# BeagleBone_Black_Wireless.net
KiCad netlist of a schematic drawn in EAGLE
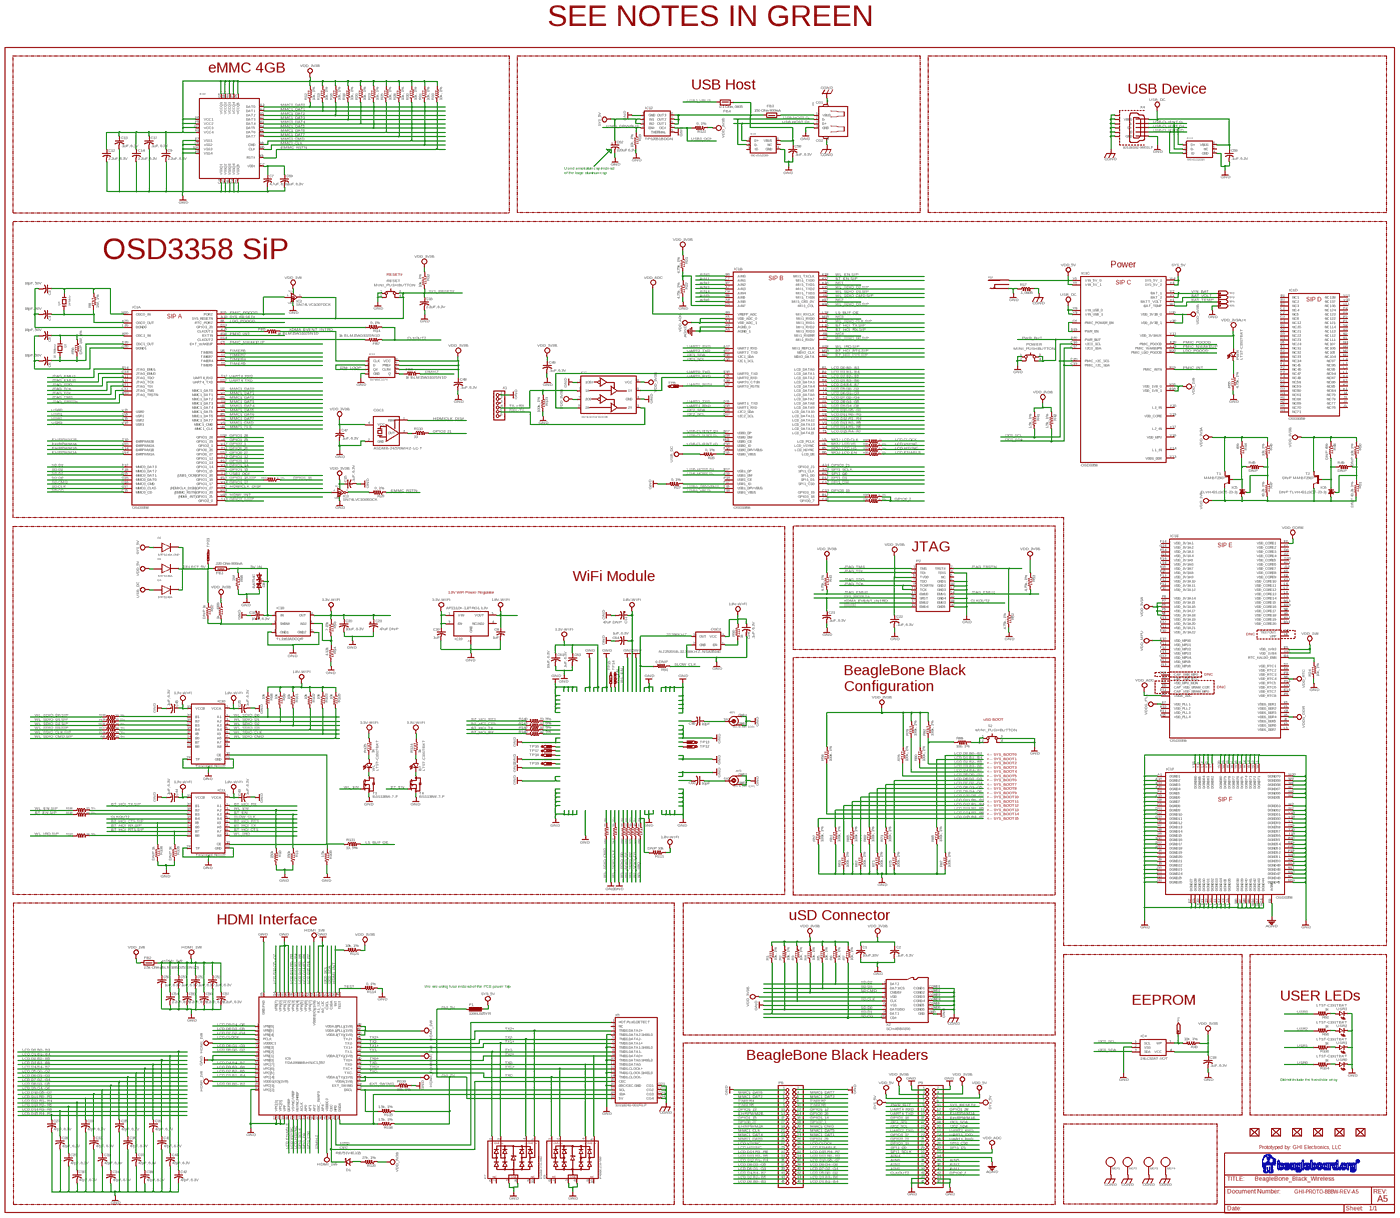
[diagram p0: schematic, sheet 1, overview]
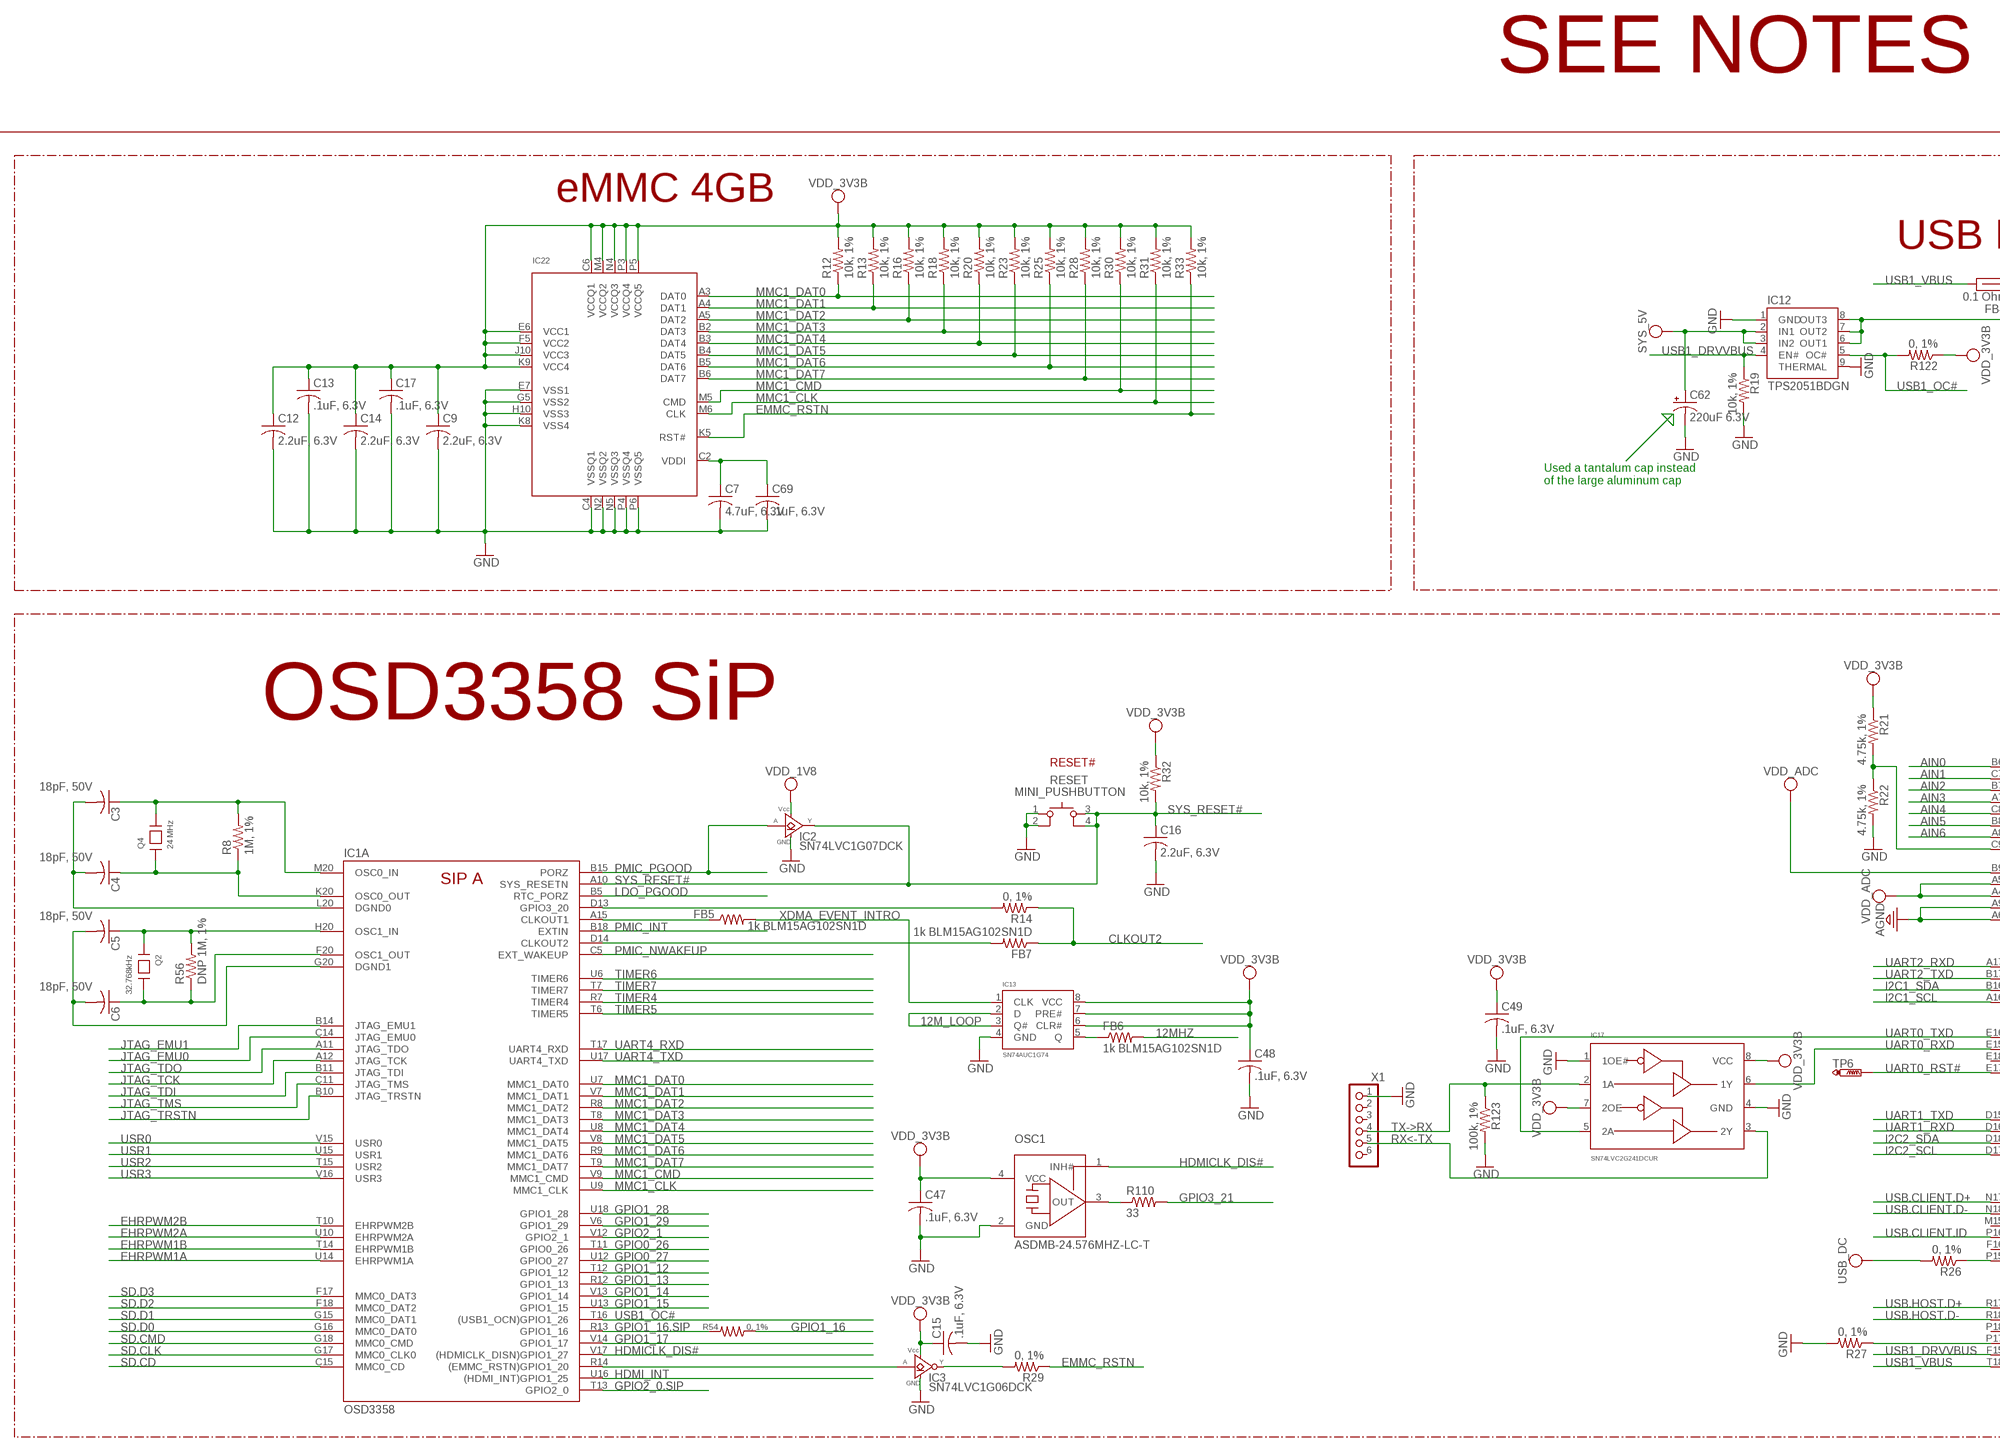
[diagram p1: schematic, sheet 1, part 1 of 4]
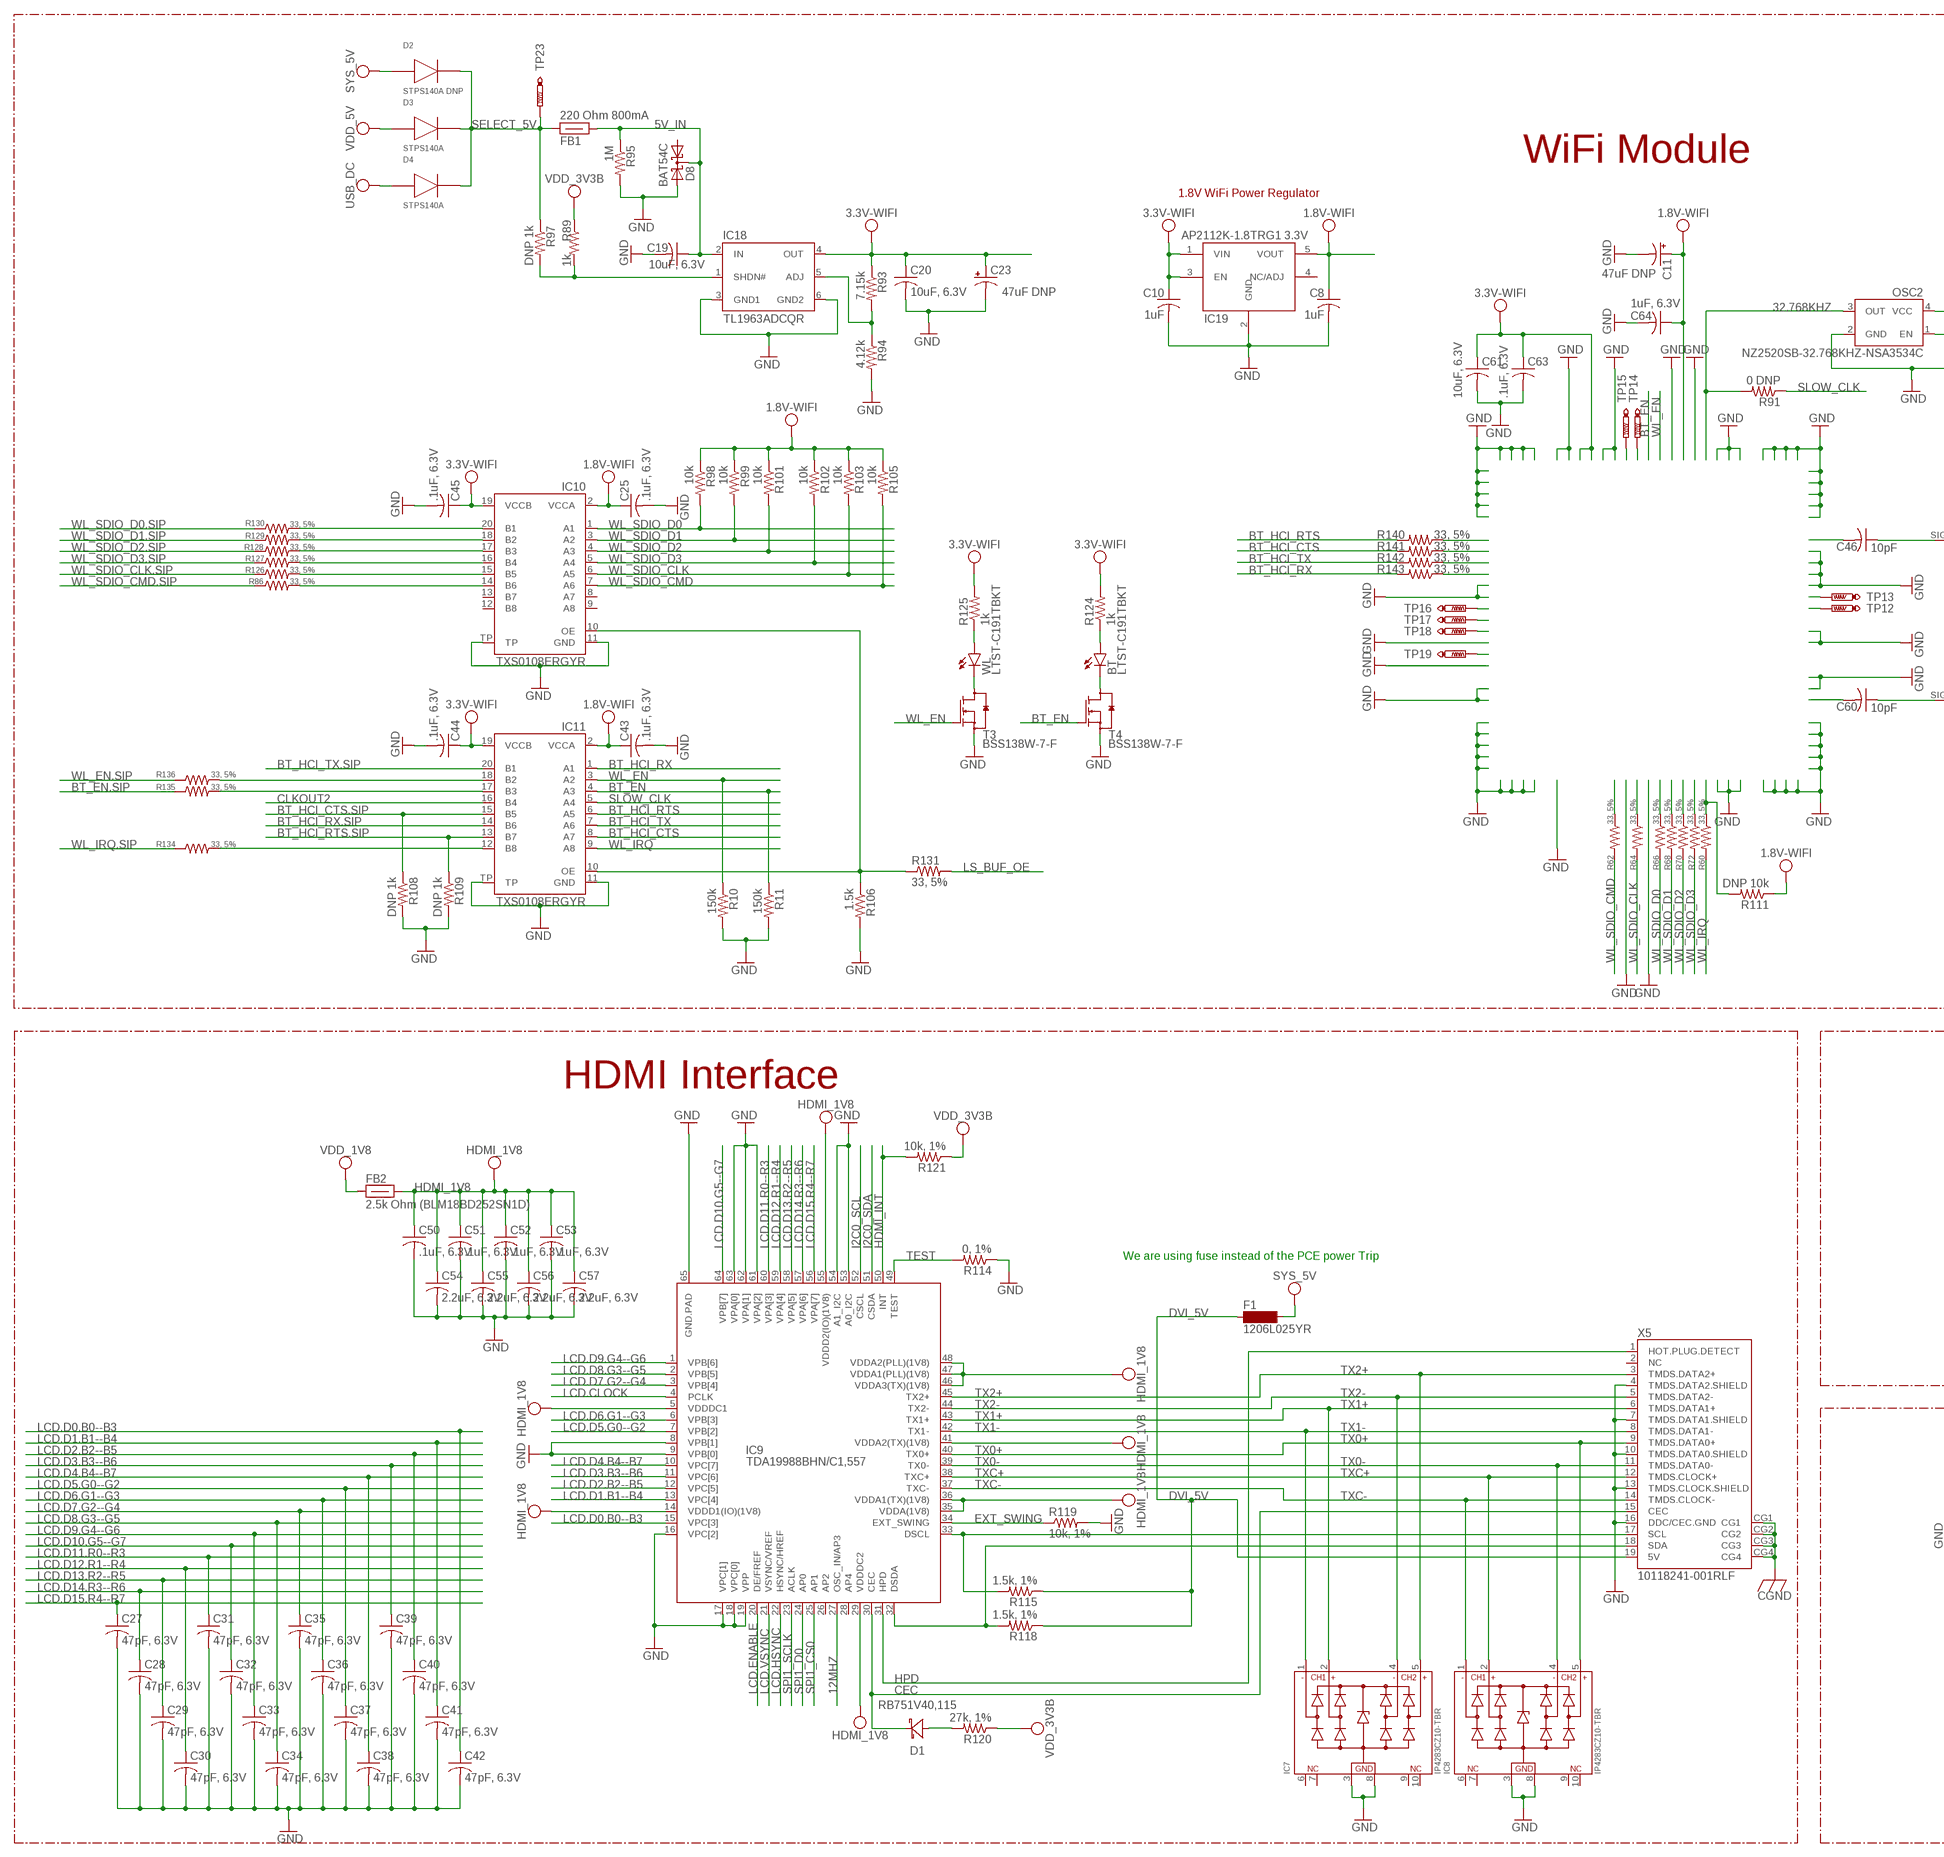
[diagram p2: schematic, sheet 1, part 2 of 4]
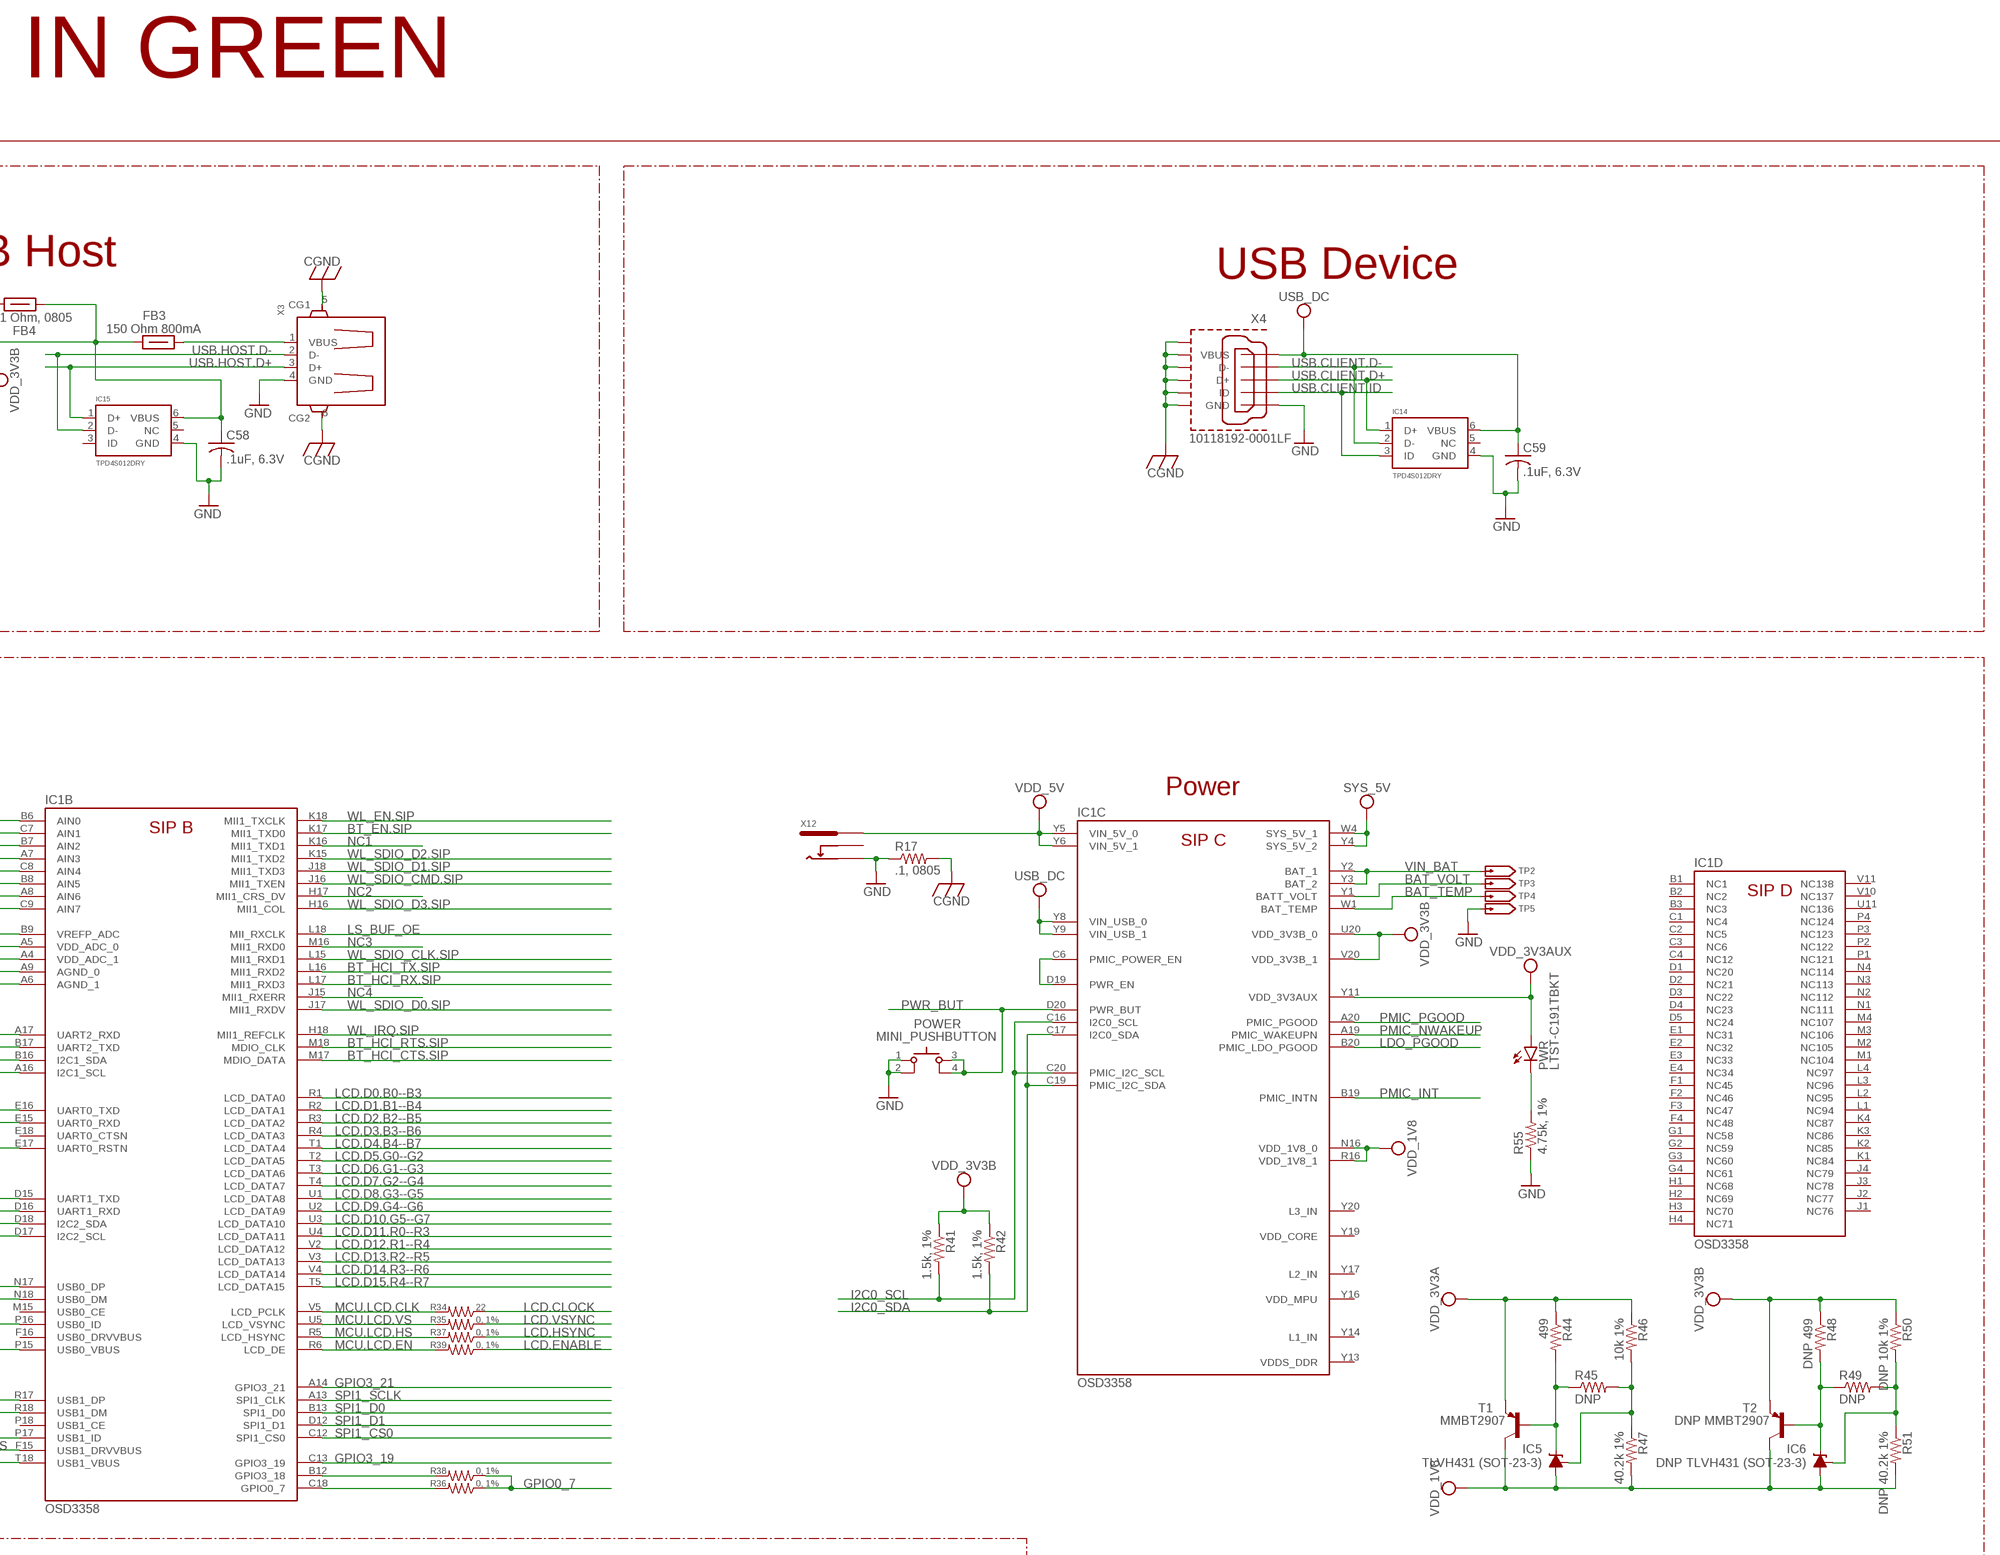
[diagram p3: schematic, sheet 1, part 3 of 4]
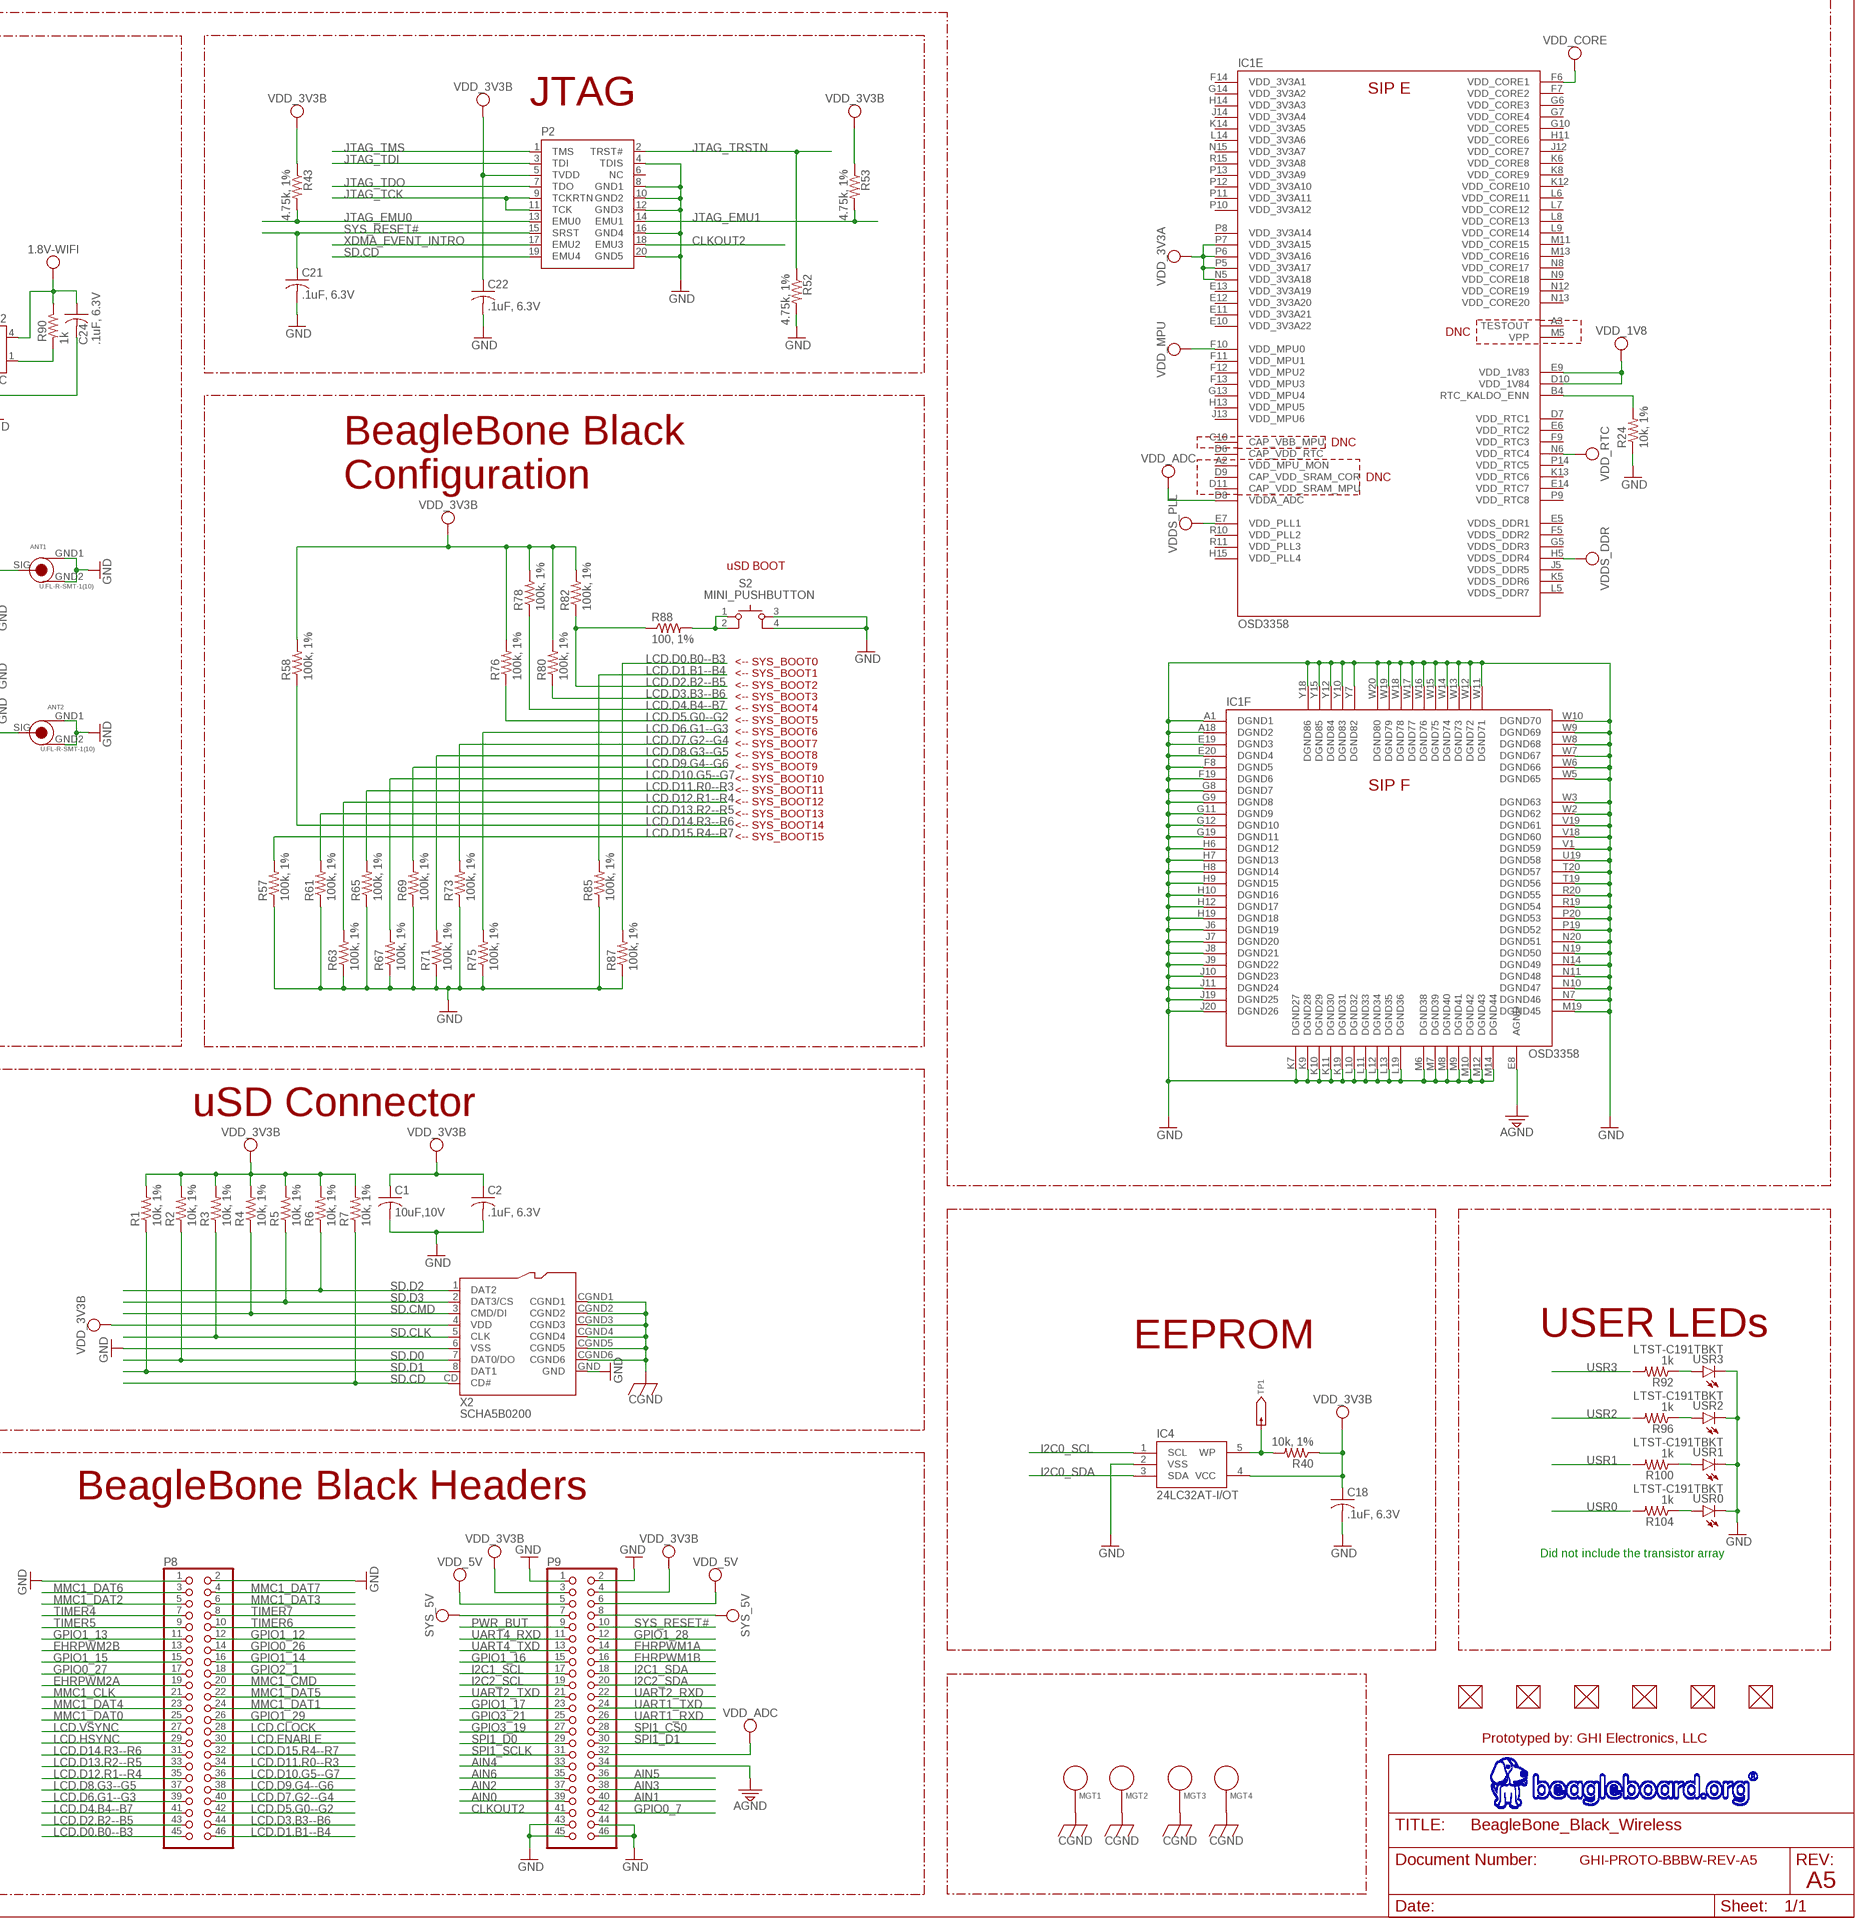
[diagram p4: schematic, sheet 1, part 4 of 4]

(export (version "E")
  (design (tool "Eeschema 10.0.6"))
  (components
    (comp (ref "ANT1")
      (value "U.FL-R-SMT-1(10)")
      (footprint "eagle-import:U.FL-R-SMT-1")
      (libsource (lib "eagle-import") (part "U.FL-R-SMT-1"))
    )
    (comp (ref "ANT2")
      (value "U.FL-R-SMT-1(10)")
      (footprint "eagle-import:U.FL-R-SMT-1")
      (libsource (lib "eagle-import") (part "U.FL-R-SMT-1"))
    )
    (comp (ref "BT")
      (value "LTST-C191TBKT")
      (footprint "eagle-import:0603-LED")
      (libsource (lib "eagle-import") (part "LED-(INCH)-0603"))
    )
    (comp (ref "C1")
      (value "10uF,10V")
      (footprint "eagle-import:C0603K")
      (libsource (lib "eagle-import") (part "C-USC0603K"))
    )
    (comp (ref "C2")
      (value ".1uF, 6.3V")
      (footprint "eagle-import:C0402K")
      (libsource (lib "eagle-import") (part "C-USC0402K"))
    )
    (comp (ref "C3")
      (value "18pF, 50V")
      (footprint "eagle-import:C0402K")
      (libsource (lib "eagle-import") (part "C-USC0402K"))
    )
    (comp (ref "C4")
      (value "18pF, 50V")
      (footprint "eagle-import:C0402K")
      (libsource (lib "eagle-import") (part "C-USC0402K"))
    )
    (comp (ref "C5")
      (value "18pF, 50V")
      (footprint "eagle-import:C0402K")
      (libsource (lib "eagle-import") (part "C-USC0402K"))
    )
    (comp (ref "C6")
      (value "18pF, 50V")
      (footprint "eagle-import:C0402K")
      (libsource (lib "eagle-import") (part "C-USC0402K"))
    )
    (comp (ref "C7")
      (value "4.7uF, 6.3V")
      (footprint "eagle-import:C0805K")
      (libsource (lib "eagle-import") (part "C-USC0805K"))
    )
    (comp (ref "C8")
      (value "1uF")
      (footprint "eagle-import:C0402K")
      (libsource (lib "eagle-import") (part "C-USC0402K"))
    )
    (comp (ref "C9")
      (value "2.2uF, 6.3V")
      (footprint "eagle-import:C0805K")
      (libsource (lib "eagle-import") (part "C-USC0805K"))
    )
    (comp (ref "C10")
      (value "1uF")
      (footprint "eagle-import:C0402K")
      (libsource (lib "eagle-import") (part "C-USC0402K"))
    )
    (comp (ref "C11")
      (value "47uF DNP")
      (footprint "eagle-import:CT3528")
      (libsource (lib "eagle-import") (part "CPOL-USCT3528"))
    )
    (comp (ref "C12")
      (value "2.2uF, 6.3V")
      (footprint "eagle-import:C0805K")
      (libsource (lib "eagle-import") (part "C-USC0805K"))
    )
    (comp (ref "C13")
      (value ".1uF, 6.3V")
      (footprint "eagle-import:C0402K")
      (libsource (lib "eagle-import") (part "C-USC0402K"))
    )
    (comp (ref "C14")
      (value "2.2uF, 6.3V")
      (footprint "eagle-import:C0805K")
      (libsource (lib "eagle-import") (part "C-USC0805K"))
    )
    (comp (ref "C15")
      (value ".1uF, 6.3V")
      (footprint "eagle-import:C0402K")
      (libsource (lib "eagle-import") (part "C-USC0402K"))
    )
    (comp (ref "C16")
      (value "2.2uF, 6.3V")
      (footprint "eagle-import:C0603K")
      (libsource (lib "eagle-import") (part "C-USC0603K"))
    )
    (comp (ref "C17")
      (value ".1uF, 6.3V")
      (footprint "eagle-import:C0402K")
      (libsource (lib "eagle-import") (part "C-USC0402K"))
    )
    (comp (ref "C18")
      (value ".1uF, 6.3V")
      (footprint "eagle-import:C0402K")
      (libsource (lib "eagle-import") (part "C-USC0402K"))
    )
    (comp (ref "C19")
      (value "10uF, 6.3V")
      (footprint "eagle-import:C0603K")
      (libsource (lib "eagle-import") (part "C-USC0603K"))
    )
    (comp (ref "C20")
      (value "10uF, 6.3V")
      (footprint "eagle-import:C0603K")
      (libsource (lib "eagle-import") (part "C-USC0603K"))
    )
    (comp (ref "C21")
      (value ".1uF, 6.3V")
      (footprint "eagle-import:C0402K")
      (libsource (lib "eagle-import") (part "C-USC0402K"))
    )
    (comp (ref "C22")
      (value ".1uF, 6.3V")
      (footprint "eagle-import:C0402K")
      (libsource (lib "eagle-import") (part "C-USC0402K"))
    )
    (comp (ref "C23")
      (value "47uF DNP")
      (footprint "eagle-import:CT3528")
      (libsource (lib "eagle-import") (part "CPOL-USCT3528"))
    )
    (comp (ref "C24")
      (value ".1uF, 6.3V")
      (footprint "eagle-import:C0402K")
      (libsource (lib "eagle-import") (part "C-USC0402K"))
    )
    (comp (ref "C25")
      (value ".1uF, 6.3V")
      (footprint "eagle-import:C0402K")
      (libsource (lib "eagle-import") (part "C-USC0402K"))
    )
    (comp (ref "C27")
      (value "47pF, 6.3V")
      (footprint "eagle-import:C0402K")
      (libsource (lib "eagle-import") (part "C-USC0402K"))
    )
    (comp (ref "C28")
      (value "47pF, 6.3V")
      (footprint "eagle-import:C0402K")
      (libsource (lib "eagle-import") (part "C-USC0402K"))
    )
    (comp (ref "C29")
      (value "47pF, 6.3V")
      (footprint "eagle-import:C0402K")
      (libsource (lib "eagle-import") (part "C-USC0402K"))
    )
    (comp (ref "C30")
      (value "47pF, 6.3V")
      (footprint "eagle-import:C0402K")
      (libsource (lib "eagle-import") (part "C-USC0402K"))
    )
    (comp (ref "C31")
      (value "47pF, 6.3V")
      (footprint "eagle-import:C0402K")
      (libsource (lib "eagle-import") (part "C-USC0402K"))
    )
    (comp (ref "C32")
      (value "47pF, 6.3V")
      (footprint "eagle-import:C0402K")
      (libsource (lib "eagle-import") (part "C-USC0402K"))
    )
    (comp (ref "C33")
      (value "47pF, 6.3V")
      (footprint "eagle-import:C0402K")
      (libsource (lib "eagle-import") (part "C-USC0402K"))
    )
    (comp (ref "C34")
      (value "47pF, 6.3V")
      (footprint "eagle-import:C0402K")
      (libsource (lib "eagle-import") (part "C-USC0402K"))
    )
    (comp (ref "C35")
      (value "47pF, 6.3V")
      (footprint "eagle-import:C0402K")
      (libsource (lib "eagle-import") (part "C-USC0402K"))
    )
    (comp (ref "C36")
      (value "47pF, 6.3V")
      (footprint "eagle-import:C0402K")
      (libsource (lib "eagle-import") (part "C-USC0402K"))
    )
    (comp (ref "C37")
      (value "47pF, 6.3V")
      (footprint "eagle-import:C0402K")
      (libsource (lib "eagle-import") (part "C-USC0402K"))
    )
    (comp (ref "C38")
      (value "47pF, 6.3V")
      (footprint "eagle-import:C0402K")
      (libsource (lib "eagle-import") (part "C-USC0402K"))
    )
    (comp (ref "C39")
      (value "47pF, 6.3V")
      (footprint "eagle-import:C0402K")
      (libsource (lib "eagle-import") (part "C-USC0402K"))
    )
    (comp (ref "C40")
      (value "47pF, 6.3V")
      (footprint "eagle-import:C0402K")
      (libsource (lib "eagle-import") (part "C-USC0402K"))
    )
    (comp (ref "C41")
      (value "47pF, 6.3V")
      (footprint "eagle-import:C0402K")
      (libsource (lib "eagle-import") (part "C-USC0402K"))
    )
    (comp (ref "C42")
      (value "47pF, 6.3V")
      (footprint "eagle-import:C0402K")
      (libsource (lib "eagle-import") (part "C-USC0402K"))
    )
    (comp (ref "C43")
      (value ".1uF, 6.3V")
      (footprint "eagle-import:C0402K")
      (libsource (lib "eagle-import") (part "C-USC0402K"))
    )
    (comp (ref "C44")
      (value ".1uF, 6.3V")
      (footprint "eagle-import:C0402K")
      (libsource (lib "eagle-import") (part "C-USC0402K"))
    )
    (comp (ref "C45")
      (value ".1uF, 6.3V")
      (footprint "eagle-import:C0402K")
      (libsource (lib "eagle-import") (part "C-USC0402K"))
    )
    (comp (ref "C46")
      (value "10pF")
      (footprint "eagle-import:C0402K")
      (libsource (lib "eagle-import") (part "C-USC0402K"))
    )
    (comp (ref "C47")
      (value ".1uF, 6.3V")
      (footprint "eagle-import:C0402K")
      (libsource (lib "eagle-import") (part "C-USC0402K"))
    )
    (comp (ref "C48")
      (value ".1uF, 6.3V")
      (footprint "eagle-import:C0402K")
      (libsource (lib "eagle-import") (part "C-USC0402K"))
    )
    (comp (ref "C49")
      (value ".1uF, 6.3V")
      (footprint "eagle-import:C0402K")
      (libsource (lib "eagle-import") (part "C-USC0402K"))
    )
    (comp (ref "C50")
      (value ".1uF, 6.3V")
      (footprint "eagle-import:C0402K")
      (libsource (lib "eagle-import") (part "C-USC0402K"))
    )
    (comp (ref "C51")
      (value ".1uF, 6.3V")
      (footprint "eagle-import:C0402K")
      (libsource (lib "eagle-import") (part "C-USC0402K"))
    )
    (comp (ref "C52")
      (value ".1uF, 6.3V")
      (footprint "eagle-import:C0402K")
      (libsource (lib "eagle-import") (part "C-USC0402K"))
    )
    (comp (ref "C53")
      (value ".1uF, 6.3V")
      (footprint "eagle-import:C0402K")
      (libsource (lib "eagle-import") (part "C-USC0402K"))
    )
    (comp (ref "C54")
      (value "2.2uF, 6.3V")
      (footprint "eagle-import:C0603K")
      (libsource (lib "eagle-import") (part "C-USC0603K"))
    )
    (comp (ref "C55")
      (value "2.2uF, 6.3V")
      (footprint "eagle-import:C0603K")
      (libsource (lib "eagle-import") (part "C-USC0603K"))
    )
    (comp (ref "C56")
      (value "2.2uF, 6.3V")
      (footprint "eagle-import:C0603K")
      (libsource (lib "eagle-import") (part "C-USC0603K"))
    )
    (comp (ref "C57")
      (value "2.2uF, 6.3V")
      (footprint "eagle-import:C0603K")
      (libsource (lib "eagle-import") (part "C-USC0603K"))
    )
    (comp (ref "C58")
      (value ".1uF, 6.3V")
      (footprint "eagle-import:C0402K")
      (libsource (lib "eagle-import") (part "C-USC0402K"))
    )
    (comp (ref "C59")
      (value ".1uF, 6.3V")
      (footprint "eagle-import:C0402K")
      (libsource (lib "eagle-import") (part "C-USC0402K"))
    )
    (comp (ref "C60")
      (value "10pF")
      (footprint "eagle-import:C0402K")
      (libsource (lib "eagle-import") (part "C-USC0402K"))
    )
    (comp (ref "C61")
      (value "10uF, 6.3V")
      (footprint "eagle-import:C0603K")
      (libsource (lib "eagle-import") (part "C-USC0603K"))
    )
    (comp (ref "C62")
      (value "220uF 6.3V")
      (footprint "eagle-import:D_7343-31W")
      (libsource (lib "eagle-import") (part "CPOL-USD/7343-31W"))
    )
    (comp (ref "C63")
      (value ".1uF, 6.3V")
      (footprint "eagle-import:C0402K")
      (libsource (lib "eagle-import") (part "C-USC0402K"))
    )
    (comp (ref "C64")
      (value "1uF, 6.3V")
      (footprint "eagle-import:C0402K")
      (libsource (lib "eagle-import") (part "C-USC0402K"))
    )
    (comp (ref "C69")
      (value ".1uF, 6.3V")
      (footprint "eagle-import:C0402K")
      (libsource (lib "eagle-import") (part "C-USC0402K"))
    )
    (comp (ref "D1")
      (value "RB751V40,115")
      (footprint "eagle-import:SOD323(NXP)REFLOW")
      (libsource (lib "eagle-import") (part "DIODE-SCHOTTKY-(NXP)-SOD323-(REFLOW)"))
    )
    (comp (ref "D2")
      (value "STPS140A DNP")
      (footprint "eagle-import:DIODE_SMA")
      (libsource (lib "eagle-import") (part "DIODE_SMA"))
    )
    (comp (ref "D3")
      (value "STPS140A")
      (footprint "eagle-import:DIODE_SMA")
      (libsource (lib "eagle-import") (part "DIODE_SMA"))
    )
    (comp (ref "D4")
      (value "STPS140A")
      (footprint "eagle-import:DIODE_SMA")
      (libsource (lib "eagle-import") (part "DIODE_SMA"))
    )
    (comp (ref "D8")
      (value "BAT54C")
      (footprint "eagle-import:SOT23")
      (libsource (lib "eagle-import") (part "BAT54C"))
    )
    (comp (ref "F1")
      (value "1206L025YR")
      (footprint "eagle-import:SM-1206")
      (libsource (lib "eagle-import") (part "SM-1206"))
    )
    (comp (ref "FB1")
      (value "220 Ohm 800mA")
      (footprint "eagle-import:0805-RESISTOR")
      (libsource (lib "eagle-import") (part "FB-(INCH)-0805"))
    )
    (comp (ref "FB2")
      (value "2.5k Ohm (BLM18BD252SN1D)")
      (footprint "eagle-import:0805-RESISTOR")
      (libsource (lib "eagle-import") (part "FB-(INCH)-0805"))
    )
    (comp (ref "FB3")
      (value "150 Ohm 800mA")
      (footprint "eagle-import:0805-RESISTOR")
      (libsource (lib "eagle-import") (part "FB-(INCH)-0805"))
    )
    (comp (ref "FB4")
      (value "0.1 Ohm, 0805")
      (footprint "eagle-import:0805-RESISTOR")
      (libsource (lib "eagle-import") (part "FB-(INCH)-0805"))
    )
    (comp (ref "FB5")
      (value "1k BLM15AG102SN1D")
      (footprint "eagle-import:R0402")
      (libsource (lib "eagle-import") (part "R-US_R0402"))
    )
    (comp (ref "FB6")
      (value "1k BLM15AG102SN1D")
      (footprint "eagle-import:R0402")
      (libsource (lib "eagle-import") (part "R-US_R0402"))
    )
    (comp (ref "FB7")
      (value "1k BLM15AG102SN1D")
      (footprint "eagle-import:R0402")
      (libsource (lib "eagle-import") (part "R-US_R0402"))
    )
    (comp (ref "FUD1")
      (value "FIDUCIAL")
      (footprint "eagle-import:FIDUCIAL_40MIL")
      (libsource (lib "eagle-import") (part "FIDUCIAL"))
    )
    (comp (ref "FUD2")
      (value "FIDUCIAL")
      (footprint "eagle-import:FIDUCIAL_40MIL")
      (libsource (lib "eagle-import") (part "FIDUCIAL"))
    )
    (comp (ref "FUD3")
      (value "FIDUCIAL")
      (footprint "eagle-import:FIDUCIAL_40MIL")
      (libsource (lib "eagle-import") (part "FIDUCIAL"))
    )
    (comp (ref "FUD4")
      (value "FIDUCIAL")
      (footprint "eagle-import:FIDUCIAL_40MIL")
      (libsource (lib "eagle-import") (part "FIDUCIAL"))
    )
    (comp (ref "FUD5")
      (value "FIDUCIAL")
      (footprint "eagle-import:FIDUCIAL_40MIL")
      (libsource (lib "eagle-import") (part "FIDUCIAL"))
    )
    (comp (ref "FUD6")
      (value "FIDUCIAL")
      (footprint "eagle-import:FIDUCIAL_40MIL")
      (libsource (lib "eagle-import") (part "FIDUCIAL"))
    )
    (comp (ref "IC1")
      (value "OSD3358")
      (footprint "eagle-import:OSD3358")
      (libsource (lib "eagle-import") (part "SIP1000"))
    )
    (comp (ref "IC2")
      (value "SN74LVC1G07DCK")
      (footprint "eagle-import:SC70(TI-DCK)")
      (libsource (lib "eagle-import") (part "SN74LVC1G07DCK"))
    )
    (comp (ref "IC3")
      (value "SN74LVC1G06DCK")
      (footprint "eagle-import:SC70(TI-DCK)")
      (libsource (lib "eagle-import") (part "SN74LVC1G06DCK"))
    )
    (comp (ref "IC4")
      (value "24LC32AT-I/OT")
      (footprint "eagle-import:SOT23-5(MICROCHIP)")
      (libsource (lib "eagle-import") (part "24LC32A{dblquote}"))
    )
    (comp (ref "IC5")
      (value "TLVH431 (SOT-23-3)")
      (footprint "eagle-import:DBZ_R-PDSO-G3")
      (fields (field (name "MF") "TEXAS INSTRUMENT CONNECTORS") (field (name "MPN") "LM4041DIDBZR"))
      (libsource (lib "eagle-import") (part "LM4041IDBZD"))
    )
    (comp (ref "IC6")
      (value "DNP TLVH431 (SOT-23-3)")
      (footprint "eagle-import:DBZ_R-PDSO-G3")
      (fields (field (name "MF") "TEXAS INSTRUMENT CONNECTORS") (field (name "MPN") "LM4041DIDBZR"))
      (libsource (lib "eagle-import") (part "LM4041IDBZD"))
    )
    (comp (ref "IC7")
      (value "IP4283CZ10-TBR")
      (footprint "eagle-import:SOT1176-1(NXP)")
      (libsource (lib "eagle-import") (part "IP4283CZ10IP4283CZ10-TBR"))
    )
    (comp (ref "IC8")
      (value "IP4283CZ10-TBR")
      (footprint "eagle-import:SOT1176-1(NXP)")
      (libsource (lib "eagle-import") (part "IP4283CZ10IP4283CZ10-TBR"))
    )
    (comp (ref "IC9")
      (value "TDA19988BHN/C1,557")
      (footprint "eagle-import:SOT804-4(NXP)")
      (libsource (lib "eagle-import") (part "TDA19988BHN/C1"))
    )
    (comp (ref "IC10")
      (value "TXS0108ERGYR")
      (footprint "eagle-import:R-PVQFN-N20(TI)")
      (libsource (lib "eagle-import") (part "TXS0108ERGYR"))
    )
    (comp (ref "IC11")
      (value "TXS0108ERGYR")
      (footprint "eagle-import:R-PVQFN-N20(TI)")
      (libsource (lib "eagle-import") (part "TXS0108ERGYR"))
    )
    (comp (ref "IC12")
      (value "TPS2051BDGN")
      (footprint "eagle-import:MSOP-POWER.PAD-8(TI)")
      (libsource (lib "eagle-import") (part "TPS2051B"))
    )
    (comp (ref "IC13")
      (value "SN74AUC1G74")
      (footprint "eagle-import:SM8-8(TI)")
      (libsource (lib "eagle-import") (part "SN74AUC1G74"))
    )
    (comp (ref "IC14")
      (value "TPD4S012DRY")
      (footprint "eagle-import:SON-6(TI)-DRY")
      (libsource (lib "eagle-import") (part "TPD4S012DRYR"))
    )
    (comp (ref "IC15")
      (value "TPD4S012DRY")
      (footprint "eagle-import:SON-6(TI)-DRY")
      (libsource (lib "eagle-import") (part "TPD4S012DRYR"))
    )
    (comp (ref "IC17")
      (value "SN74LVC2G241DCUR")
      (footprint "eagle-import:VSSOP8(TI)")
      (libsource (lib "eagle-import") (part "SN74LVC2G241DCUR"))
    )
    (comp (ref "IC18")
      (value "TL1963ADCQR")
      (footprint "eagle-import:SOT-223(DCQ_R-PDSO-G6_TI)")
      (libsource (lib "eagle-import") (part "TL1963A"))
    )
    (comp (ref "IC19")
      (value "AP2112K-1.8TRG1 3.3V")
      (footprint "eagle-import:SOT23-5")
      (libsource (lib "eagle-import") (part "5PIN_REG"))
    )
    (comp (ref "IC22")
      (value "EMMC04G-S100-B08U")
      (footprint "eagle-import:MICRON_EMMC_153")
      (libsource (lib "eagle-import") (part "EMMC04G-S100-B08U"))
    )
    (comp (ref "MGT1")
      (value "MOUNTING_HOLE")
      (footprint "eagle-import:MOUNTING_HOLE")
      (libsource (lib "eagle-import") (part "MOUNTING_HOLE"))
    )
    (comp (ref "MGT2")
      (value "MOUNTING_HOLE")
      (footprint "eagle-import:MOUNTING_HOLE")
      (libsource (lib "eagle-import") (part "MOUNTING_HOLE"))
    )
    (comp (ref "MGT3")
      (value "MOUNTING_HOLE")
      (footprint "eagle-import:MOUNTING_HOLE")
      (libsource (lib "eagle-import") (part "MOUNTING_HOLE"))
    )
    (comp (ref "MGT4")
      (value "MOUNTING_HOLE")
      (footprint "eagle-import:MOUNTING_HOLE")
      (libsource (lib "eagle-import") (part "MOUNTING_HOLE"))
    )
    (comp (ref "OSC1")
      (value "ASDMB-24.576MHZ-LC-T")
      (footprint "eagle-import:OSCILLATOR-2.5X2.0-BBB")
      (libsource (lib "eagle-import") (part "OSC-2.5X2.0"))
    )
    (comp (ref "OSC2")
      (value "NZ2520SB-32.768KHZ-NSA3534C")
      (footprint "eagle-import:NZ2520S")
      (libsource (lib "eagle-import") (part "OSCILLATOR"))
    )
    (comp (ref "P2")
      (value "JTAG")
      (footprint "eagle-import:JTAG")
      (libsource (lib "eagle-import") (part "JTAG"))
    )
    (comp (ref "P8")
      (value "HEADER-2X23-(INCH)-0.1-TH")
      (footprint "eagle-import:TH-2X23")
      (libsource (lib "eagle-import") (part "HEADER-2X23-(INCH)-0.1-TH"))
    )
    (comp (ref "P9")
      (value "HEADER-2X23-(INCH)-0.1-TH")
      (footprint "eagle-import:TH-2X23")
      (libsource (lib "eagle-import") (part "HEADER-2X23-(INCH)-0.1-TH"))
    )
    (comp (ref "POWER")
      (value "MINI_PUSHBUTTON")
      (footprint "eagle-import:MINI_PUSHBUTTON")
      (libsource (lib "eagle-import") (part "MINI_PUSHBUTTON"))
    )
    (comp (ref "PWR")
      (value "LTST-C191TBKT")
      (footprint "eagle-import:0603-LED")
      (libsource (lib "eagle-import") (part "LED-(INCH)-0603"))
    )
    (comp (ref "Q2")
      (value "32.768kHz")
      (footprint "eagle-import:CRYSTAL_3.2X1.5")
      (libsource (lib "eagle-import") (part "CRYSTAL_3.2X1.5"))
    )
    (comp (ref "Q4")
      (value "24 MHz")
      (footprint "eagle-import:CRYSTAL_5X3.2MM")
      (libsource (lib "eagle-import") (part "CRYSTAL_5X3.2MM"))
    )
    (comp (ref "R1")
      (value "10k, 1%")
      (footprint "eagle-import:R0402")
      (libsource (lib "eagle-import") (part "R-US_R0402"))
    )
    (comp (ref "R2")
      (value "10k, 1%")
      (footprint "eagle-import:R0402")
      (libsource (lib "eagle-import") (part "R-US_R0402"))
    )
    (comp (ref "R3")
      (value "10k, 1%")
      (footprint "eagle-import:R0402")
      (libsource (lib "eagle-import") (part "R-US_R0402"))
    )
    (comp (ref "R4")
      (value "10k, 1%")
      (footprint "eagle-import:R0402")
      (libsource (lib "eagle-import") (part "R-US_R0402"))
    )
    (comp (ref "R5")
      (value "10k, 1%")
      (footprint "eagle-import:R0402")
      (libsource (lib "eagle-import") (part "R-US_R0402"))
    )
    (comp (ref "R6")
      (value "10k, 1%")
      (footprint "eagle-import:R0402")
      (libsource (lib "eagle-import") (part "R-US_R0402"))
    )
    (comp (ref "R7")
      (value "10k, 1%")
      (footprint "eagle-import:R0402")
      (libsource (lib "eagle-import") (part "R-US_R0402"))
    )
    (comp (ref "R8")
      (value "1M, 1%")
      (footprint "eagle-import:R0402")
      (libsource (lib "eagle-import") (part "R-US_R0402"))
    )
    (comp (ref "R10")
      (value "150k")
      (footprint "eagle-import:R0402")
      (libsource (lib "eagle-import") (part "R-US_R0402"))
    )
    (comp (ref "R11")
      (value "150k")
      (footprint "eagle-import:R0402")
      (libsource (lib "eagle-import") (part "R-US_R0402"))
    )
    (comp (ref "R12")
      (value "10k, 1%")
      (footprint "eagle-import:R0402")
      (libsource (lib "eagle-import") (part "R-US_R0402"))
    )
    (comp (ref "R13")
      (value "10k, 1%")
      (footprint "eagle-import:R0402")
      (libsource (lib "eagle-import") (part "R-US_R0402"))
    )
    (comp (ref "R14")
      (value "0, 1%")
      (footprint "eagle-import:R0402")
      (libsource (lib "eagle-import") (part "R-US_R0402"))
    )
    (comp (ref "R16")
      (value "10k, 1%")
      (footprint "eagle-import:R0402")
      (libsource (lib "eagle-import") (part "R-US_R0402"))
    )
    (comp (ref "R17")
      (value ".1, 0805")
      (footprint "eagle-import:R0805")
      (libsource (lib "eagle-import") (part "R-US_R0805"))
    )
    (comp (ref "R18")
      (value "10k, 1%")
      (footprint "eagle-import:R0402")
      (libsource (lib "eagle-import") (part "R-US_R0402"))
    )
    (comp (ref "R19")
      (value "10k, 1%")
      (footprint "eagle-import:R0402")
      (libsource (lib "eagle-import") (part "R-US_R0402"))
    )
    (comp (ref "R20")
      (value "10k, 1%")
      (footprint "eagle-import:R0402")
      (libsource (lib "eagle-import") (part "R-US_R0402"))
    )
    (comp (ref "R21")
      (value "4.75k, 1%")
      (footprint "eagle-import:R0402")
      (libsource (lib "eagle-import") (part "R-US_R0402"))
    )
    (comp (ref "R22")
      (value "4.75k, 1%")
      (footprint "eagle-import:R0402")
      (libsource (lib "eagle-import") (part "R-US_R0402"))
    )
    (comp (ref "R23")
      (value "10k, 1%")
      (footprint "eagle-import:R0402")
      (libsource (lib "eagle-import") (part "R-US_R0402"))
    )
    (comp (ref "R24")
      (value "10k, 1%")
      (footprint "eagle-import:R0402")
      (libsource (lib "eagle-import") (part "R-US_R0402"))
    )
    (comp (ref "R25")
      (value "10k, 1%")
      (footprint "eagle-import:R0402")
      (libsource (lib "eagle-import") (part "R-US_R0402"))
    )
    (comp (ref "R26")
      (value "0, 1%")
      (footprint "eagle-import:R0402")
      (libsource (lib "eagle-import") (part "R-US_R0402"))
    )
    (comp (ref "R27")
      (value "0, 1%")
      (footprint "eagle-import:R0402")
      (libsource (lib "eagle-import") (part "R-US_R0402"))
    )
    (comp (ref "R28")
      (value "10k, 1%")
      (footprint "eagle-import:R0402")
      (libsource (lib "eagle-import") (part "R-US_R0402"))
    )
    (comp (ref "R29")
      (value "0, 1%")
      (footprint "eagle-import:R0402")
      (libsource (lib "eagle-import") (part "R-US_R0402"))
    )
    (comp (ref "R30")
      (value "10k, 1%")
      (footprint "eagle-import:R0402")
      (libsource (lib "eagle-import") (part "R-US_R0402"))
    )
    (comp (ref "R31")
      (value "10k, 1%")
      (footprint "eagle-import:R0402")
      (libsource (lib "eagle-import") (part "R-US_R0402"))
    )
    (comp (ref "R32")
      (value "10k, 1%")
      (footprint "eagle-import:R0402")
      (libsource (lib "eagle-import") (part "R-US_R0402"))
    )
    (comp (ref "R33")
      (value "10k, 1%")
      (footprint "eagle-import:R0402")
      (libsource (lib "eagle-import") (part "R-US_R0402"))
    )
    (comp (ref "R34")
      (value "22")
      (footprint "eagle-import:R0402")
      (libsource (lib "eagle-import") (part "R-US_R0402"))
    )
    (comp (ref "R35")
      (value "0, 1%")
      (footprint "eagle-import:R0402")
      (libsource (lib "eagle-import") (part "R-US_R0402"))
    )
    (comp (ref "R36")
      (value "0, 1%")
      (footprint "eagle-import:R0402")
      (libsource (lib "eagle-import") (part "R-US_R0402"))
    )
    (comp (ref "R37")
      (value "0, 1%")
      (footprint "eagle-import:R0402")
      (libsource (lib "eagle-import") (part "R-US_R0402"))
    )
    (comp (ref "R38")
      (value "0, 1%")
      (footprint "eagle-import:R0402")
      (libsource (lib "eagle-import") (part "R-US_R0402"))
    )
    (comp (ref "R39")
      (value "0, 1%")
      (footprint "eagle-import:R0402")
      (libsource (lib "eagle-import") (part "R-US_R0402"))
    )
    (comp (ref "R40")
      (value "10k, 1%")
      (footprint "eagle-import:R0402")
      (libsource (lib "eagle-import") (part "R-US_R0402"))
    )
    (comp (ref "R41")
      (value "1.5k, 1%")
      (footprint "eagle-import:R0402")
      (libsource (lib "eagle-import") (part "R-US_R0402"))
    )
    (comp (ref "R42")
      (value "1.5k, 1%")
      (footprint "eagle-import:R0402")
      (libsource (lib "eagle-import") (part "R-US_R0402"))
    )
    (comp (ref "R43")
      (value "4.75k, 1%")
      (footprint "eagle-import:R0402")
      (libsource (lib "eagle-import") (part "R-US_R0402"))
    )
    (comp (ref "R44")
      (value "499")
      (footprint "eagle-import:R0402")
      (libsource (lib "eagle-import") (part "R-US_R0402"))
    )
    (comp (ref "R45")
      (value "DNP")
      (footprint "eagle-import:R0402")
      (libsource (lib "eagle-import") (part "R-US_R0402"))
    )
    (comp (ref "R46")
      (value "10k 1%")
      (footprint "eagle-import:R0402")
      (libsource (lib "eagle-import") (part "R-US_R0402"))
    )
    (comp (ref "R47")
      (value "40.2k 1%")
      (footprint "eagle-import:R0402")
      (libsource (lib "eagle-import") (part "R-US_R0402"))
    )
    (comp (ref "R48")
      (value "DNP 499")
      (footprint "eagle-import:R0402")
      (libsource (lib "eagle-import") (part "R-US_R0402"))
    )
    (comp (ref "R49")
      (value "DNP")
      (footprint "eagle-import:R0402")
      (libsource (lib "eagle-import") (part "R-US_R0402"))
    )
    (comp (ref "R50")
      (value "DNP 10k 1%")
      (footprint "eagle-import:R0402")
      (libsource (lib "eagle-import") (part "R-US_R0402"))
    )
    (comp (ref "R51")
      (value "DNP 40.2k 1%")
      (footprint "eagle-import:R0402")
      (libsource (lib "eagle-import") (part "R-US_R0402"))
    )
    (comp (ref "R52")
      (value "4.75k, 1%")
      (footprint "eagle-import:R0402")
      (libsource (lib "eagle-import") (part "R-US_R0402"))
    )
    (comp (ref "R53")
      (value "4.75k, 1%")
      (footprint "eagle-import:R0402")
      (libsource (lib "eagle-import") (part "R-US_R0402"))
    )
    (comp (ref "R54")
      (value "0, 1%")
      (footprint "eagle-import:R0402")
      (libsource (lib "eagle-import") (part "R-US_R0402"))
    )
    (comp (ref "R55")
      (value "4.75k, 1%")
      (footprint "eagle-import:R0402")
      (libsource (lib "eagle-import") (part "R-US_R0402"))
    )
    (comp (ref "R56")
      (value "DNP 1M, 1%")
      (footprint "eagle-import:R0402")
      (libsource (lib "eagle-import") (part "R-US_R0402"))
    )
    (comp (ref "R57")
      (value "100k, 1%")
      (footprint "eagle-import:R0402")
      (libsource (lib "eagle-import") (part "R-US_R0402"))
    )
    (comp (ref "R58")
      (value "100k, 1%")
      (footprint "eagle-import:R0402")
      (libsource (lib "eagle-import") (part "R-US_R0402"))
    )
    (comp (ref "R60")
      (value "33, 5%")
      (footprint "eagle-import:R0402")
      (libsource (lib "eagle-import") (part "R-US_R0402"))
    )
    (comp (ref "R61")
      (value "100k, 1%")
      (footprint "eagle-import:R0402")
      (libsource (lib "eagle-import") (part "R-US_R0402"))
    )
    (comp (ref "R62")
      (value "33, 5%")
      (footprint "eagle-import:R0402")
      (libsource (lib "eagle-import") (part "R-US_R0402"))
    )
    (comp (ref "R63")
      (value "100k, 1%")
      (footprint "eagle-import:R0402")
      (libsource (lib "eagle-import") (part "R-US_R0402"))
    )
    (comp (ref "R64")
      (value "33, 5%")
      (footprint "eagle-import:R0402")
      (libsource (lib "eagle-import") (part "R-US_R0402"))
    )
    (comp (ref "R65")
      (value "100k, 1%")
      (footprint "eagle-import:R0402")
      (libsource (lib "eagle-import") (part "R-US_R0402"))
    )
    (comp (ref "R66")
      (value "33, 5%")
      (footprint "eagle-import:R0402")
      (libsource (lib "eagle-import") (part "R-US_R0402"))
    )
    (comp (ref "R67")
      (value "100k, 1%")
      (footprint "eagle-import:R0402")
      (libsource (lib "eagle-import") (part "R-US_R0402"))
    )
    (comp (ref "R68")
      (value "33, 5%")
      (footprint "eagle-import:R0402")
      (libsource (lib "eagle-import") (part "R-US_R0402"))
    )
    (comp (ref "R69")
      (value "100k, 1%")
      (footprint "eagle-import:R0402")
      (libsource (lib "eagle-import") (part "R-US_R0402"))
    )
    (comp (ref "R70")
      (value "33, 5%")
      (footprint "eagle-import:R0402")
      (libsource (lib "eagle-import") (part "R-US_R0402"))
    )
    (comp (ref "R71")
      (value "100k, 1%")
      (footprint "eagle-import:R0402")
      (libsource (lib "eagle-import") (part "R-US_R0402"))
    )
    (comp (ref "R72")
      (value "33, 5%")
      (footprint "eagle-import:R0402")
      (libsource (lib "eagle-import") (part "R-US_R0402"))
    )
    (comp (ref "R73")
      (value "100k, 1%")
      (footprint "eagle-import:R0402")
      (libsource (lib "eagle-import") (part "R-US_R0402"))
    )
    (comp (ref "R75")
      (value "100k, 1%")
      (footprint "eagle-import:R0402")
      (libsource (lib "eagle-import") (part "R-US_R0402"))
    )
    (comp (ref "R76")
      (value "100k, 1%")
      (footprint "eagle-import:R0402")
      (libsource (lib "eagle-import") (part "R-US_R0402"))
    )
    (comp (ref "R78")
      (value "100k, 1%")
      (footprint "eagle-import:R0402")
      (libsource (lib "eagle-import") (part "R-US_R0402"))
    )
    (comp (ref "R80")
      (value "100k, 1%")
      (footprint "eagle-import:R0402")
      (libsource (lib "eagle-import") (part "R-US_R0402"))
    )
    (comp (ref "R82")
      (value "100k, 1%")
      (footprint "eagle-import:R0402")
      (libsource (lib "eagle-import") (part "R-US_R0402"))
    )
    (comp (ref "R85")
      (value "100k, 1%")
      (footprint "eagle-import:R0402")
      (libsource (lib "eagle-import") (part "R-US_R0402"))
    )
    (comp (ref "R86")
      (value "33, 5%")
      (footprint "eagle-import:R0603")
      (libsource (lib "eagle-import") (part "R-US_R0603"))
    )
    (comp (ref "R87")
      (value "100k, 1%")
      (footprint "eagle-import:R0402")
      (libsource (lib "eagle-import") (part "R-US_R0402"))
    )
    (comp (ref "R88")
      (value "100, 1%")
      (footprint "eagle-import:R0402")
      (libsource (lib "eagle-import") (part "R-US_R0402"))
    )
    (comp (ref "R89")
      (value "1k")
      (footprint "eagle-import:R0402")
      (libsource (lib "eagle-import") (part "R-US_R0402"))
    )
    (comp (ref "R90")
      (value "1k")
      (footprint "eagle-import:R0402")
      (libsource (lib "eagle-import") (part "R-US_R0402"))
    )
    (comp (ref "R91")
      (value "0 DNP")
      (footprint "eagle-import:R0402")
      (libsource (lib "eagle-import") (part "R-US_R0402"))
    )
    (comp (ref "R92")
      (value "1k")
      (footprint "eagle-import:R0402")
      (libsource (lib "eagle-import") (part "R-US_R0402"))
    )
    (comp (ref "R93")
      (value "7.15k")
      (footprint "eagle-import:R0402")
      (libsource (lib "eagle-import") (part "R-US_R0402"))
    )
    (comp (ref "R94")
      (value "4.12k")
      (footprint "eagle-import:R0402")
      (libsource (lib "eagle-import") (part "R-US_R0402"))
    )
    (comp (ref "R95")
      (value "1M")
      (footprint "eagle-import:R0402")
      (libsource (lib "eagle-import") (part "R-US_R0402"))
    )
    (comp (ref "R96")
      (value "1k")
      (footprint "eagle-import:R0402")
      (libsource (lib "eagle-import") (part "R-US_R0402"))
    )
    (comp (ref "R97")
      (value "DNP 1k")
      (footprint "eagle-import:R0402")
      (libsource (lib "eagle-import") (part "R-US_R0402"))
    )
    (comp (ref "R98")
      (value "10k")
      (footprint "eagle-import:R0402")
      (libsource (lib "eagle-import") (part "R-US_R0402"))
    )
    (comp (ref "R99")
      (value "10k")
      (footprint "eagle-import:R0402")
      (libsource (lib "eagle-import") (part "R-US_R0402"))
    )
    (comp (ref "R100")
      (value "1k")
      (footprint "eagle-import:R0402")
      (libsource (lib "eagle-import") (part "R-US_R0402"))
    )
    (comp (ref "R101")
      (value "10k")
      (footprint "eagle-import:R0402")
      (libsource (lib "eagle-import") (part "R-US_R0402"))
    )
    (comp (ref "R102")
      (value "10k")
      (footprint "eagle-import:R0402")
      (libsource (lib "eagle-import") (part "R-US_R0402"))
    )
    (comp (ref "R103")
      (value "10k")
      (footprint "eagle-import:R0402")
      (libsource (lib "eagle-import") (part "R-US_R0402"))
    )
    (comp (ref "R104")
      (value "1k")
      (footprint "eagle-import:R0402")
      (libsource (lib "eagle-import") (part "R-US_R0402"))
    )
    (comp (ref "R105")
      (value "10k")
      (footprint "eagle-import:R0402")
      (libsource (lib "eagle-import") (part "R-US_R0402"))
    )
    (comp (ref "R106")
      (value "1.5k")
      (footprint "eagle-import:R0402")
      (libsource (lib "eagle-import") (part "R-US_R0402"))
    )
    (comp (ref "R108")
      (value "DNP 1k")
      (footprint "eagle-import:R0402")
      (libsource (lib "eagle-import") (part "R-US_R0402"))
    )
    (comp (ref "R109")
      (value "DNP 1k")
      (footprint "eagle-import:R0402")
      (libsource (lib "eagle-import") (part "R-US_R0402"))
    )
    (comp (ref "R110")
      (value "33")
      (footprint "eagle-import:R0402")
      (libsource (lib "eagle-import") (part "R-US_R0402"))
    )
    (comp (ref "R111")
      (value "DNP 10k")
      (footprint "eagle-import:R0402")
      (libsource (lib "eagle-import") (part "R-US_R0402"))
    )
    (comp (ref "R114")
      (value "0, 1%")
      (footprint "eagle-import:R0402")
      (libsource (lib "eagle-import") (part "R-US_R0402"))
    )
    (comp (ref "R115")
      (value "1.5k, 1%")
      (footprint "eagle-import:R0402")
      (libsource (lib "eagle-import") (part "R-US_R0402"))
    )
    (comp (ref "R118")
      (value "1.5k, 1%")
      (footprint "eagle-import:R0402")
      (libsource (lib "eagle-import") (part "R-US_R0402"))
    )
    (comp (ref "R119")
      (value "10k, 1%")
      (footprint "eagle-import:R0402")
      (libsource (lib "eagle-import") (part "R-US_R0402"))
    )
    (comp (ref "R120")
      (value "27k, 1%")
      (footprint "eagle-import:R0402")
      (libsource (lib "eagle-import") (part "R-US_R0402"))
    )
    (comp (ref "R121")
      (value "10k, 1%")
      (footprint "eagle-import:R0402")
      (libsource (lib "eagle-import") (part "R-US_R0402"))
    )
    (comp (ref "R122")
      (value "0, 1%")
      (footprint "eagle-import:R0402")
      (libsource (lib "eagle-import") (part "R-US_R0402"))
    )
    (comp (ref "R123")
      (value "100k, 1%")
      (footprint "eagle-import:R0402")
      (libsource (lib "eagle-import") (part "R-US_R0402"))
    )
    (comp (ref "R124")
      (value "1k")
      (footprint "eagle-import:R0402")
      (libsource (lib "eagle-import") (part "R-US_R0402"))
    )
    (comp (ref "R125")
      (value "1k")
      (footprint "eagle-import:R0402")
      (libsource (lib "eagle-import") (part "R-US_R0402"))
    )
    (comp (ref "R126")
      (value "33, 5%")
      (footprint "eagle-import:R0603")
      (libsource (lib "eagle-import") (part "R-US_R0603"))
    )
    (comp (ref "R127")
      (value "33, 5%")
      (footprint "eagle-import:R0603")
      (libsource (lib "eagle-import") (part "R-US_R0603"))
    )
    (comp (ref "R128")
      (value "33, 5%")
      (footprint "eagle-import:R0603")
      (libsource (lib "eagle-import") (part "R-US_R0603"))
    )
    (comp (ref "R129")
      (value "33, 5%")
      (footprint "eagle-import:R0603")
      (libsource (lib "eagle-import") (part "R-US_R0603"))
    )
    (comp (ref "R130")
      (value "33, 5%")
      (footprint "eagle-import:R0603")
      (libsource (lib "eagle-import") (part "R-US_R0603"))
    )
    (comp (ref "R131")
      (value "33, 5%")
      (footprint "eagle-import:R0603")
      (libsource (lib "eagle-import") (part "R-US_R0603"))
    )
    (comp (ref "R134")
      (value "33, 5%")
      (footprint "eagle-import:R0603")
      (libsource (lib "eagle-import") (part "R-US_R0603"))
    )
    (comp (ref "R135")
      (value "33, 5%")
      (footprint "eagle-import:R0603")
      (libsource (lib "eagle-import") (part "R-US_R0603"))
    )
    (comp (ref "R136")
      (value "33, 5%")
      (footprint "eagle-import:R0603")
      (libsource (lib "eagle-import") (part "R-US_R0603"))
    )
    (comp (ref "R140")
      (value "33, 5%")
      (footprint "eagle-import:R0402")
      (libsource (lib "eagle-import") (part "R-US_R0402"))
    )
    (comp (ref "R141")
      (value "33, 5%")
      (footprint "eagle-import:R0402")
      (libsource (lib "eagle-import") (part "R-US_R0402"))
    )
    (comp (ref "R142")
      (value "33, 5%")
      (footprint "eagle-import:R0402")
      (libsource (lib "eagle-import") (part "R-US_R0402"))
    )
    (comp (ref "R143")
      (value "33, 5%")
      (footprint "eagle-import:R0402")
      (libsource (lib "eagle-import") (part "R-US_R0402"))
    )
    (comp (ref "RESET")
      (value "MINI_PUSHBUTTON")
      (footprint "eagle-import:MINI_PUSHBUTTON")
      (libsource (lib "eagle-import") (part "MINI_PUSHBUTTON"))
    )
    (comp (ref "S2")
      (value "MINI_PUSHBUTTON")
      (footprint "eagle-import:MINI_PUSHBUTTON")
      (libsource (lib "eagle-import") (part "MINI_PUSHBUTTON"))
    )
    (comp (ref "T1")
      (value "MMBT2907")
      (footprint "eagle-import:SOT23-BEC")
      (libsource (lib "eagle-import") (part "MMBT2907SMDALT1"))
    )
    (comp (ref "T2")
      (value "DNP MMBT2907")
      (footprint "eagle-import:SOT23-BEC")
      (libsource (lib "eagle-import") (part "MMBT2907SMDALT1"))
    )
    (comp (ref "T3")
      (value "BSS138W-7-F")
      (footprint "eagle-import:SOT-323(DIODES)")
      (libsource (lib "eagle-import") (part "BSS138W-7-F"))
    )
    (comp (ref "T4")
      (value "BSS138W-7-F")
      (footprint "eagle-import:SOT-323(DIODES)")
      (libsource (lib "eagle-import") (part "BSS138W-7-F"))
    )
    (comp (ref "TP1")
      (value "TESTPAD/W_HOLE_1X1")
      (footprint "eagle-import:TESTPAD_W_HOLE_1X1")
      (libsource (lib "eagle-import") (part "TESTPAD/W_HOLE_1X1"))
    )
    (comp (ref "TP2")
      (value "TESTPAD/W_HOLE_1X1")
      (footprint "eagle-import:TESTPAD_W_HOLE_1X1")
      (libsource (lib "eagle-import") (part "TESTPAD/W_HOLE_1X1"))
    )
    (comp (ref "TP3")
      (value "TESTPAD/W_HOLE_1X1")
      (footprint "eagle-import:TESTPAD_W_HOLE_1X1")
      (libsource (lib "eagle-import") (part "TESTPAD/W_HOLE_1X1"))
    )
    (comp (ref "TP4")
      (value "TESTPAD/W_HOLE_1X1")
      (footprint "eagle-import:TESTPAD_W_HOLE_1X1")
      (libsource (lib "eagle-import") (part "TESTPAD/W_HOLE_1X1"))
    )
    (comp (ref "TP5")
      (value "TESTPAD/W_HOLE_1X1")
      (footprint "eagle-import:TESTPAD_W_HOLE_1X1")
      (libsource (lib "eagle-import") (part "TESTPAD/W_HOLE_1X1"))
    )
    (comp (ref "TP6")
      (value "PTR1B1,27")
      (footprint "eagle-import:B1,27")
      (libsource (lib "eagle-import") (part "PTR1B1,27"))
    )
    (comp (ref "TP12")
      (value "PTR1B1,27")
      (footprint "eagle-import:B1,27")
      (libsource (lib "eagle-import") (part "PTR1B1,27"))
    )
    (comp (ref "TP13")
      (value "PTR1B1,27")
      (footprint "eagle-import:B1,27")
      (libsource (lib "eagle-import") (part "PTR1B1,27"))
    )
    (comp (ref "TP14")
      (value "PTR1B1,27")
      (footprint "eagle-import:B1,27")
      (libsource (lib "eagle-import") (part "PTR1B1,27"))
    )
    (comp (ref "TP15")
      (value "PTR1B1,27")
      (footprint "eagle-import:B1,27")
      (libsource (lib "eagle-import") (part "PTR1B1,27"))
    )
    (comp (ref "TP16")
      (value "PTR1B1,27")
      (footprint "eagle-import:B1,27")
      (libsource (lib "eagle-import") (part "PTR1B1,27"))
    )
    (comp (ref "TP17")
      (value "PTR1B1,27")
      (footprint "eagle-import:B1,27")
      (libsource (lib "eagle-import") (part "PTR1B1,27"))
    )
    (comp (ref "TP18")
      (value "PTR1B1,27")
      (footprint "eagle-import:B1,27")
      (libsource (lib "eagle-import") (part "PTR1B1,27"))
    )
    (comp (ref "TP19")
      (value "PTR1B1,27")
      (footprint "eagle-import:B1,27")
      (libsource (lib "eagle-import") (part "PTR1B1,27"))
    )
    (comp (ref "TP23")
      (value "PTR1B1,27")
      (footprint "eagle-import:B1,27")
      (libsource (lib "eagle-import") (part "PTR1B1,27"))
    )
    (comp (ref "USR0")
      (value "LTST-C191TBKT")
      (footprint "eagle-import:0603-LED")
      (libsource (lib "eagle-import") (part "LED-(INCH)-0603"))
    )
    (comp (ref "USR1")
      (value "LTST-C191TBKT")
      (footprint "eagle-import:0603-LED")
      (libsource (lib "eagle-import") (part "LED-(INCH)-0603"))
    )
    (comp (ref "USR2")
      (value "LTST-C191TBKT")
      (footprint "eagle-import:0603-LED")
      (libsource (lib "eagle-import") (part "LED-(INCH)-0603"))
    )
    (comp (ref "USR3")
      (value "LTST-C191TBKT")
      (footprint "eagle-import:0603-LED")
      (libsource (lib "eagle-import") (part "LED-(INCH)-0603"))
    )
    (comp (ref "WL")
      (value "LTST-C191TBKT")
      (footprint "eagle-import:0603-LED")
      (libsource (lib "eagle-import") (part "LED-(INCH)-0603"))
    )
    (comp (ref "X1")
      (value "1X6-(INCH)-0.1-TH")
      (footprint "eagle-import:TH-1X6")
      (libsource (lib "eagle-import") (part "1X6-(INCH)-0.1-TH"))
    )
    (comp (ref "X2")
      (value "SCHA5B0200")
      (footprint "eagle-import:SCHA5B0200")
      (libsource (lib "eagle-import") (part "SCHA5B0200(ALPS_USD)"))
    )
    (comp (ref "X3")
      (value "USB_HOST_W/CHASSIS_GND")
      (footprint "eagle-import:USB_HOST_HORIZONTAL_W_CHASSIS_GND")
      (libsource (lib "eagle-import") (part "USB_HOST_W/CHASSIS_GND"))
    )
    (comp (ref "X4")
      (value "10118192-0001LF")
      (footprint "eagle-import:10118192-0001LF(MICRO-USB-B-AMPHENOL-FCI)")
      (libsource (lib "eagle-import") (part "10118192-0001LF"))
    )
    (comp (ref "X5")
      (value "10118241-001RLF")
      (footprint "eagle-import:HDMI-TYPE-D-10118241")
      (libsource (lib "eagle-import") (part "HDMI-TYPE-D-10118241"))
    )
    (comp (ref "X12")
      (value "PJ-102B_POWER_CON")
      (footprint "eagle-import:PJ-102B_POWER_CON")
      (libsource (lib "eagle-import") (part "PJ-102B_POWER_CON"))
    )
  )
  (nets
    (net (code "1") (name "/5V_IN") (class "Default")
      (node (ref "C19") (pin "1") (pinfunction "1_1") (pintype "passive"))
      (node (ref "D8") (pin "3") (pinfunction "CC_3") (pintype "passive"))
      (node (ref "FB1") (pin "2") (pinfunction "P$2_2") (pintype "bidirectional"))
      (node (ref "IC18") (pin "2") (pinfunction "IN_2") (pintype "bidirectional"))
      (node (ref "R95") (pin "1") (pinfunction "1_1") (pintype "passive"))
    )
    (net (code "2") (name "/12MHZ") (class "Default")
      (node (ref "FB6") (pin "2") (pinfunction "2_2") (pintype "passive"))
      (node (ref "IC9") (pin "27") (pinfunction "OSC_IN/AP3_27") (pintype "bidirectional"))
    )
    (net (code "3") (name "/12M_LOOP") (class "Default")
      (node (ref "IC13") (pin "2") (pinfunction "D_2") (pintype "bidirectional"))
      (node (ref "IC13") (pin "3") (pinfunction "Q#_3") (pintype "bidirectional"))
    )
    (net (code "4") (name "/32.768KHZ") (class "Default")
      (node (ref "OSC2") (pin "3") (pinfunction "OUT_3") (pintype "bidirectional"))
      (node (ref "R91") (pin "2") (pinfunction "2_2") (pintype "passive"))
    )
    (net (code "5") (name "/AIN0") (class "Default")
      (node (ref "IC1") (pin "B6") (pinfunction "AIN0_B6") (pintype "bidirectional"))
      (node (ref "P9") (pin "39") (pinfunction "39_39") (pintype "passive"))
    )
    (net (code "6") (name "/AIN1") (class "Default")
      (node (ref "IC1") (pin "C7") (pinfunction "AIN1_C7") (pintype "bidirectional"))
      (node (ref "P9") (pin "40") (pinfunction "40_40") (pintype "passive"))
    )
    (net (code "7") (name "/AIN2") (class "Default")
      (node (ref "IC1") (pin "B7") (pinfunction "AIN2_B7") (pintype "bidirectional"))
      (node (ref "P9") (pin "37") (pinfunction "37_37") (pintype "passive"))
    )
    (net (code "8") (name "/AIN3") (class "Default")
      (node (ref "IC1") (pin "A7") (pinfunction "AIN3_A7") (pintype "bidirectional"))
      (node (ref "P9") (pin "38") (pinfunction "38_38") (pintype "passive"))
    )
    (net (code "9") (name "/AIN4") (class "Default")
      (node (ref "IC1") (pin "C8") (pinfunction "AIN4_C8") (pintype "bidirectional"))
      (node (ref "P9") (pin "33") (pinfunction "33_33") (pintype "passive"))
    )
    (net (code "10") (name "/AIN5") (class "Default")
      (node (ref "IC1") (pin "B8") (pinfunction "AIN5_B8") (pintype "bidirectional"))
      (node (ref "P9") (pin "36") (pinfunction "36_36") (pintype "passive"))
    )
    (net (code "11") (name "/AIN6") (class "Default")
      (node (ref "IC1") (pin "A8") (pinfunction "AIN6_A8") (pintype "bidirectional"))
      (node (ref "P9") (pin "35") (pinfunction "35_35") (pintype "passive"))
    )
    (net (code "12") (name "/BAT_TEMP") (class "Default")
      (node (ref "IC1") (pin "W1") (pinfunction "BAT_TEMP_W1") (pintype "bidirectional"))
      (node (ref "TP4") (pin "P$1") (pinfunction "TP_P$1") (pintype "bidirectional"))
    )
    (net (code "13") (name "/BAT_VOLT") (class "Default")
      (node (ref "IC1") (pin "Y1") (pinfunction "BATT_VOLT_Y1") (pintype "bidirectional"))
      (node (ref "TP3") (pin "P$1") (pinfunction "TP_P$1") (pintype "bidirectional"))
    )
    (net (code "14") (name "/BT_EN") (class "Default")
      (node (ref "IC11") (pin "4") (pinfunction "A3_4") (pintype "bidirectional"))
      (node (ref "R11") (pin "1") (pinfunction "1_1") (pintype "passive"))
      (node (ref "T4") (pin "G") (pinfunction "G_G") (pintype "bidirectional"))
    )
    (net (code "15") (name "/BT_EN.SIP") (class "Default")
      (node (ref "IC1") (pin "K17") (pinfunction "MII1_TXD0_K17") (pintype "bidirectional"))
      (node (ref "R135") (pin "1") (pinfunction "1_1") (pintype "passive"))
    )
    (net (code "16") (name "/BT_HCI_CTS") (class "Default")
      (node (ref "IC11") (pin "8") (pinfunction "A7_8") (pintype "bidirectional"))
      (node (ref "R141") (pin "2") (pinfunction "2_2") (pintype "passive"))
    )
    (net (code "17") (name "/BT_HCI_CTS.SIP") (class "Default")
      (node (ref "IC1") (pin "M17") (pinfunction "MDIO_DATA_M17") (pintype "bidirectional"))
      (node (ref "IC11") (pin "15") (pinfunction "B5_15") (pintype "bidirectional"))
      (node (ref "R108") (pin "1") (pinfunction "1_1") (pintype "passive"))
    )
    (net (code "18") (name "/BT_HCI_RTS") (class "Default")
      (node (ref "IC11") (pin "6") (pinfunction "A5_6") (pintype "bidirectional"))
      (node (ref "R140") (pin "2") (pinfunction "2_2") (pintype "passive"))
    )
    (net (code "19") (name "/BT_HCI_RTS.SIP") (class "Default")
      (node (ref "IC1") (pin "M18") (pinfunction "MDIO_CLK_M18") (pintype "bidirectional"))
      (node (ref "IC11") (pin "13") (pinfunction "B7_13") (pintype "bidirectional"))
      (node (ref "R109") (pin "1") (pinfunction "1_1") (pintype "passive"))
    )
    (net (code "20") (name "/BT_HCI_RX") (class "Default")
      (node (ref "IC11") (pin "1") (pinfunction "A1_1") (pintype "bidirectional"))
      (node (ref "R143") (pin "2") (pinfunction "2_2") (pintype "passive"))
    )
    (net (code "21") (name "/BT_HCI_RX.SIP") (class "Default")
      (node (ref "IC1") (pin "L17") (pinfunction "MII1_RXD3_L17") (pintype "bidirectional"))
      (node (ref "IC11") (pin "14") (pinfunction "B6_14") (pintype "bidirectional"))
    )
    (net (code "22") (name "/BT_HCI_TX") (class "Default")
      (node (ref "IC11") (pin "7") (pinfunction "A6_7") (pintype "bidirectional"))
      (node (ref "R142") (pin "2") (pinfunction "2_2") (pintype "passive"))
    )
    (net (code "23") (name "/BT_HCI_TX.SIP") (class "Default")
      (node (ref "IC1") (pin "L16") (pinfunction "MII1_RXD2_L16") (pintype "bidirectional"))
      (node (ref "IC11") (pin "20") (pinfunction "B1_20") (pintype "bidirectional"))
    )
    (net (code "24") (name "/CEC") (class "Default")
      (node (ref "D1") (pin "C") (pinfunction "CATHODE_C") (pintype "bidirectional"))
      (node (ref "IC9") (pin "30") (pinfunction "CEC_30") (pintype "bidirectional"))
      (node (ref "X5") (pin "15") (pinfunction "CEC_15") (pintype "bidirectional"))
    )
    (net (code "25") (name "/CLKOUT2") (class "Default")
      (node (ref "FB7") (pin "1") (pinfunction "1_1") (pintype "passive"))
      (node (ref "IC11") (pin "16") (pinfunction "B4_16") (pintype "bidirectional"))
      (node (ref "P2") (pin "18") (pinfunction "EMU3_18") (pintype "bidirectional"))
      (node (ref "P9") (pin "41") (pinfunction "41_41") (pintype "passive"))
      (node (ref "R14") (pin "1") (pinfunction "1_1") (pintype "passive"))
    )
    (net (code "26") (name "/DVI_5V") (class "Default")
      (node (ref "F1") (pin "1") (pinfunction "1_1") (pintype "passive"))
      (node (ref "R115") (pin "1") (pinfunction "1_1") (pintype "passive"))
      (node (ref "R118") (pin "1") (pinfunction "1_1") (pintype "passive"))
      (node (ref "X5") (pin "19") (pinfunction "5V_19") (pintype "bidirectional"))
    )
    (net (code "27") (name "/EHRPWM1A") (class "Default")
      (node (ref "IC1") (pin "U14") (pinfunction "EHRPWM1A_U14") (pintype "bidirectional"))
      (node (ref "P9") (pin "14") (pinfunction "14_14") (pintype "passive"))
    )
    (net (code "28") (name "/EHRPWM1B") (class "Default")
      (node (ref "IC1") (pin "T14") (pinfunction "EHRPWM1B_T14") (pintype "bidirectional"))
      (node (ref "P9") (pin "16") (pinfunction "16_16") (pintype "passive"))
    )
    (net (code "29") (name "/EHRPWM2A") (class "Default")
      (node (ref "IC1") (pin "U10") (pinfunction "EHRPWM2A_U10") (pintype "bidirectional"))
      (node (ref "P8") (pin "19") (pinfunction "19_19") (pintype "passive"))
    )
    (net (code "30") (name "/EHRPWM2B") (class "Default")
      (node (ref "IC1") (pin "T10") (pinfunction "EHRPWM2B_T10") (pintype "bidirectional"))
      (node (ref "P8") (pin "13") (pinfunction "13_13") (pintype "passive"))
    )
    (net (code "31") (name "/EMMC_RSTN") (class "Default")
      (node (ref "IC22") (pin "K5") (pinfunction "RST#_K5") (pintype "bidirectional"))
      (node (ref "R29") (pin "1") (pinfunction "1_1") (pintype "passive"))
      (node (ref "R33") (pin "1") (pinfunction "1_1") (pintype "passive"))
    )
    (net (code "32") (name "/EXT_SWING") (class "Default")
      (node (ref "IC9") (pin "34") (pinfunction "EXT_SWING_34") (pintype "bidirectional"))
      (node (ref "R119") (pin "1") (pinfunction "1_1") (pintype "passive"))
    )
    (net (code "33") (name "/GPIO0_7") (class "Default")
      (node (ref "P9") (pin "42") (pinfunction "42_42") (pintype "passive"))
      (node (ref "R36") (pin "1") (pinfunction "1_1") (pintype "passive"))
      (node (ref "R38") (pin "1") (pinfunction "1_1") (pintype "passive"))
    )
    (net (code "34") (name "/GPIO0_26") (class "Default")
      (node (ref "IC1") (pin "T11") (pinfunction "GPIO0_26_T11") (pintype "bidirectional"))
      (node (ref "P8") (pin "14") (pinfunction "14_14") (pintype "passive"))
    )
    (net (code "35") (name "/GPIO0_27") (class "Default")
      (node (ref "IC1") (pin "U12") (pinfunction "GPIO0_27_U12") (pintype "bidirectional"))
      (node (ref "P8") (pin "17") (pinfunction "17_17") (pintype "passive"))
    )
    (net (code "36") (name "/GPIO1_12") (class "Default")
      (node (ref "IC1") (pin "T12") (pinfunction "GPIO1_12_T12") (pintype "bidirectional"))
      (node (ref "P8") (pin "12") (pinfunction "12_12") (pintype "passive"))
    )
    (net (code "37") (name "/GPIO1_13") (class "Default")
      (node (ref "IC1") (pin "R12") (pinfunction "GPIO1_13_R12") (pintype "bidirectional"))
      (node (ref "P8") (pin "11") (pinfunction "11_11") (pintype "passive"))
    )
    (net (code "38") (name "/GPIO1_14") (class "Default")
      (node (ref "IC1") (pin "V13") (pinfunction "GPIO1_14_V13") (pintype "bidirectional"))
      (node (ref "P8") (pin "16") (pinfunction "16_16") (pintype "passive"))
    )
    (net (code "39") (name "/GPIO1_15") (class "Default")
      (node (ref "IC1") (pin "U13") (pinfunction "GPIO1_15_U13") (pintype "bidirectional"))
      (node (ref "P8") (pin "15") (pinfunction "15_15") (pintype "passive"))
    )
    (net (code "40") (name "/GPIO1_16") (class "Default")
      (node (ref "P9") (pin "15") (pinfunction "15_15") (pintype "passive"))
      (node (ref "R54") (pin "1") (pinfunction "1_1") (pintype "passive"))
    )
    (net (code "41") (name "/GPIO1_16.SIP") (class "Default")
      (node (ref "IC1") (pin "R13") (pinfunction "GPIO1_16_R13") (pintype "bidirectional"))
      (node (ref "R54") (pin "2") (pinfunction "2_2") (pintype "passive"))
    )
    (net (code "42") (name "/GPIO1_17") (class "Default")
      (node (ref "IC1") (pin "V14") (pinfunction "GPIO1_17_V14") (pintype "bidirectional"))
      (node (ref "P9") (pin "23") (pinfunction "23_23") (pintype "passive"))
    )
    (net (code "43") (name "/GPIO1_28") (class "Default")
      (node (ref "IC1") (pin "U18") (pinfunction "GPIO1_28_U18") (pintype "bidirectional"))
      (node (ref "P9") (pin "12") (pinfunction "12_12") (pintype "passive"))
    )
    (net (code "44") (name "/GPIO1_29") (class "Default")
      (node (ref "IC1") (pin "V6") (pinfunction "GPIO1_29_V6") (pintype "bidirectional"))
      (node (ref "P8") (pin "26") (pinfunction "26_26") (pintype "passive"))
    )
    (net (code "45") (name "/GPIO2_0.SIP") (class "Default")
      (node (ref "IC1") (pin "T13") (pinfunction "GPIO2_0_T13") (pintype "bidirectional"))
    )
    (net (code "46") (name "/GPIO2_1") (class "Default")
      (node (ref "IC1") (pin "V12") (pinfunction "GPIO2_1_V12") (pintype "bidirectional"))
      (node (ref "P8") (pin "18") (pinfunction "18_18") (pintype "passive"))
    )
    (net (code "47") (name "/GPIO3_19") (class "Default")
      (node (ref "IC1") (pin "C13") (pinfunction "GPIO3_19_C13") (pintype "bidirectional"))
      (node (ref "P9") (pin "27") (pinfunction "27_27") (pintype "passive"))
    )
    (net (code "48") (name "/GPIO3_21") (class "Default")
      (node (ref "IC1") (pin "A14") (pinfunction "GPIO3_21_A14") (pintype "bidirectional"))
      (node (ref "P9") (pin "25") (pinfunction "25_25") (pintype "passive"))
      (node (ref "R110") (pin "2") (pinfunction "2_2") (pintype "passive"))
    )
    (net (code "49") (name "/HDMICLK_DIS#") (class "Default")
      (node (ref "IC1") (pin "V17") (pinfunction "(HDMICLK_DISN)GPIO1_27_V17") (pintype "bidirectional"))
      (node (ref "OSC1") (pin "1") (pinfunction "INH#_1") (pintype "bidirectional"))
    )
    (net (code "50") (name "/HDMI_INT") (class "Default")
      (node (ref "IC1") (pin "U16") (pinfunction "(HDMI_INT)GPIO1_25_U16") (pintype "bidirectional"))
      (node (ref "IC9") (pin "50") (pinfunction "INT_50") (pintype "bidirectional"))
      (node (ref "R121") (pin "2") (pinfunction "2_2") (pintype "passive"))
    )
    (net (code "51") (name "/HPD") (class "Default")
      (node (ref "IC9") (pin "31") (pinfunction "HPD_31") (pintype "bidirectional"))
      (node (ref "X5") (pin "1") (pinfunction "HOT.PLUG.DETECT_1") (pintype "bidirectional"))
    )
    (net (code "52") (name "/I2C0_SCL") (class "Default")
      (node (ref "IC1") (pin "C16") (pinfunction "I2C0_SCL_C16") (pintype "bidirectional"))
      (node (ref "IC1") (pin "C20") (pinfunction "PMIC_I2C_SCL_C20") (pintype "bidirectional"))
      (node (ref "IC4") (pin "1") (pinfunction "SCL_1") (pintype "bidirectional"))
      (node (ref "IC9") (pin "52") (pinfunction "CSCL_52") (pintype "bidirectional"))
      (node (ref "R41") (pin "2") (pinfunction "2_2") (pintype "passive"))
    )
    (net (code "53") (name "/I2C0_SDA") (class "Default")
      (node (ref "IC1") (pin "C17") (pinfunction "I2C0_SDA_C17") (pintype "bidirectional"))
      (node (ref "IC1") (pin "C19") (pinfunction "PMIC_I2C_SDA_C19") (pintype "bidirectional"))
      (node (ref "IC4") (pin "3") (pinfunction "SDA_3") (pintype "bidirectional"))
      (node (ref "IC9") (pin "51") (pinfunction "CSDA_51") (pintype "bidirectional"))
      (node (ref "R42") (pin "2") (pinfunction "2_2") (pintype "passive"))
    )
    (net (code "54") (name "/I2C1_SCL") (class "Default")
      (node (ref "IC1") (pin "A16") (pinfunction "I2C1_SCL_A16") (pintype "bidirectional"))
      (node (ref "P9") (pin "17") (pinfunction "17_17") (pintype "passive"))
    )
    (net (code "55") (name "/I2C1_SDA") (class "Default")
      (node (ref "IC1") (pin "B16") (pinfunction "I2C1_SDA_B16") (pintype "bidirectional"))
      (node (ref "P9") (pin "18") (pinfunction "18_18") (pintype "passive"))
    )
    (net (code "56") (name "/I2C2_SCL") (class "Default")
      (node (ref "IC1") (pin "D17") (pinfunction "I2C2_SCL_D17") (pintype "bidirectional"))
      (node (ref "P9") (pin "19") (pinfunction "19_19") (pintype "passive"))
    )
    (net (code "57") (name "/I2C2_SDA") (class "Default")
      (node (ref "IC1") (pin "D18") (pinfunction "I2C2_SDA_D18") (pintype "bidirectional"))
      (node (ref "P9") (pin "20") (pinfunction "20_20") (pintype "passive"))
    )
    (net (code "58") (name "/JTAG_EMU0") (class "Default")
      (node (ref "IC1") (pin "C14") (pinfunction "JTAG_EMU0_C14") (pintype "bidirectional"))
      (node (ref "P2") (pin "13") (pinfunction "EMU0_13") (pintype "bidirectional"))
      (node (ref "R43") (pin "2") (pinfunction "2_2") (pintype "passive"))
    )
    (net (code "59") (name "/JTAG_EMU1") (class "Default")
      (node (ref "IC1") (pin "B14") (pinfunction "JTAG_EMU1_B14") (pintype "bidirectional"))
      (node (ref "P2") (pin "14") (pinfunction "EMU1_14") (pintype "bidirectional"))
      (node (ref "R53") (pin "2") (pinfunction "2_2") (pintype "passive"))
    )
    (net (code "60") (name "/JTAG_TCK") (class "Default")
      (node (ref "IC1") (pin "A12") (pinfunction "JTAG_TCK_A12") (pintype "bidirectional"))
      (node (ref "P2") (pin "11") (pinfunction "TCK_11") (pintype "bidirectional"))
      (node (ref "P2") (pin "9") (pinfunction "TCKRTN_9") (pintype "bidirectional"))
    )
    (net (code "61") (name "/JTAG_TDI") (class "Default")
      (node (ref "IC1") (pin "B11") (pinfunction "JTAG_TDI_B11") (pintype "bidirectional"))
      (node (ref "P2") (pin "3") (pinfunction "TDI_3") (pintype "bidirectional"))
    )
    (net (code "62") (name "/JTAG_TDO") (class "Default")
      (node (ref "IC1") (pin "A11") (pinfunction "JTAG_TDO_A11") (pintype "bidirectional"))
      (node (ref "P2") (pin "7") (pinfunction "TDO_7") (pintype "bidirectional"))
    )
    (net (code "63") (name "/JTAG_TMS") (class "Default")
      (node (ref "IC1") (pin "C11") (pinfunction "JTAG_TMS_C11") (pintype "bidirectional"))
      (node (ref "P2") (pin "1") (pinfunction "TMS_1") (pintype "bidirectional"))
    )
    (net (code "64") (name "/JTAG_TRSTN") (class "Default")
      (node (ref "IC1") (pin "B10") (pinfunction "JTAG_TRSTN_B10") (pintype "bidirectional"))
      (node (ref "P2") (pin "2") (pinfunction "TRST#_2") (pintype "bidirectional"))
      (node (ref "R52") (pin "1") (pinfunction "1_1") (pintype "passive"))
    )
    (net (code "65") (name "/LCD.CLOCK") (class "Default")
      (node (ref "IC9") (pin "4") (pinfunction "PCLK_4") (pintype "bidirectional"))
      (node (ref "P8") (pin "28") (pinfunction "28_28") (pintype "passive"))
      (node (ref "R34") (pin "1") (pinfunction "1_1") (pintype "passive"))
    )
    (net (code "66") (name "/LCD.D0.B0--B3") (class "Default")
      (node (ref "C42") (pin "1") (pinfunction "1_1") (pintype "passive"))
      (node (ref "IC1") (pin "R1") (pinfunction "LCD_DATA0_R1") (pintype "bidirectional"))
      (node (ref "IC9") (pin "15") (pinfunction "VPC[3]_15") (pintype "bidirectional"))
      (node (ref "P8") (pin "45") (pinfunction "45_45") (pintype "passive"))
      (node (ref "R87") (pin "2") (pinfunction "2_2") (pintype "passive"))
    )
    (net (code "67") (name "/LCD.D1.B1--B4") (class "Default")
      (node (ref "C41") (pin "1") (pinfunction "1_1") (pintype "passive"))
      (node (ref "IC1") (pin "R2") (pinfunction "LCD_DATA1_R2") (pintype "bidirectional"))
      (node (ref "IC9") (pin "13") (pinfunction "VPC[4]_13") (pintype "bidirectional"))
      (node (ref "P8") (pin "46") (pinfunction "46_46") (pintype "passive"))
      (node (ref "R85") (pin "2") (pinfunction "2_2") (pintype "passive"))
    )
    (net (code "68") (name "/LCD.D2.B2--B5") (class "Default")
      (node (ref "C40") (pin "1") (pinfunction "1_1") (pintype "passive"))
      (node (ref "IC1") (pin "R3") (pinfunction "LCD_DATA2_R3") (pintype "bidirectional"))
      (node (ref "IC9") (pin "12") (pinfunction "VPC[5]_12") (pintype "bidirectional"))
      (node (ref "P8") (pin "43") (pinfunction "43_43") (pintype "passive"))
      (node (ref "R82") (pin "1") (pinfunction "1_1") (pintype "passive"))
      (node (ref "R88") (pin "1") (pinfunction "1_1") (pintype "passive"))
    )
    (net (code "69") (name "/LCD.D3.B3--B6") (class "Default")
      (node (ref "C39") (pin "1") (pinfunction "1_1") (pintype "passive"))
      (node (ref "IC1") (pin "R4") (pinfunction "LCD_DATA3_R4") (pintype "bidirectional"))
      (node (ref "IC9") (pin "11") (pinfunction "VPC[6]_11") (pintype "bidirectional"))
      (node (ref "P8") (pin "44") (pinfunction "44_44") (pintype "passive"))
      (node (ref "R80") (pin "1") (pinfunction "1_1") (pintype "passive"))
    )
    (net (code "70") (name "/LCD.D4.B4--B7") (class "Default")
      (node (ref "C38") (pin "1") (pinfunction "1_1") (pintype "passive"))
      (node (ref "IC1") (pin "T1") (pinfunction "LCD_DATA4_T1") (pintype "bidirectional"))
      (node (ref "IC9") (pin "10") (pinfunction "VPC[7]_10") (pintype "bidirectional"))
      (node (ref "P8") (pin "41") (pinfunction "41_41") (pintype "passive"))
      (node (ref "R78") (pin "1") (pinfunction "1_1") (pintype "passive"))
    )
    (net (code "71") (name "/LCD.D5.G0--G2") (class "Default")
      (node (ref "C37") (pin "1") (pinfunction "1_1") (pintype "passive"))
      (node (ref "IC1") (pin "T2") (pinfunction "LCD_DATA5_T2") (pintype "bidirectional"))
      (node (ref "IC9") (pin "7") (pinfunction "VPB[2]_7") (pintype "bidirectional"))
      (node (ref "P8") (pin "42") (pinfunction "42_42") (pintype "passive"))
      (node (ref "R76") (pin "1") (pinfunction "1_1") (pintype "passive"))
    )
    (net (code "72") (name "/LCD.D6.G1--G3") (class "Default")
      (node (ref "C36") (pin "1") (pinfunction "1_1") (pintype "passive"))
      (node (ref "IC1") (pin "T3") (pinfunction "LCD_DATA6_T3") (pintype "bidirectional"))
      (node (ref "IC9") (pin "6") (pinfunction "VPB[3]_6") (pintype "bidirectional"))
      (node (ref "P8") (pin "39") (pinfunction "39_39") (pintype "passive"))
      (node (ref "R75") (pin "2") (pinfunction "2_2") (pintype "passive"))
    )
    (net (code "73") (name "/LCD.D7.G2--G4") (class "Default")
      (node (ref "C35") (pin "1") (pinfunction "1_1") (pintype "passive"))
      (node (ref "IC1") (pin "T4") (pinfunction "LCD_DATA7_T4") (pintype "bidirectional"))
      (node (ref "IC9") (pin "3") (pinfunction "VPB[4]_3") (pintype "bidirectional"))
      (node (ref "P8") (pin "40") (pinfunction "40_40") (pintype "passive"))
      (node (ref "R73") (pin "2") (pinfunction "2_2") (pintype "passive"))
    )
    (net (code "74") (name "/LCD.D8.G3--G5") (class "Default")
      (node (ref "C34") (pin "1") (pinfunction "1_1") (pintype "passive"))
      (node (ref "IC1") (pin "U1") (pinfunction "LCD_DATA8_U1") (pintype "bidirectional"))
      (node (ref "IC9") (pin "2") (pinfunction "VPB[5]_2") (pintype "bidirectional"))
      (node (ref "P8") (pin "37") (pinfunction "37_37") (pintype "passive"))
      (node (ref "R71") (pin "2") (pinfunction "2_2") (pintype "passive"))
    )
    (net (code "75") (name "/LCD.D9.G4--G6") (class "Default")
      (node (ref "C33") (pin "1") (pinfunction "1_1") (pintype "passive"))
      (node (ref "IC1") (pin "U2") (pinfunction "LCD_DATA9_U2") (pintype "bidirectional"))
      (node (ref "IC9") (pin "1") (pinfunction "VPB[6]_1") (pintype "bidirectional"))
      (node (ref "P8") (pin "38") (pinfunction "38_38") (pintype "passive"))
      (node (ref "R69") (pin "2") (pinfunction "2_2") (pintype "passive"))
    )
    (net (code "76") (name "/LCD.D10.G5--G7") (class "Default")
      (node (ref "C32") (pin "1") (pinfunction "1_1") (pintype "passive"))
      (node (ref "IC1") (pin "U3") (pinfunction "LCD_DATA10_U3") (pintype "bidirectional"))
      (node (ref "IC9") (pin "64") (pinfunction "VPB[7]_64") (pintype "bidirectional"))
      (node (ref "P8") (pin "36") (pinfunction "36_36") (pintype "passive"))
      (node (ref "R67") (pin "2") (pinfunction "2_2") (pintype "passive"))
    )
    (net (code "77") (name "/LCD.D11.R0--R3") (class "Default")
      (node (ref "C31") (pin "1") (pinfunction "1_1") (pintype "passive"))
      (node (ref "IC1") (pin "U4") (pinfunction "LCD_DATA11_U4") (pintype "bidirectional"))
      (node (ref "IC9") (pin "60") (pinfunction "VPA[3]_60") (pintype "bidirectional"))
      (node (ref "P8") (pin "34") (pinfunction "34_34") (pintype "passive"))
      (node (ref "R65") (pin "2") (pinfunction "2_2") (pintype "passive"))
    )
    (net (code "78") (name "/LCD.D12.R1--R4") (class "Default")
      (node (ref "C30") (pin "1") (pinfunction "1_1") (pintype "passive"))
      (node (ref "IC1") (pin "V2") (pinfunction "LCD_DATA12_V2") (pintype "bidirectional"))
      (node (ref "IC9") (pin "59") (pinfunction "VPA[4]_59") (pintype "bidirectional"))
      (node (ref "P8") (pin "35") (pinfunction "35_35") (pintype "passive"))
      (node (ref "R63") (pin "2") (pinfunction "2_2") (pintype "passive"))
    )
    (net (code "79") (name "/LCD.D13.R2--R5") (class "Default")
      (node (ref "C29") (pin "1") (pinfunction "1_1") (pintype "passive"))
      (node (ref "IC1") (pin "V3") (pinfunction "LCD_DATA13_V3") (pintype "bidirectional"))
      (node (ref "IC9") (pin "58") (pinfunction "VPA[5]_58") (pintype "bidirectional"))
      (node (ref "P8") (pin "33") (pinfunction "33_33") (pintype "passive"))
      (node (ref "R61") (pin "2") (pinfunction "2_2") (pintype "passive"))
    )
    (net (code "80") (name "/LCD.D14.R3--R6") (class "Default")
      (node (ref "C28") (pin "1") (pinfunction "1_1") (pintype "passive"))
      (node (ref "IC1") (pin "V4") (pinfunction "LCD_DATA14_V4") (pintype "bidirectional"))
      (node (ref "IC9") (pin "57") (pinfunction "VPA[6]_57") (pintype "bidirectional"))
      (node (ref "P8") (pin "31") (pinfunction "31_31") (pintype "passive"))
      (node (ref "R58") (pin "1") (pinfunction "1_1") (pintype "passive"))
    )
    (net (code "81") (name "/LCD.D15.R4--R7") (class "Default")
      (node (ref "C27") (pin "1") (pinfunction "1_1") (pintype "passive"))
      (node (ref "IC1") (pin "T5") (pinfunction "LCD_DATA15_T5") (pintype "bidirectional"))
      (node (ref "IC9") (pin "56") (pinfunction "VPA[7]_56") (pintype "bidirectional"))
      (node (ref "P8") (pin "32") (pinfunction "32_32") (pintype "passive"))
      (node (ref "R57") (pin "2") (pinfunction "2_2") (pintype "passive"))
    )
    (net (code "82") (name "/LCD.ENABLE") (class "Default")
      (node (ref "IC9") (pin "20") (pinfunction "DE/FREF_20") (pintype "bidirectional"))
      (node (ref "P8") (pin "30") (pinfunction "30_30") (pintype "passive"))
      (node (ref "R39") (pin "1") (pinfunction "1_1") (pintype "passive"))
    )
    (net (code "83") (name "/LCD.HSYNC") (class "Default")
      (node (ref "IC9") (pin "22") (pinfunction "HSYNC/HREF_22") (pintype "bidirectional"))
      (node (ref "P8") (pin "29") (pinfunction "29_29") (pintype "passive"))
      (node (ref "R37") (pin "1") (pinfunction "1_1") (pintype "passive"))
    )
    (net (code "84") (name "/LCD.VSYNC") (class "Default")
      (node (ref "IC9") (pin "21") (pinfunction "VSYNC/VREF_21") (pintype "bidirectional"))
      (node (ref "P8") (pin "27") (pinfunction "27_27") (pintype "passive"))
      (node (ref "R35") (pin "1") (pinfunction "1_1") (pintype "passive"))
    )
    (net (code "85") (name "/LDO_PGOOD") (class "Default")
      (node (ref "IC1") (pin "B20") (pinfunction "PMIC_LDO_PGOOD_B20") (pintype "bidirectional"))
      (node (ref "IC1") (pin "B5") (pinfunction "RTC_PORZ_B5") (pintype "bidirectional"))
    )
    (net (code "86") (name "/LS_BUF_OE") (class "Default")
      (node (ref "IC1") (pin "L18") (pinfunction "MII_RXCLK_L18") (pintype "bidirectional"))
      (node (ref "R131") (pin "2") (pinfunction "2_2") (pintype "passive"))
    )
    (net (code "87") (name "/MCU.LCD.CLK") (class "Default")
      (node (ref "IC1") (pin "V5") (pinfunction "LCD_PCLK_V5") (pintype "bidirectional"))
      (node (ref "R34") (pin "2") (pinfunction "2_2") (pintype "passive"))
    )
    (net (code "88") (name "/MCU.LCD.EN") (class "Default")
      (node (ref "IC1") (pin "R6") (pinfunction "LCD_DE_R6") (pintype "bidirectional"))
      (node (ref "R39") (pin "2") (pinfunction "2_2") (pintype "passive"))
    )
    (net (code "89") (name "/MCU.LCD.HS") (class "Default")
      (node (ref "IC1") (pin "R5") (pinfunction "LCD_HSYNC_R5") (pintype "bidirectional"))
      (node (ref "R37") (pin "2") (pinfunction "2_2") (pintype "passive"))
    )
    (net (code "90") (name "/MCU.LCD.VS") (class "Default")
      (node (ref "IC1") (pin "U5") (pinfunction "LCD_VSYNC_U5") (pintype "bidirectional"))
      (node (ref "R35") (pin "2") (pinfunction "2_2") (pintype "passive"))
    )
    (net (code "91") (name "/MMC1_CLK") (class "Default")
      (node (ref "IC1") (pin "U9") (pinfunction "MMC1_CLK_U9") (pintype "bidirectional"))
      (node (ref "IC22") (pin "M6") (pinfunction "CLK_M6") (pintype "bidirectional"))
      (node (ref "P8") (pin "21") (pinfunction "21_21") (pintype "passive"))
      (node (ref "R31") (pin "1") (pinfunction "1_1") (pintype "passive"))
    )
    (net (code "92") (name "/MMC1_CMD") (class "Default")
      (node (ref "IC1") (pin "V9") (pinfunction "MMC1_CMD_V9") (pintype "bidirectional"))
      (node (ref "IC22") (pin "M5") (pinfunction "CMD_M5") (pintype "bidirectional"))
      (node (ref "P8") (pin "20") (pinfunction "20_20") (pintype "passive"))
      (node (ref "R30") (pin "1") (pinfunction "1_1") (pintype "passive"))
    )
    (net (code "93") (name "/MMC1_DAT0") (class "Default")
      (node (ref "IC1") (pin "U7") (pinfunction "MMC1_DAT0_U7") (pintype "bidirectional"))
      (node (ref "IC22") (pin "A3") (pinfunction "DAT0_A3") (pintype "bidirectional"))
      (node (ref "P8") (pin "25") (pinfunction "25_25") (pintype "passive"))
      (node (ref "R12") (pin "1") (pinfunction "1_1") (pintype "passive"))
    )
    (net (code "94") (name "/MMC1_DAT1") (class "Default")
      (node (ref "IC1") (pin "V7") (pinfunction "MMC1_DAT1_V7") (pintype "bidirectional"))
      (node (ref "IC22") (pin "A4") (pinfunction "DAT1_A4") (pintype "bidirectional"))
      (node (ref "P8") (pin "24") (pinfunction "24_24") (pintype "passive"))
      (node (ref "R13") (pin "1") (pinfunction "1_1") (pintype "passive"))
    )
    (net (code "95") (name "/MMC1_DAT2") (class "Default")
      (node (ref "IC1") (pin "R8") (pinfunction "MMC1_DAT2_R8") (pintype "bidirectional"))
      (node (ref "IC22") (pin "A5") (pinfunction "DAT2_A5") (pintype "bidirectional"))
      (node (ref "P8") (pin "5") (pinfunction "5_5") (pintype "passive"))
      (node (ref "R16") (pin "1") (pinfunction "1_1") (pintype "passive"))
    )
    (net (code "96") (name "/MMC1_DAT3") (class "Default")
      (node (ref "IC1") (pin "T8") (pinfunction "MMC1_DAT3_T8") (pintype "bidirectional"))
      (node (ref "IC22") (pin "B2") (pinfunction "DAT3_B2") (pintype "bidirectional"))
      (node (ref "P8") (pin "6") (pinfunction "6_6") (pintype "passive"))
      (node (ref "R18") (pin "1") (pinfunction "1_1") (pintype "passive"))
    )
    (net (code "97") (name "/MMC1_DAT4") (class "Default")
      (node (ref "IC1") (pin "U8") (pinfunction "MMC1_DAT4_U8") (pintype "bidirectional"))
      (node (ref "IC22") (pin "B3") (pinfunction "DAT4_B3") (pintype "bidirectional"))
      (node (ref "P8") (pin "23") (pinfunction "23_23") (pintype "passive"))
      (node (ref "R20") (pin "1") (pinfunction "1_1") (pintype "passive"))
    )
    (net (code "98") (name "/MMC1_DAT5") (class "Default")
      (node (ref "IC1") (pin "V8") (pinfunction "MMC1_DAT5_V8") (pintype "bidirectional"))
      (node (ref "IC22") (pin "B4") (pinfunction "DAT5_B4") (pintype "bidirectional"))
      (node (ref "P8") (pin "22") (pinfunction "22_22") (pintype "passive"))
      (node (ref "R23") (pin "1") (pinfunction "1_1") (pintype "passive"))
    )
    (net (code "99") (name "/MMC1_DAT6") (class "Default")
      (node (ref "IC1") (pin "R9") (pinfunction "MMC1_DAT6_R9") (pintype "bidirectional"))
      (node (ref "IC22") (pin "B5") (pinfunction "DAT6_B5") (pintype "bidirectional"))
      (node (ref "P8") (pin "3") (pinfunction "3_3") (pintype "passive"))
      (node (ref "R25") (pin "1") (pinfunction "1_1") (pintype "passive"))
    )
    (net (code "100") (name "/MMC1_DAT7") (class "Default")
      (node (ref "IC1") (pin "T9") (pinfunction "MMC1_DAT7_T9") (pintype "bidirectional"))
      (node (ref "IC22") (pin "B6") (pinfunction "DAT7_B6") (pintype "bidirectional"))
      (node (ref "P8") (pin "4") (pinfunction "4_4") (pintype "passive"))
      (node (ref "R28") (pin "1") (pinfunction "1_1") (pintype "passive"))
    )
    (net (code "101") (name "/NC1") (class "Default")
      (node (ref "IC1") (pin "K16") (pinfunction "MII1_TXD1_K16") (pintype "bidirectional"))
    )
    (net (code "102") (name "/NC2") (class "Default")
      (node (ref "IC1") (pin "H17") (pinfunction "MII1_CRS_DV_H17") (pintype "bidirectional"))
    )
    (net (code "103") (name "/NC3") (class "Default")
      (node (ref "IC1") (pin "M16") (pinfunction "MII1_RXD0_M16") (pintype "bidirectional"))
    )
    (net (code "104") (name "/NC4") (class "Default")
      (node (ref "IC1") (pin "J15") (pinfunction "MII1_RXERR_J15") (pintype "bidirectional"))
    )
    (net (code "105") (name "/PMIC_INT") (class "Default")
      (node (ref "IC1") (pin "B18") (pinfunction "EXTIN_B18") (pintype "bidirectional"))
      (node (ref "IC1") (pin "B19") (pinfunction "PMIC_INTN_B19") (pintype "bidirectional"))
    )
    (net (code "106") (name "/PMIC_NWAKEUP") (class "Default")
      (node (ref "IC1") (pin "A19") (pinfunction "PMIC_WAKEUPN_A19") (pintype "bidirectional"))
      (node (ref "IC1") (pin "C5") (pinfunction "EXT_WAKEUP_C5") (pintype "bidirectional"))
    )
    (net (code "107") (name "/PMIC_PGOOD") (class "Default")
      (node (ref "IC1") (pin "A20") (pinfunction "PMIC_PGOOD_A20") (pintype "bidirectional"))
      (node (ref "IC1") (pin "B15") (pinfunction "PORZ_B15") (pintype "bidirectional"))
      (node (ref "IC2") (pin "2") (pinfunction "A_2") (pintype "bidirectional"))
    )
    (net (code "108") (name "/PWR_BUT") (class "Default")
      (node (ref "IC1") (pin "D20") (pinfunction "PWR_BUT_D20") (pintype "bidirectional"))
      (node (ref "P9") (pin "9") (pinfunction "9_9") (pintype "passive"))
      (node (ref "POWER") (pin "3") (pinfunction "3_3") (pintype "bidirectional"))
      (node (ref "POWER") (pin "4") (pinfunction "4_4") (pintype "bidirectional"))
    )
    (net (code "109") (name "/RX<-TX") (class "Default")
      (node (ref "IC17") (pin "3") (pinfunction "2Y_3") (pintype "bidirectional"))
      (node (ref "X1") (pin "5") (pinfunction "5_5") (pintype "passive"))
    )
    (net (code "110") (name "/SD.CD") (class "Default")
      (node (ref "IC1") (pin "C15") (pinfunction "MMC0_CD_C15") (pintype "bidirectional"))
      (node (ref "P2") (pin "19") (pinfunction "EMU4_19") (pintype "bidirectional"))
      (node (ref "R7") (pin "1") (pinfunction "1_1") (pintype "passive"))
      (node (ref "X2") (pin "CD") (pinfunction "CD#_CD") (pintype "bidirectional"))
    )
    (net (code "111") (name "/SD.CLK") (class "Default")
      (node (ref "IC1") (pin "G17") (pinfunction "MMC0_CLK0_G17") (pintype "bidirectional"))
      (node (ref "R3") (pin "1") (pinfunction "1_1") (pintype "passive"))
      (node (ref "X2") (pin "5") (pinfunction "CLK_5") (pintype "bidirectional"))
    )
    (net (code "112") (name "/SD.CMD") (class "Default")
      (node (ref "IC1") (pin "G18") (pinfunction "MMC0_CMD_G18") (pintype "bidirectional"))
      (node (ref "R4") (pin "1") (pinfunction "1_1") (pintype "passive"))
      (node (ref "X2") (pin "3") (pinfunction "CMD/DI_3") (pintype "bidirectional"))
    )
    (net (code "113") (name "/SD.D0") (class "Default")
      (node (ref "IC1") (pin "G16") (pinfunction "MMC0_DAT0_G16") (pintype "bidirectional"))
      (node (ref "R2") (pin "1") (pinfunction "1_1") (pintype "passive"))
      (node (ref "X2") (pin "7") (pinfunction "DAT0/DO_7") (pintype "bidirectional"))
    )
    (net (code "114") (name "/SD.D1") (class "Default")
      (node (ref "IC1") (pin "G15") (pinfunction "MMC0_DAT1_G15") (pintype "bidirectional"))
      (node (ref "R1") (pin "1") (pinfunction "1_1") (pintype "passive"))
      (node (ref "X2") (pin "8") (pinfunction "DAT1_8") (pintype "bidirectional"))
    )
    (net (code "115") (name "/SD.D2") (class "Default")
      (node (ref "IC1") (pin "F18") (pinfunction "MMC0_DAT2_F18") (pintype "bidirectional"))
      (node (ref "R6") (pin "1") (pinfunction "1_1") (pintype "passive"))
      (node (ref "X2") (pin "1") (pinfunction "DAT2_1") (pintype "bidirectional"))
    )
    (net (code "116") (name "/SD.D3") (class "Default")
      (node (ref "IC1") (pin "F17") (pinfunction "MMC0_DAT3_F17") (pintype "bidirectional"))
      (node (ref "R5") (pin "1") (pinfunction "1_1") (pintype "passive"))
      (node (ref "X2") (pin "2") (pinfunction "DAT3/CS_2") (pintype "bidirectional"))
    )
    (net (code "117") (name "/SELECT_5V") (class "Default")
      (node (ref "D2") (pin "K") (pinfunction "K_K") (pintype "bidirectional"))
      (node (ref "D3") (pin "K") (pinfunction "K_K") (pintype "bidirectional"))
      (node (ref "D4") (pin "K") (pinfunction "K_K") (pintype "bidirectional"))
      (node (ref "FB1") (pin "1") (pinfunction "P$1_1") (pintype "bidirectional"))
      (node (ref "R97") (pin "1") (pinfunction "1_1") (pintype "passive"))
      (node (ref "TP23") (pin "TP") (pinfunction "TP_TP") (pintype "input"))
    )
    (net (code "118") (name "/SLOW_CLK") (class "Default")
      (node (ref "IC11") (pin "5") (pinfunction "A4_5") (pintype "bidirectional"))
      (node (ref "R91") (pin "1") (pinfunction "1_1") (pintype "passive"))
    )
    (net (code "119") (name "/SPI1_CS0") (class "Default")
      (node (ref "IC1") (pin "C12") (pinfunction "SPI1_CS0_C12") (pintype "bidirectional"))
      (node (ref "IC9") (pin "25") (pinfunction "AP1_25") (pintype "bidirectional"))
      (node (ref "P9") (pin "28") (pinfunction "28_28") (pintype "passive"))
    )
    (net (code "120") (name "/SPI1_D0") (class "Default")
      (node (ref "IC1") (pin "B13") (pinfunction "SPI1_D0_B13") (pintype "bidirectional"))
      (node (ref "IC9") (pin "24") (pinfunction "AP0_24") (pintype "bidirectional"))
      (node (ref "P9") (pin "29") (pinfunction "29_29") (pintype "passive"))
    )
    (net (code "121") (name "/SPI1_D1") (class "Default")
      (node (ref "IC1") (pin "D12") (pinfunction "SPI1_D1_D12") (pintype "bidirectional"))
      (node (ref "P9") (pin "30") (pinfunction "30_30") (pintype "passive"))
    )
    (net (code "122") (name "/SPI1_SCLK") (class "Default")
      (node (ref "IC1") (pin "A13") (pinfunction "SPI1_CLK_A13") (pintype "bidirectional"))
      (node (ref "IC9") (pin "23") (pinfunction "ACLK_23") (pintype "bidirectional"))
      (node (ref "P9") (pin "31") (pinfunction "31_31") (pintype "passive"))
    )
    (net (code "123") (name "/SYS_RESET#") (class "Default")
      (node (ref "C16") (pin "1") (pinfunction "1_1") (pintype "passive"))
      (node (ref "C21") (pin "1") (pinfunction "1_1") (pintype "passive"))
      (node (ref "IC1") (pin "A10") (pinfunction "SYS_RESETN_A10") (pintype "bidirectional"))
      (node (ref "IC2") (pin "4") (pinfunction "Y_4") (pintype "bidirectional"))
      (node (ref "P2") (pin "15") (pinfunction "SRST_15") (pintype "bidirectional"))
      (node (ref "P9") (pin "10") (pinfunction "10_10") (pintype "passive"))
      (node (ref "R32") (pin "2") (pinfunction "2_2") (pintype "passive"))
      (node (ref "RESET") (pin "3") (pinfunction "3_3") (pintype "bidirectional"))
      (node (ref "RESET") (pin "4") (pinfunction "4_4") (pintype "bidirectional"))
    )
    (net (code "124") (name "/TEST") (class "Default")
      (node (ref "IC9") (pin "49") (pinfunction "TEST_49") (pintype "bidirectional"))
      (node (ref "R114") (pin "2") (pinfunction "2_2") (pintype "passive"))
    )
    (net (code "125") (name "/TIMER4") (class "Default")
      (node (ref "IC1") (pin "R7") (pinfunction "TIMER4_R7") (pintype "bidirectional"))
      (node (ref "P8") (pin "7") (pinfunction "7_7") (pintype "passive"))
    )
    (net (code "126") (name "/TIMER5") (class "Default")
      (node (ref "IC1") (pin "T6") (pinfunction "TIMER5_T6") (pintype "bidirectional"))
      (node (ref "P8") (pin "9") (pinfunction "9_9") (pintype "passive"))
    )
    (net (code "127") (name "/TIMER6") (class "Default")
      (node (ref "IC1") (pin "U6") (pinfunction "TIMER6_U6") (pintype "bidirectional"))
      (node (ref "P8") (pin "10") (pinfunction "10_10") (pintype "passive"))
    )
    (net (code "128") (name "/TIMER7") (class "Default")
      (node (ref "IC1") (pin "T7") (pinfunction "TIMER7_T7") (pintype "bidirectional"))
      (node (ref "P8") (pin "8") (pinfunction "8_8") (pintype "passive"))
    )
    (net (code "129") (name "/TX->RX") (class "Default")
      (node (ref "IC17") (pin "2") (pinfunction "1A_2") (pintype "bidirectional"))
      (node (ref "R123") (pin "1") (pinfunction "1_1") (pintype "passive"))
      (node (ref "X1") (pin "4") (pinfunction "4_4") (pintype "passive"))
    )
    (net (code "130") (name "/TX0+") (class "Default")
      (node (ref "IC8") (pin "5") (pinfunction "TMDS.CH2+_5") (pintype "bidirectional"))
      (node (ref "IC9") (pin "40") (pinfunction "TX0+_40") (pintype "bidirectional"))
      (node (ref "X5") (pin "9") (pinfunction "TMDS.DATA0+_9") (pintype "bidirectional"))
    )
    (net (code "131") (name "/TX0-") (class "Default")
      (node (ref "IC8") (pin "4") (pinfunction "TMDS.CH2-_4") (pintype "bidirectional"))
      (node (ref "IC9") (pin "39") (pinfunction "TX0-_39") (pintype "bidirectional"))
      (node (ref "X5") (pin "11") (pinfunction "TMDS.DATA0-_11") (pintype "bidirectional"))
    )
    (net (code "132") (name "/TX1+") (class "Default")
      (node (ref "IC7") (pin "2") (pinfunction "TMDS.CH1+_2") (pintype "bidirectional"))
      (node (ref "IC9") (pin "43") (pinfunction "TX1+_43") (pintype "bidirectional"))
      (node (ref "X5") (pin "6") (pinfunction "TMDS.DATA1+_6") (pintype "bidirectional"))
    )
    (net (code "133") (name "/TX1-") (class "Default")
      (node (ref "IC7") (pin "1") (pinfunction "TMDS.CH1-_1") (pintype "bidirectional"))
      (node (ref "IC9") (pin "42") (pinfunction "TX1-_42") (pintype "bidirectional"))
      (node (ref "X5") (pin "8") (pinfunction "TMDS.DATA1-_8") (pintype "bidirectional"))
    )
    (net (code "134") (name "/TX2+") (class "Default")
      (node (ref "IC7") (pin "5") (pinfunction "TMDS.CH2+_5") (pintype "bidirectional"))
      (node (ref "IC9") (pin "45") (pinfunction "TX2+_45") (pintype "bidirectional"))
      (node (ref "X5") (pin "3") (pinfunction "TMDS.DATA2+_3") (pintype "bidirectional"))
    )
    (net (code "135") (name "/TX2-") (class "Default")
      (node (ref "IC7") (pin "4") (pinfunction "TMDS.CH2-_4") (pintype "bidirectional"))
      (node (ref "IC9") (pin "44") (pinfunction "TX2-_44") (pintype "bidirectional"))
      (node (ref "X5") (pin "5") (pinfunction "TMDS.DATA2-_5") (pintype "bidirectional"))
    )
    (net (code "136") (name "/TXC+") (class "Default")
      (node (ref "IC8") (pin "2") (pinfunction "TMDS.CH1+_2") (pintype "bidirectional"))
      (node (ref "IC9") (pin "38") (pinfunction "TXC+_38") (pintype "bidirectional"))
      (node (ref "X5") (pin "12") (pinfunction "TMDS.CLOCK+_12") (pintype "bidirectional"))
    )
    (net (code "137") (name "/TXC-") (class "Default")
      (node (ref "IC8") (pin "1") (pinfunction "TMDS.CH1-_1") (pintype "bidirectional"))
      (node (ref "IC9") (pin "37") (pinfunction "TXC-_37") (pintype "bidirectional"))
      (node (ref "X5") (pin "14") (pinfunction "TMDS.CLOCK-_14") (pintype "bidirectional"))
    )
    (net (code "138") (name "/UART0_RST#") (class "Default")
      (node (ref "IC1") (pin "E17") (pinfunction "UART0_RSTN_E17") (pintype "bidirectional"))
      (node (ref "TP6") (pin "TP") (pinfunction "TP_TP") (pintype "input"))
    )
    (net (code "139") (name "/UART0_RXD") (class "Default")
      (node (ref "IC1") (pin "E15") (pinfunction "UART0_RXD_E15") (pintype "bidirectional"))
      (node (ref "IC17") (pin "6") (pinfunction "1Y_6") (pintype "bidirectional"))
    )
    (net (code "140") (name "/UART0_TXD") (class "Default")
      (node (ref "IC1") (pin "E16") (pinfunction "UART0_TXD_E16") (pintype "bidirectional"))
      (node (ref "IC17") (pin "5") (pinfunction "2A_5") (pintype "bidirectional"))
    )
    (net (code "141") (name "/UART1_RXD") (class "Default")
      (node (ref "IC1") (pin "D16") (pinfunction "UART1_RXD_D16") (pintype "bidirectional"))
      (node (ref "P9") (pin "26") (pinfunction "26_26") (pintype "passive"))
    )
    (net (code "142") (name "/UART1_TXD") (class "Default")
      (node (ref "IC1") (pin "D15") (pinfunction "UART1_TXD_D15") (pintype "bidirectional"))
      (node (ref "P9") (pin "24") (pinfunction "24_24") (pintype "passive"))
    )
    (net (code "143") (name "/UART2_RXD") (class "Default")
      (node (ref "IC1") (pin "A17") (pinfunction "UART2_RXD_A17") (pintype "bidirectional"))
      (node (ref "P9") (pin "22") (pinfunction "22_22") (pintype "passive"))
    )
    (net (code "144") (name "/UART2_TXD") (class "Default")
      (node (ref "IC1") (pin "B17") (pinfunction "UART2_TXD_B17") (pintype "bidirectional"))
      (node (ref "P9") (pin "21") (pinfunction "21_21") (pintype "passive"))
    )
    (net (code "145") (name "/UART4_RXD") (class "Default")
      (node (ref "IC1") (pin "T17") (pinfunction "UART4_RXD_T17") (pintype "bidirectional"))
      (node (ref "P9") (pin "11") (pinfunction "11_11") (pintype "passive"))
    )
    (net (code "146") (name "/UART4_TXD") (class "Default")
      (node (ref "IC1") (pin "U17") (pinfunction "UART4_TXD_U17") (pintype "bidirectional"))
      (node (ref "P9") (pin "13") (pinfunction "13_13") (pintype "passive"))
    )
    (net (code "147") (name "/USB.CLIENT.D+") (class "Default")
      (node (ref "IC1") (pin "N17") (pinfunction "USB0_DP_N17") (pintype "bidirectional"))
      (node (ref "IC14") (pin "1") (pinfunction "D+_1") (pintype "bidirectional"))
      (node (ref "X4") (pin "D+") (pinfunction "D+_D+") (pintype "input"))
    )
    (net (code "148") (name "/USB.CLIENT.D-") (class "Default")
      (node (ref "IC1") (pin "N18") (pinfunction "USB0_DM_N18") (pintype "bidirectional"))
      (node (ref "IC14") (pin "2") (pinfunction "D-_2") (pintype "bidirectional"))
      (node (ref "X4") (pin "D-") (pinfunction "D-_D-") (pintype "input"))
    )
    (net (code "149") (name "/USB.CLIENT.ID") (class "Default")
      (node (ref "IC1") (pin "P16") (pinfunction "USB0_ID_P16") (pintype "bidirectional"))
      (node (ref "IC14") (pin "3") (pinfunction "ID_3") (pintype "bidirectional"))
      (node (ref "X4") (pin "ID") (pinfunction "ID_ID") (pintype "input"))
    )
    (net (code "150") (name "/USB.HOST.D+") (class "Default")
      (node (ref "IC1") (pin "R17") (pinfunction "USB1_DP_R17") (pintype "bidirectional"))
      (node (ref "IC15") (pin "1") (pinfunction "D+_1") (pintype "bidirectional"))
      (node (ref "X3") (pin "3") (pinfunction "D+_3") (pintype "bidirectional"))
    )
    (net (code "151") (name "/USB.HOST.D-") (class "Default")
      (node (ref "IC1") (pin "R18") (pinfunction "USB1_DM_R18") (pintype "bidirectional"))
      (node (ref "IC15") (pin "2") (pinfunction "D-_2") (pintype "bidirectional"))
      (node (ref "X3") (pin "2") (pinfunction "D-_2") (pintype "bidirectional"))
    )
    (net (code "152") (name "/USB1_DRVVBUS") (class "Default")
      (node (ref "IC1") (pin "F15") (pinfunction "USB1_DRVVBUS_F15") (pintype "bidirectional"))
      (node (ref "IC12") (pin "4") (pinfunction "EN#_4") (pintype "bidirectional"))
      (node (ref "R19") (pin "1") (pinfunction "1_1") (pintype "passive"))
    )
    (net (code "153") (name "/USB1_OC#") (class "Default")
      (node (ref "IC1") (pin "T16") (pinfunction "(USB1_OCN)GPIO1_26_T16") (pintype "bidirectional"))
      (node (ref "IC12") (pin "5") (pinfunction "OC#_5") (pintype "bidirectional"))
      (node (ref "R122") (pin "2") (pinfunction "2_2") (pintype "passive"))
    )
    (net (code "154") (name "/USB1_VBUS") (class "Default")
      (node (ref "FB4") (pin "2") (pinfunction "P$2_2") (pintype "bidirectional"))
      (node (ref "IC1") (pin "T18") (pinfunction "USB1_VBUS_T18") (pintype "bidirectional"))
    )
    (net (code "155") (name "/USR0") (class "Default")
      (node (ref "IC1") (pin "V15") (pinfunction "USR0_V15") (pintype "bidirectional"))
      (node (ref "R104") (pin "2") (pinfunction "2_2") (pintype "passive"))
    )
    (net (code "156") (name "/USR1") (class "Default")
      (node (ref "IC1") (pin "U15") (pinfunction "USR1_U15") (pintype "bidirectional"))
      (node (ref "R100") (pin "2") (pinfunction "2_2") (pintype "passive"))
    )
    (net (code "157") (name "/USR2") (class "Default")
      (node (ref "IC1") (pin "T15") (pinfunction "USR2_T15") (pintype "bidirectional"))
      (node (ref "R96") (pin "2") (pinfunction "2_2") (pintype "passive"))
    )
    (net (code "158") (name "/USR3") (class "Default")
      (node (ref "IC1") (pin "V16") (pinfunction "USR3_V16") (pintype "bidirectional"))
      (node (ref "R92") (pin "2") (pinfunction "2_2") (pintype "passive"))
    )
    (net (code "159") (name "/VIN_BAT") (class "Default")
      (node (ref "IC1") (pin "Y2") (pinfunction "BAT_1_Y2") (pintype "bidirectional"))
      (node (ref "IC1") (pin "Y3") (pinfunction "BAT_2_Y3") (pintype "bidirectional"))
      (node (ref "TP2") (pin "P$1") (pinfunction "TP_P$1") (pintype "bidirectional"))
    )
    (net (code "160") (name "/WL_EN") (class "Default")
      (node (ref "IC11") (pin "3") (pinfunction "A2_3") (pintype "bidirectional"))
      (node (ref "R10") (pin "1") (pinfunction "1_1") (pintype "passive"))
      (node (ref "T3") (pin "G") (pinfunction "G_G") (pintype "bidirectional"))
    )
    (net (code "161") (name "/WL_EN.SIP") (class "Default")
      (node (ref "IC1") (pin "K18") (pinfunction "MII1_TXCLK_K18") (pintype "bidirectional"))
      (node (ref "R136") (pin "1") (pinfunction "1_1") (pintype "passive"))
    )
    (net (code "162") (name "/WL_IRQ") (class "Default")
      (node (ref "IC11") (pin "9") (pinfunction "A8_9") (pintype "bidirectional"))
      (node (ref "R60") (pin "2") (pinfunction "2_2") (pintype "passive"))
    )
    (net (code "163") (name "/WL_IRQ.SIP") (class "Default")
      (node (ref "IC1") (pin "H18") (pinfunction "MII1_REFCLK_H18") (pintype "bidirectional"))
      (node (ref "R134") (pin "1") (pinfunction "1_1") (pintype "passive"))
    )
    (net (code "164") (name "/WL_SDIO_CLK") (class "Default")
      (node (ref "IC10") (pin "6") (pinfunction "A5_6") (pintype "bidirectional"))
      (node (ref "R103") (pin "2") (pinfunction "2_2") (pintype "passive"))
      (node (ref "R64") (pin "2") (pinfunction "2_2") (pintype "passive"))
    )
    (net (code "165") (name "/WL_SDIO_CLK.SIP") (class "Default")
      (node (ref "IC1") (pin "L15") (pinfunction "MII1_RXD1_L15") (pintype "bidirectional"))
      (node (ref "R126") (pin "1") (pinfunction "1_1") (pintype "passive"))
    )
    (net (code "166") (name "/WL_SDIO_CMD") (class "Default")
      (node (ref "IC10") (pin "7") (pinfunction "A6_7") (pintype "bidirectional"))
      (node (ref "R105") (pin "2") (pinfunction "2_2") (pintype "passive"))
      (node (ref "R62") (pin "2") (pinfunction "2_2") (pintype "passive"))
    )
    (net (code "167") (name "/WL_SDIO_CMD.SIP") (class "Default")
      (node (ref "IC1") (pin "J16") (pinfunction "MII1_TXEN_J16") (pintype "bidirectional"))
      (node (ref "R86") (pin "1") (pinfunction "1_1") (pintype "passive"))
    )
    (net (code "168") (name "/WL_SDIO_D0") (class "Default")
      (node (ref "IC10") (pin "1") (pinfunction "A1_1") (pintype "bidirectional"))
      (node (ref "R66") (pin "2") (pinfunction "2_2") (pintype "passive"))
      (node (ref "R98") (pin "2") (pinfunction "2_2") (pintype "passive"))
    )
    (net (code "169") (name "/WL_SDIO_D0.SIP") (class "Default")
      (node (ref "IC1") (pin "J17") (pinfunction "MII1_RXDV_J17") (pintype "bidirectional"))
      (node (ref "R130") (pin "1") (pinfunction "1_1") (pintype "passive"))
    )
    (net (code "170") (name "/WL_SDIO_D1") (class "Default")
      (node (ref "IC10") (pin "3") (pinfunction "A2_3") (pintype "bidirectional"))
      (node (ref "R68") (pin "2") (pinfunction "2_2") (pintype "passive"))
      (node (ref "R99") (pin "2") (pinfunction "2_2") (pintype "passive"))
    )
    (net (code "171") (name "/WL_SDIO_D1.SIP") (class "Default")
      (node (ref "IC1") (pin "J18") (pinfunction "MII1_TXD3_J18") (pintype "bidirectional"))
      (node (ref "R129") (pin "1") (pinfunction "1_1") (pintype "passive"))
    )
    (net (code "172") (name "/WL_SDIO_D2") (class "Default")
      (node (ref "IC10") (pin "4") (pinfunction "A3_4") (pintype "bidirectional"))
      (node (ref "R101") (pin "2") (pinfunction "2_2") (pintype "passive"))
      (node (ref "R70") (pin "2") (pinfunction "2_2") (pintype "passive"))
    )
    (net (code "173") (name "/WL_SDIO_D2.SIP") (class "Default")
      (node (ref "IC1") (pin "K15") (pinfunction "MII1_TXD2_K15") (pintype "bidirectional"))
      (node (ref "R128") (pin "1") (pinfunction "1_1") (pintype "passive"))
    )
    (net (code "174") (name "/WL_SDIO_D3") (class "Default")
      (node (ref "IC10") (pin "5") (pinfunction "A4_5") (pintype "bidirectional"))
      (node (ref "R102") (pin "2") (pinfunction "2_2") (pintype "passive"))
      (node (ref "R72") (pin "2") (pinfunction "2_2") (pintype "passive"))
    )
    (net (code "175") (name "/WL_SDIO_D3.SIP") (class "Default")
      (node (ref "IC1") (pin "H16") (pinfunction "MII1_COL_H16") (pintype "bidirectional"))
      (node (ref "R127") (pin "1") (pinfunction "1_1") (pintype "passive"))
    )
    (net (code "176") (name "/XDMA_EVENT_INTRO") (class "Default")
      (node (ref "FB5") (pin "2") (pinfunction "2_2") (pintype "passive"))
      (node (ref "IC13") (pin "1") (pinfunction "CLK_1") (pintype "bidirectional"))
      (node (ref "P2") (pin "17") (pinfunction "EMU2_17") (pintype "bidirectional"))
    )
    (net (code "177") (name "1.8V-WIFI") (class "Default")
      (node (ref "C11") (pin "+") (pinfunction "+_+") (pintype "passive"))
      (node (ref "C24") (pin "1") (pinfunction "1_1") (pintype "passive"))
      (node (ref "C25") (pin "1") (pinfunction "1_1") (pintype "passive"))
      (node (ref "C43") (pin "1") (pinfunction "1_1") (pintype "passive"))
      (node (ref "C64") (pin "1") (pinfunction "1_1") (pintype "passive"))
      (node (ref "C8") (pin "1") (pinfunction "1_1") (pintype "passive"))
      (node (ref "IC10") (pin "2") (pinfunction "VCCA_2") (pintype "bidirectional"))
      (node (ref "IC11") (pin "2") (pinfunction "VCCA_2") (pintype "bidirectional"))
      (node (ref "IC19") (pin "5") (pinfunction "VOUT_5") (pintype "bidirectional"))
      (node (ref "OSC2") (pin "4") (pinfunction "VCC_4") (pintype "bidirectional"))
      (node (ref "R101") (pin "1") (pinfunction "1_1") (pintype "passive"))
      (node (ref "R102") (pin "1") (pinfunction "1_1") (pintype "passive"))
      (node (ref "R103") (pin "1") (pinfunction "1_1") (pintype "passive"))
      (node (ref "R105") (pin "1") (pinfunction "1_1") (pintype "passive"))
      (node (ref "R111") (pin "1") (pinfunction "1_1") (pintype "passive"))
      (node (ref "R90") (pin "1") (pinfunction "1_1") (pintype "passive"))
      (node (ref "R98") (pin "1") (pinfunction "1_1") (pintype "passive"))
      (node (ref "R99") (pin "1") (pinfunction "1_1") (pintype "passive"))
    )
    (net (code "178") (name "3.3V-WIFI") (class "Default")
      (node (ref "C10") (pin "1") (pinfunction "1_1") (pintype "passive"))
      (node (ref "C20") (pin "1") (pinfunction "1_1") (pintype "passive"))
      (node (ref "C23") (pin "+") (pinfunction "+_+") (pintype "passive"))
      (node (ref "C44") (pin "1") (pinfunction "1_1") (pintype "passive"))
      (node (ref "C45") (pin "1") (pinfunction "1_1") (pintype "passive"))
      (node (ref "C61") (pin "1") (pinfunction "1_1") (pintype "passive"))
      (node (ref "C63") (pin "1") (pinfunction "1_1") (pintype "passive"))
      (node (ref "IC10") (pin "19") (pinfunction "VCCB_19") (pintype "bidirectional"))
      (node (ref "IC11") (pin "19") (pinfunction "VCCB_19") (pintype "bidirectional"))
      (node (ref "IC18") (pin "4") (pinfunction "OUT_4") (pintype "bidirectional"))
      (node (ref "IC19") (pin "1") (pinfunction "VIN_1") (pintype "bidirectional"))
      (node (ref "IC19") (pin "3") (pinfunction "EN_3") (pintype "bidirectional"))
      (node (ref "R124") (pin "2") (pinfunction "2_2") (pintype "passive"))
      (node (ref "R125") (pin "2") (pinfunction "2_2") (pintype "passive"))
      (node (ref "R93") (pin "1") (pinfunction "1_1") (pintype "passive"))
    )
    (net (code "179") (name "AGND") (class "Default")
      (node (ref "IC1") (pin "A6") (pinfunction "AGND_1_A6") (pintype "bidirectional"))
      (node (ref "IC1") (pin "A9") (pinfunction "AGND_0_A9") (pintype "bidirectional"))
      (node (ref "IC1") (pin "E8") (pinfunction "AGND_E8") (pintype "bidirectional"))
      (node (ref "P9") (pin "34") (pinfunction "34_34") (pintype "passive"))
    )
    (net (code "180") (name "CGND") (class "Default")
      (node (ref "MGT1") (pin "P$1") (pinfunction "P$1_P$1") (pintype "bidirectional"))
      (node (ref "MGT2") (pin "P$1") (pinfunction "P$1_P$1") (pintype "bidirectional"))
      (node (ref "MGT3") (pin "P$1") (pinfunction "P$1_P$1") (pintype "bidirectional"))
      (node (ref "MGT4") (pin "P$1") (pinfunction "P$1_P$1") (pintype "bidirectional"))
      (node (ref "R17") (pin "2") (pinfunction "2_2") (pintype "passive"))
      (node (ref "X2") (pin "CGND1") (pinfunction "CGND1_CGND1") (pintype "bidirectional"))
      (node (ref "X2") (pin "CGND2") (pinfunction "CGND2_CGND2") (pintype "bidirectional"))
      (node (ref "X2") (pin "CGND3") (pinfunction "CGND3_CGND3") (pintype "bidirectional"))
      (node (ref "X2") (pin "CGND4") (pinfunction "CGND4_CGND4") (pintype "bidirectional"))
      (node (ref "X2") (pin "CGND5") (pinfunction "CGND5_CGND5") (pintype "bidirectional"))
      (node (ref "X2") (pin "CGND6") (pinfunction "CGND6_CGND6") (pintype "bidirectional"))
      (node (ref "X3") (pin "5") (pinfunction "CG1_5") (pintype "bidirectional"))
      (node (ref "X3") (pin "6") (pinfunction "CG2_6") (pintype "bidirectional"))
      (node (ref "X4") (pin "CGND1") (pinfunction "SGND1_CGND1") (pintype "bidirectional"))
      (node (ref "X4") (pin "CGND2") (pinfunction "SGND2_CGND2") (pintype "bidirectional"))
      (node (ref "X4") (pin "CGND3") (pinfunction "SGND3_CGND3") (pintype "bidirectional"))
      (node (ref "X4") (pin "CGND4") (pinfunction "SGND4_CGND4") (pintype "bidirectional"))
      (node (ref "X4") (pin "CGND5") (pinfunction "SGND5_CGND5") (pintype "bidirectional"))
      (node (ref "X4") (pin "CGND6") (pinfunction "SGND6_CGND6") (pintype "bidirectional"))
      (node (ref "X5") (pin "CG1") (pinfunction "CG1_CG1") (pintype "bidirectional"))
      (node (ref "X5") (pin "CG2") (pinfunction "CG2_CG2") (pintype "bidirectional"))
      (node (ref "X5") (pin "CG3") (pinfunction "CG3_CG3") (pintype "bidirectional"))
      (node (ref "X5") (pin "CG4") (pinfunction "CG4_CG4") (pintype "bidirectional"))
    )
    (net (code "181") (name "GND") (class "Default")
      (node (ref "ANT1") (pin "GND1") (pinfunction "GND1_GND1") (pintype "bidirectional"))
      (node (ref "ANT1") (pin "GND2") (pinfunction "GND2_GND2") (pintype "bidirectional"))
      (node (ref "ANT2") (pin "GND1") (pinfunction "GND1_GND1") (pintype "bidirectional"))
      (node (ref "ANT2") (pin "GND2") (pinfunction "GND2_GND2") (pintype "bidirectional"))
      (node (ref "C1") (pin "2") (pinfunction "2_2") (pintype "passive"))
      (node (ref "C10") (pin "2") (pinfunction "2_2") (pintype "passive"))
      (node (ref "C11") (pin "-") (pinfunction "-_-") (pintype "passive"))
      (node (ref "C12") (pin "2") (pinfunction "2_2") (pintype "passive"))
      (node (ref "C13") (pin "2") (pinfunction "2_2") (pintype "passive"))
      (node (ref "C14") (pin "2") (pinfunction "2_2") (pintype "passive"))
      (node (ref "C15") (pin "2") (pinfunction "2_2") (pintype "passive"))
      (node (ref "C16") (pin "2") (pinfunction "2_2") (pintype "passive"))
      (node (ref "C17") (pin "2") (pinfunction "2_2") (pintype "passive"))
      (node (ref "C18") (pin "2") (pinfunction "2_2") (pintype "passive"))
      (node (ref "C19") (pin "2") (pinfunction "2_2") (pintype "passive"))
      (node (ref "C2") (pin "2") (pinfunction "2_2") (pintype "passive"))
      (node (ref "C20") (pin "2") (pinfunction "2_2") (pintype "passive"))
      (node (ref "C21") (pin "2") (pinfunction "2_2") (pintype "passive"))
      (node (ref "C22") (pin "2") (pinfunction "2_2") (pintype "passive"))
      (node (ref "C23") (pin "-") (pinfunction "-_-") (pintype "passive"))
      (node (ref "C24") (pin "2") (pinfunction "2_2") (pintype "passive"))
      (node (ref "C25") (pin "2") (pinfunction "2_2") (pintype "passive"))
      (node (ref "C27") (pin "2") (pinfunction "2_2") (pintype "passive"))
      (node (ref "C28") (pin "2") (pinfunction "2_2") (pintype "passive"))
      (node (ref "C29") (pin "2") (pinfunction "2_2") (pintype "passive"))
      (node (ref "C30") (pin "2") (pinfunction "2_2") (pintype "passive"))
      (node (ref "C31") (pin "2") (pinfunction "2_2") (pintype "passive"))
      (node (ref "C32") (pin "2") (pinfunction "2_2") (pintype "passive"))
      (node (ref "C33") (pin "2") (pinfunction "2_2") (pintype "passive"))
      (node (ref "C34") (pin "2") (pinfunction "2_2") (pintype "passive"))
      (node (ref "C35") (pin "2") (pinfunction "2_2") (pintype "passive"))
      (node (ref "C36") (pin "2") (pinfunction "2_2") (pintype "passive"))
      (node (ref "C37") (pin "2") (pinfunction "2_2") (pintype "passive"))
      (node (ref "C38") (pin "2") (pinfunction "2_2") (pintype "passive"))
      (node (ref "C39") (pin "2") (pinfunction "2_2") (pintype "passive"))
      (node (ref "C40") (pin "2") (pinfunction "2_2") (pintype "passive"))
      (node (ref "C41") (pin "2") (pinfunction "2_2") (pintype "passive"))
      (node (ref "C42") (pin "2") (pinfunction "2_2") (pintype "passive"))
      (node (ref "C43") (pin "2") (pinfunction "2_2") (pintype "passive"))
      (node (ref "C44") (pin "2") (pinfunction "2_2") (pintype "passive"))
      (node (ref "C45") (pin "2") (pinfunction "2_2") (pintype "passive"))
      (node (ref "C47") (pin "2") (pinfunction "2_2") (pintype "passive"))
      (node (ref "C48") (pin "2") (pinfunction "2_2") (pintype "passive"))
      (node (ref "C49") (pin "2") (pinfunction "2_2") (pintype "passive"))
      (node (ref "C50") (pin "2") (pinfunction "2_2") (pintype "passive"))
      (node (ref "C51") (pin "2") (pinfunction "2_2") (pintype "passive"))
      (node (ref "C52") (pin "2") (pinfunction "2_2") (pintype "passive"))
      (node (ref "C53") (pin "2") (pinfunction "2_2") (pintype "passive"))
      (node (ref "C54") (pin "2") (pinfunction "2_2") (pintype "passive"))
      (node (ref "C55") (pin "2") (pinfunction "2_2") (pintype "passive"))
      (node (ref "C56") (pin "2") (pinfunction "2_2") (pintype "passive"))
      (node (ref "C57") (pin "2") (pinfunction "2_2") (pintype "passive"))
      (node (ref "C58") (pin "2") (pinfunction "2_2") (pintype "passive"))
      (node (ref "C59") (pin "2") (pinfunction "2_2") (pintype "passive"))
      (node (ref "C61") (pin "2") (pinfunction "2_2") (pintype "passive"))
      (node (ref "C62") (pin "-") (pinfunction "-_-") (pintype "passive"))
      (node (ref "C63") (pin "2") (pinfunction "2_2") (pintype "passive"))
      (node (ref "C64") (pin "2") (pinfunction "2_2") (pintype "passive"))
      (node (ref "C69") (pin "2") (pinfunction "2_2") (pintype "passive"))
      (node (ref "C7") (pin "2") (pinfunction "2_2") (pintype "passive"))
      (node (ref "C8") (pin "2") (pinfunction "2_2") (pintype "passive"))
      (node (ref "C9") (pin "2") (pinfunction "2_2") (pintype "passive"))
      (node (ref "D8") (pin "2") (pinfunction "A2_2") (pintype "passive"))
      (node (ref "IC1") (pin "A1") (pinfunction "DGND1_A1") (pintype "bidirectional"))
      (node (ref "IC1") (pin "A18") (pinfunction "DGND2_A18") (pintype "bidirectional"))
      (node (ref "IC1") (pin "E19") (pinfunction "DGND3_E19") (pintype "bidirectional"))
      (node (ref "IC1") (pin "E20") (pinfunction "DGND4_E20") (pintype "bidirectional"))
      (node (ref "IC1") (pin "F19") (pinfunction "DGND6_F19") (pintype "bidirectional"))
      (node (ref "IC1") (pin "F8") (pinfunction "DGND5_F8") (pintype "bidirectional"))
      (node (ref "IC1") (pin "G11") (pinfunction "DGND9_G11") (pintype "bidirectional"))
      (node (ref "IC1") (pin "G12") (pinfunction "DGND10_G12") (pintype "bidirectional"))
      (node (ref "IC1") (pin "G19") (pinfunction "DGND11_G19") (pintype "bidirectional"))
      (node (ref "IC1") (pin "G8") (pinfunction "DGND7_G8") (pintype "bidirectional"))
      (node (ref "IC1") (pin "G9") (pinfunction "DGND8_G9") (pintype "bidirectional"))
      (node (ref "IC1") (pin "H10") (pinfunction "DGND16_H10") (pintype "bidirectional"))
      (node (ref "IC1") (pin "H12") (pinfunction "DGND17_H12") (pintype "bidirectional"))
      (node (ref "IC1") (pin "H19") (pinfunction "DGND18_H19") (pintype "bidirectional"))
      (node (ref "IC1") (pin "H6") (pinfunction "DGND12_H6") (pintype "bidirectional"))
      (node (ref "IC1") (pin "H7") (pinfunction "DGND13_H7") (pintype "bidirectional"))
      (node (ref "IC1") (pin "H8") (pinfunction "DGND14_H8") (pintype "bidirectional"))
      (node (ref "IC1") (pin "H9") (pinfunction "DGND15_H9") (pintype "bidirectional"))
      (node (ref "IC1") (pin "J10") (pinfunction "DGND23_J10") (pintype "bidirectional"))
      (node (ref "IC1") (pin "J11") (pinfunction "DGND24_J11") (pintype "bidirectional"))
      (node (ref "IC1") (pin "J19") (pinfunction "DGND25_J19") (pintype "bidirectional"))
      (node (ref "IC1") (pin "J20") (pinfunction "DGND26_J20") (pintype "bidirectional"))
      (node (ref "IC1") (pin "J6") (pinfunction "DGND19_J6") (pintype "bidirectional"))
      (node (ref "IC1") (pin "J7") (pinfunction "DGND20_J7") (pintype "bidirectional"))
      (node (ref "IC1") (pin "J8") (pinfunction "DGND21_J8") (pintype "bidirectional"))
      (node (ref "IC1") (pin "J9") (pinfunction "DGND22_J9") (pintype "bidirectional"))
      (node (ref "IC1") (pin "K10") (pinfunction "DGND29_K10") (pintype "bidirectional"))
      (node (ref "IC1") (pin "K11") (pinfunction "DGND30_K11") (pintype "bidirectional"))
      (node (ref "IC1") (pin "K19") (pinfunction "DGND31_K19") (pintype "bidirectional"))
      (node (ref "IC1") (pin "K7") (pinfunction "DGND27_K7") (pintype "bidirectional"))
      (node (ref "IC1") (pin "K9") (pinfunction "DGND28_K9") (pintype "bidirectional"))
      (node (ref "IC1") (pin "L10") (pinfunction "DGND32_L10") (pintype "bidirectional"))
      (node (ref "IC1") (pin "L11") (pinfunction "DGND33_L11") (pintype "bidirectional"))
      (node (ref "IC1") (pin "L12") (pinfunction "DGND34_L12") (pintype "bidirectional"))
      (node (ref "IC1") (pin "L13") (pinfunction "DGND35_L13") (pintype "bidirectional"))
      (node (ref "IC1") (pin "L19") (pinfunction "DGND36_L19") (pintype "bidirectional"))
      (node (ref "IC1") (pin "M10") (pinfunction "DGND42_M10") (pintype "bidirectional"))
      (node (ref "IC1") (pin "M12") (pinfunction "DGND43_M12") (pintype "bidirectional"))
      (node (ref "IC1") (pin "M14") (pinfunction "DGND44_M14") (pintype "bidirectional"))
      (node (ref "IC1") (pin "M19") (pinfunction "DGND45_M19") (pintype "bidirectional"))
      (node (ref "IC1") (pin "M6") (pinfunction "DGND38_M6") (pintype "bidirectional"))
      (node (ref "IC1") (pin "M7") (pinfunction "DGND39_M7") (pintype "bidirectional"))
      (node (ref "IC1") (pin "M8") (pinfunction "DGND40_M8") (pintype "bidirectional"))
      (node (ref "IC1") (pin "M9") (pinfunction "DGND41_M9") (pintype "bidirectional"))
      (node (ref "IC1") (pin "N10") (pinfunction "DGND47_N10") (pintype "bidirectional"))
      (node (ref "IC1") (pin "N11") (pinfunction "DGND48_N11") (pintype "bidirectional"))
      (node (ref "IC1") (pin "N14") (pinfunction "DGND49_N14") (pintype "bidirectional"))
      (node (ref "IC1") (pin "N19") (pinfunction "DGND50_N19") (pintype "bidirectional"))
      (node (ref "IC1") (pin "N20") (pinfunction "DGND51_N20") (pintype "bidirectional"))
      (node (ref "IC1") (pin "N7") (pinfunction "DGND46_N7") (pintype "bidirectional"))
      (node (ref "IC1") (pin "P19") (pinfunction "DGND52_P19") (pintype "bidirectional"))
      (node (ref "IC1") (pin "P20") (pinfunction "DGND53_P20") (pintype "bidirectional"))
      (node (ref "IC1") (pin "R19") (pinfunction "DGND54_R19") (pintype "bidirectional"))
      (node (ref "IC1") (pin "R20") (pinfunction "DGND55_R20") (pintype "bidirectional"))
      (node (ref "IC1") (pin "T19") (pinfunction "DGND56_T19") (pintype "bidirectional"))
      (node (ref "IC1") (pin "T20") (pinfunction "DGND57_T20") (pintype "bidirectional"))
      (node (ref "IC1") (pin "U19") (pinfunction "DGND58_U19") (pintype "bidirectional"))
      (node (ref "IC1") (pin "V1") (pinfunction "DGND59_V1") (pintype "bidirectional"))
      (node (ref "IC1") (pin "V18") (pinfunction "DGND60_V18") (pintype "bidirectional"))
      (node (ref "IC1") (pin "V19") (pinfunction "DGND61_V19") (pintype "bidirectional"))
      (node (ref "IC1") (pin "W10") (pinfunction "DGND70_W10") (pintype "bidirectional"))
      (node (ref "IC1") (pin "W11") (pinfunction "DGND71_W11") (pintype "bidirectional"))
      (node (ref "IC1") (pin "W12") (pinfunction "DGND72_W12") (pintype "bidirectional"))
      (node (ref "IC1") (pin "W13") (pinfunction "DGND73_W13") (pintype "bidirectional"))
      (node (ref "IC1") (pin "W14") (pinfunction "DGND74_W14") (pintype "bidirectional"))
      (node (ref "IC1") (pin "W15") (pinfunction "DGND75_W15") (pintype "bidirectional"))
      (node (ref "IC1") (pin "W16") (pinfunction "DGND76_W16") (pintype "bidirectional"))
      (node (ref "IC1") (pin "W17") (pinfunction "DGND77_W17") (pintype "bidirectional"))
      (node (ref "IC1") (pin "W18") (pinfunction "DGND78_W18") (pintype "bidirectional"))
      (node (ref "IC1") (pin "W19") (pinfunction "DGND79_W19") (pintype "bidirectional"))
      (node (ref "IC1") (pin "W2") (pinfunction "DGND62_W2") (pintype "bidirectional"))
      (node (ref "IC1") (pin "W20") (pinfunction "DGND80_W20") (pintype "bidirectional"))
      (node (ref "IC1") (pin "W3") (pinfunction "DGND63_W3") (pintype "bidirectional"))
      (node (ref "IC1") (pin "W5") (pinfunction "DGND65_W5") (pintype "bidirectional"))
      (node (ref "IC1") (pin "W6") (pinfunction "DGND66_W6") (pintype "bidirectional"))
      (node (ref "IC1") (pin "W7") (pinfunction "DGND67_W7") (pintype "bidirectional"))
      (node (ref "IC1") (pin "W8") (pinfunction "DGND68_W8") (pintype "bidirectional"))
      (node (ref "IC1") (pin "W9") (pinfunction "DGND69_W9") (pintype "bidirectional"))
      (node (ref "IC1") (pin "Y10") (pinfunction "DGND83_Y10") (pintype "bidirectional"))
      (node (ref "IC1") (pin "Y12") (pinfunction "DGND84_Y12") (pintype "bidirectional"))
      (node (ref "IC1") (pin "Y15") (pinfunction "DGND85_Y15") (pintype "bidirectional"))
      (node (ref "IC1") (pin "Y18") (pinfunction "DGND86_Y18") (pintype "bidirectional"))
      (node (ref "IC1") (pin "Y7") (pinfunction "DGND82_Y7") (pintype "bidirectional"))
      (node (ref "IC10") (pin "11") (pinfunction "GND_11") (pintype "bidirectional"))
      (node (ref "IC10") (pin "TP") (pinfunction "TP_TP") (pintype "bidirectional"))
      (node (ref "IC11") (pin "11") (pinfunction "GND_11") (pintype "bidirectional"))
      (node (ref "IC11") (pin "TP") (pinfunction "TP_TP") (pintype "bidirectional"))
      (node (ref "IC12") (pin "1") (pinfunction "GND_1") (pintype "bidirectional"))
      (node (ref "IC12") (pin "9") (pinfunction "THERMAL_9") (pintype "bidirectional"))
      (node (ref "IC13") (pin "4") (pinfunction "GND_4") (pintype "bidirectional"))
      (node (ref "IC14") (pin "4") (pinfunction "GND_4") (pintype "bidirectional"))
      (node (ref "IC15") (pin "4") (pinfunction "GND_4") (pintype "bidirectional"))
      (node (ref "IC17") (pin "1") (pinfunction "1OE#_1") (pintype "bidirectional"))
      (node (ref "IC17") (pin "4") (pinfunction "GND_4") (pintype "bidirectional"))
      (node (ref "IC18") (pin "3") (pinfunction "GND1_3") (pintype "bidirectional"))
      (node (ref "IC18") (pin "6") (pinfunction "GND2_6") (pintype "bidirectional"))
      (node (ref "IC19") (pin "2") (pinfunction "GND_2") (pintype "bidirectional"))
      (node (ref "IC2") (pin "3") (pinfunction "GND_3") (pintype "bidirectional"))
      (node (ref "IC22") (pin "C4") (pinfunction "VSSQ1_C4") (pintype "bidirectional"))
      (node (ref "IC22") (pin "E7") (pinfunction "VSS1_E7") (pintype "bidirectional"))
      (node (ref "IC22") (pin "G5") (pinfunction "VSS2_G5") (pintype "bidirectional"))
      (node (ref "IC22") (pin "H10") (pinfunction "VSS3_H10") (pintype "bidirectional"))
      (node (ref "IC22") (pin "K8") (pinfunction "VSS4_K8") (pintype "bidirectional"))
      (node (ref "IC22") (pin "N2") (pinfunction "VSSQ2_N2") (pintype "bidirectional"))
      (node (ref "IC22") (pin "N5") (pinfunction "VSSQ3_N5") (pintype "bidirectional"))
      (node (ref "IC22") (pin "P4") (pinfunction "VSSQ4_P4") (pintype "bidirectional"))
      (node (ref "IC22") (pin "P6") (pinfunction "VSSQ5_P6") (pintype "bidirectional"))
      (node (ref "IC3") (pin "3") (pinfunction "GND_3") (pintype "bidirectional"))
      (node (ref "IC4") (pin "2") (pinfunction "VSS_2") (pintype "bidirectional"))
      (node (ref "IC7") (pin "3") (pinfunction "GND1_3") (pintype "bidirectional"))
      (node (ref "IC7") (pin "8") (pinfunction "GND2_8") (pintype "bidirectional"))
      (node (ref "IC8") (pin "3") (pinfunction "GND1_3") (pintype "bidirectional"))
      (node (ref "IC8") (pin "8") (pinfunction "GND2_8") (pintype "bidirectional"))
      (node (ref "IC9") (pin "16") (pinfunction "VPC[2]_16") (pintype "bidirectional"))
      (node (ref "IC9") (pin "17") (pinfunction "VPC[1]_17") (pintype "bidirectional"))
      (node (ref "IC9") (pin "18") (pinfunction "VPC[0]_18") (pintype "bidirectional"))
      (node (ref "IC9") (pin "19") (pinfunction "VPP_19") (pintype "bidirectional"))
      (node (ref "IC9") (pin "53") (pinfunction "A0_I2C_53") (pintype "bidirectional"))
      (node (ref "IC9") (pin "54") (pinfunction "A1_I2C_54") (pintype "bidirectional"))
      (node (ref "IC9") (pin "61") (pinfunction "VPA[2]_61") (pintype "bidirectional"))
      (node (ref "IC9") (pin "62") (pinfunction "VPA[1]_62") (pintype "bidirectional"))
      (node (ref "IC9") (pin "63") (pinfunction "VPA[0]_63") (pintype "bidirectional"))
      (node (ref "IC9") (pin "65") (pinfunction "GND.PAD_65") (pintype "bidirectional"))
      (node (ref "IC9") (pin "8") (pinfunction "VPB[1]_8") (pintype "bidirectional"))
      (node (ref "IC9") (pin "9") (pinfunction "VPB[0]_9") (pintype "bidirectional"))
      (node (ref "OSC1") (pin "2") (pinfunction "GND_2") (pintype "bidirectional"))
      (node (ref "OSC2") (pin "2") (pinfunction "GND_2") (pintype "bidirectional"))
      (node (ref "P2") (pin "10") (pinfunction "GND2_10") (pintype "bidirectional"))
      (node (ref "P2") (pin "12") (pinfunction "GND3_12") (pintype "bidirectional"))
      (node (ref "P2") (pin "16") (pinfunction "GND4_16") (pintype "bidirectional"))
      (node (ref "P2") (pin "20") (pinfunction "GND5_20") (pintype "bidirectional"))
      (node (ref "P2") (pin "4") (pinfunction "TDIS_4") (pintype "bidirectional"))
      (node (ref "P2") (pin "8") (pinfunction "GND1_8") (pintype "bidirectional"))
      (node (ref "P8") (pin "1") (pinfunction "1_1") (pintype "passive"))
      (node (ref "P8") (pin "2") (pinfunction "2_2") (pintype "passive"))
      (node (ref "P9") (pin "1") (pinfunction "1_1") (pintype "passive"))
      (node (ref "P9") (pin "2") (pinfunction "2_2") (pintype "passive"))
      (node (ref "P9") (pin "43") (pinfunction "43_43") (pintype "passive"))
      (node (ref "P9") (pin "44") (pinfunction "44_44") (pintype "passive"))
      (node (ref "P9") (pin "45") (pinfunction "45_45") (pintype "passive"))
      (node (ref "P9") (pin "46") (pinfunction "46_46") (pintype "passive"))
      (node (ref "POWER") (pin "1") (pinfunction "1_1") (pintype "bidirectional"))
      (node (ref "POWER") (pin "2") (pinfunction "2_2") (pintype "bidirectional"))
      (node (ref "R10") (pin "2") (pinfunction "2_2") (pintype "passive"))
      (node (ref "R106") (pin "2") (pinfunction "2_2") (pintype "passive"))
      (node (ref "R108") (pin "2") (pinfunction "2_2") (pintype "passive"))
      (node (ref "R109") (pin "2") (pinfunction "2_2") (pintype "passive"))
      (node (ref "R11") (pin "2") (pinfunction "2_2") (pintype "passive"))
      (node (ref "R114") (pin "1") (pinfunction "1_1") (pintype "passive"))
      (node (ref "R119") (pin "2") (pinfunction "2_2") (pintype "passive"))
      (node (ref "R123") (pin "2") (pinfunction "2_2") (pintype "passive"))
      (node (ref "R17") (pin "1") (pinfunction "1_1") (pintype "passive"))
      (node (ref "R19") (pin "2") (pinfunction "2_2") (pintype "passive"))
      (node (ref "R22") (pin "2") (pinfunction "2_2") (pintype "passive"))
      (node (ref "R24") (pin "1") (pinfunction "1_1") (pintype "passive"))
      (node (ref "R27") (pin "2") (pinfunction "2_2") (pintype "passive"))
      (node (ref "R52") (pin "2") (pinfunction "2_2") (pintype "passive"))
      (node (ref "R55") (pin "1") (pinfunction "1_1") (pintype "passive"))
      (node (ref "R57") (pin "1") (pinfunction "1_1") (pintype "passive"))
      (node (ref "R61") (pin "1") (pinfunction "1_1") (pintype "passive"))
      (node (ref "R63") (pin "1") (pinfunction "1_1") (pintype "passive"))
      (node (ref "R65") (pin "1") (pinfunction "1_1") (pintype "passive"))
      (node (ref "R67") (pin "1") (pinfunction "1_1") (pintype "passive"))
      (node (ref "R69") (pin "1") (pinfunction "1_1") (pintype "passive"))
      (node (ref "R71") (pin "1") (pinfunction "1_1") (pintype "passive"))
      (node (ref "R73") (pin "1") (pinfunction "1_1") (pintype "passive"))
      (node (ref "R75") (pin "1") (pinfunction "1_1") (pintype "passive"))
      (node (ref "R85") (pin "1") (pinfunction "1_1") (pintype "passive"))
      (node (ref "R87") (pin "1") (pinfunction "1_1") (pintype "passive"))
      (node (ref "R94") (pin "2") (pinfunction "2_2") (pintype "passive"))
      (node (ref "R95") (pin "2") (pinfunction "2_2") (pintype "passive"))
      (node (ref "RESET") (pin "1") (pinfunction "1_1") (pintype "bidirectional"))
      (node (ref "RESET") (pin "2") (pinfunction "2_2") (pintype "bidirectional"))
      (node (ref "S2") (pin "3") (pinfunction "3_3") (pintype "bidirectional"))
      (node (ref "S2") (pin "4") (pinfunction "4_4") (pintype "bidirectional"))
      (node (ref "T3") (pin "S") (pinfunction "S_S") (pintype "bidirectional"))
      (node (ref "T4") (pin "S") (pinfunction "S_S") (pintype "bidirectional"))
      (node (ref "TP5") (pin "P$1") (pinfunction "TP_P$1") (pintype "bidirectional"))
      (node (ref "USR0") (pin "K") (pinfunction "K_K") (pintype "passive"))
      (node (ref "USR1") (pin "K") (pinfunction "K_K") (pintype "passive"))
      (node (ref "USR2") (pin "K") (pinfunction "K_K") (pintype "passive"))
      (node (ref "USR3") (pin "K") (pinfunction "K_K") (pintype "passive"))
      (node (ref "X1") (pin "1") (pinfunction "1_1") (pintype "passive"))
      (node (ref "X12") (pin "OUT") (pinfunction "OUT_OUT") (pintype "bidirectional"))
      (node (ref "X2") (pin "6") (pinfunction "VSS_6") (pintype "bidirectional"))
      (node (ref "X2") (pin "GND") (pinfunction "GND_GND") (pintype "bidirectional"))
      (node (ref "X3") (pin "4") (pinfunction "GND_4") (pintype "bidirectional"))
      (node (ref "X4") (pin "GND") (pinfunction "GND_GND") (pintype "input"))
      (node (ref "X5") (pin "10") (pinfunction "TMDS.DATA0.SHIELD_10") (pintype "bidirectional"))
      (node (ref "X5") (pin "13") (pinfunction "TMDS.CLOCK.SHIELD_13") (pintype "bidirectional"))
      (node (ref "X5") (pin "16") (pinfunction "DDC/CEC.GND_16") (pintype "bidirectional"))
      (node (ref "X5") (pin "4") (pinfunction "TMDS.DATA2.SHIELD_4") (pintype "bidirectional"))
      (node (ref "X5") (pin "7") (pinfunction "TMDS.DATA1.SHIELD_7") (pintype "bidirectional"))
    )
    (net (code "182") (name "HDMI_1V8") (class "Default")
      (node (ref "C50") (pin "1") (pinfunction "1_1") (pintype "passive"))
      (node (ref "C51") (pin "1") (pinfunction "1_1") (pintype "passive"))
      (node (ref "C52") (pin "1") (pinfunction "1_1") (pintype "passive"))
      (node (ref "C53") (pin "1") (pinfunction "1_1") (pintype "passive"))
      (node (ref "C54") (pin "1") (pinfunction "1_1") (pintype "passive"))
      (node (ref "C55") (pin "1") (pinfunction "1_1") (pintype "passive"))
      (node (ref "C56") (pin "1") (pinfunction "1_1") (pintype "passive"))
      (node (ref "C57") (pin "1") (pinfunction "1_1") (pintype "passive"))
      (node (ref "FB2") (pin "2") (pinfunction "P$2_2") (pintype "bidirectional"))
      (node (ref "IC9") (pin "14") (pinfunction "VDDD1(IO)(1V8)_14") (pintype "bidirectional"))
      (node (ref "IC9") (pin "29") (pinfunction "VDDDC2_29") (pintype "bidirectional"))
      (node (ref "IC9") (pin "35") (pinfunction "VDDA(1V8)_35") (pintype "bidirectional"))
      (node (ref "IC9") (pin "36") (pinfunction "VDDA1(TX)(1V8)_36") (pintype "bidirectional"))
      (node (ref "IC9") (pin "41") (pinfunction "VDDA2(TX)(1V8)_41") (pintype "bidirectional"))
      (node (ref "IC9") (pin "46") (pinfunction "VDDA3(TX)(1V8)_46") (pintype "bidirectional"))
      (node (ref "IC9") (pin "47") (pinfunction "VDDA1(PLL)(1V8)_47") (pintype "bidirectional"))
      (node (ref "IC9") (pin "48") (pinfunction "VDDA2(PLL)(1V8)_48") (pintype "bidirectional"))
      (node (ref "IC9") (pin "5") (pinfunction "VDDDC1_5") (pintype "bidirectional"))
      (node (ref "IC9") (pin "55") (pinfunction "VDDD2(IO)(1V8)_55") (pintype "bidirectional"))
    )
    (net (code "183") (name "Net-(ANT1-PadSIG)") (class "Default")
      (node (ref "ANT1") (pin "SIG") (pinfunction "SIG_SIG") (pintype "bidirectional"))
      (node (ref "C46") (pin "1") (pinfunction "1_1") (pintype "passive"))
    )
    (net (code "184") (name "Net-(ANT2-PadSIG)") (class "Default")
      (node (ref "ANT2") (pin "SIG") (pinfunction "SIG_SIG") (pintype "bidirectional"))
      (node (ref "C60") (pin "1") (pinfunction "1_1") (pintype "passive"))
    )
    (net (code "185") (name "Net-(BT-PadA)") (class "Default")
      (node (ref "BT") (pin "A") (pinfunction "A_A") (pintype "passive"))
      (node (ref "R124") (pin "1") (pinfunction "1_1") (pintype "passive"))
    )
    (net (code "186") (name "Net-(BT-PadK)") (class "Default")
      (node (ref "BT") (pin "K") (pinfunction "K_K") (pintype "passive"))
      (node (ref "T4") (pin "D") (pinfunction "D_D") (pintype "bidirectional"))
    )
    (net (code "187") (name "Net-(D1-ANODE)") (class "Default")
      (node (ref "D1") (pin "A") (pinfunction "ANODE_A") (pintype "bidirectional"))
      (node (ref "R120") (pin "2") (pinfunction "2_2") (pintype "passive"))
    )
    (net (code "188") (name "Net-(FB3-P$1)") (class "Default")
      (node (ref "C58") (pin "1") (pinfunction "1_1") (pintype "passive"))
      (node (ref "FB3") (pin "1") (pinfunction "P$1_1") (pintype "bidirectional"))
      (node (ref "FB4") (pin "1") (pinfunction "P$1_1") (pintype "bidirectional"))
      (node (ref "IC12") (pin "6") (pinfunction "OUT1_6") (pintype "bidirectional"))
      (node (ref "IC12") (pin "7") (pinfunction "OUT2_7") (pintype "bidirectional"))
      (node (ref "IC12") (pin "8") (pinfunction "OUT3_8") (pintype "bidirectional"))
      (node (ref "IC15") (pin "6") (pinfunction "VBUS_6") (pintype "bidirectional"))
    )
    (net (code "189") (name "Net-(FB3-P$2)") (class "Default")
      (node (ref "FB3") (pin "2") (pinfunction "P$2_2") (pintype "bidirectional"))
      (node (ref "X3") (pin "1") (pinfunction "VBUS_1") (pintype "bidirectional"))
    )
    (net (code "190") (name "Net-(IC1A-(EMMC_RSTN)GPIO1_20)") (class "Default")
      (node (ref "IC1") (pin "R14") (pinfunction "(EMMC_RSTN)GPIO1_20_R14") (pintype "bidirectional"))
      (node (ref "IC3") (pin "2") (pinfunction "A_2") (pintype "bidirectional"))
    )
    (net (code "191") (name "Net-(IC1A-CLKOUT1)") (class "Default")
      (node (ref "FB5") (pin "1") (pinfunction "1_1") (pintype "passive"))
      (node (ref "IC1") (pin "A15") (pinfunction "CLKOUT1_A15") (pintype "bidirectional"))
    )
    (net (code "192") (name "Net-(IC1A-CLKOUT2)") (class "Default")
      (node (ref "FB7") (pin "2") (pinfunction "2_2") (pintype "passive"))
      (node (ref "IC1") (pin "D14") (pinfunction "CLKOUT2_D14") (pintype "bidirectional"))
    )
    (net (code "193") (name "Net-(IC1A-DGND0)") (class "Default")
      (node (ref "C3") (pin "2") (pinfunction "2_2") (pintype "passive"))
      (node (ref "C4") (pin "2") (pinfunction "2_2") (pintype "passive"))
      (node (ref "IC1") (pin "L20") (pinfunction "DGND0_L20") (pintype "bidirectional"))
    )
    (net (code "194") (name "Net-(IC1A-DGND1)") (class "Default")
      (node (ref "C5") (pin "2") (pinfunction "2_2") (pintype "passive"))
      (node (ref "C6") (pin "2") (pinfunction "2_2") (pintype "passive"))
      (node (ref "IC1") (pin "G20") (pinfunction "DGND1_G20") (pintype "bidirectional"))
    )
    (net (code "195") (name "Net-(IC1A-GPIO3_20)") (class "Default")
      (node (ref "IC1") (pin "D13") (pinfunction "GPIO3_20_D13") (pintype "bidirectional"))
      (node (ref "R14") (pin "2") (pinfunction "2_2") (pintype "passive"))
    )
    (net (code "196") (name "Net-(IC1A-OSC0_IN)") (class "Default")
      (node (ref "C3") (pin "1") (pinfunction "1_1") (pintype "passive"))
      (node (ref "IC1") (pin "M20") (pinfunction "OSC0_IN_M20") (pintype "bidirectional"))
      (node (ref "Q4") (pin "2") (pinfunction "P$2_2") (pintype "passive"))
      (node (ref "R8") (pin "2") (pinfunction "2_2") (pintype "passive"))
    )
    (net (code "197") (name "Net-(IC1A-OSC0_OUT)") (class "Default")
      (node (ref "C4") (pin "1") (pinfunction "1_1") (pintype "passive"))
      (node (ref "IC1") (pin "K20") (pinfunction "OSC0_OUT_K20") (pintype "bidirectional"))
      (node (ref "Q4") (pin "1") (pinfunction "P$1_1") (pintype "passive"))
      (node (ref "R8") (pin "1") (pinfunction "1_1") (pintype "passive"))
    )
    (net (code "198") (name "Net-(IC1A-OSC1_IN)") (class "Default")
      (node (ref "C5") (pin "1") (pinfunction "1_1") (pintype "passive"))
      (node (ref "IC1") (pin "H20") (pinfunction "OSC1_IN_H20") (pintype "bidirectional"))
      (node (ref "Q2") (pin "P$1") (pinfunction "P$1_P$1") (pintype "passive"))
      (node (ref "R56") (pin "2") (pinfunction "2_2") (pintype "passive"))
    )
    (net (code "199") (name "Net-(IC1A-OSC1_OUT)") (class "Default")
      (node (ref "C6") (pin "1") (pinfunction "1_1") (pintype "passive"))
      (node (ref "IC1") (pin "F20") (pinfunction "OSC1_OUT_F20") (pintype "bidirectional"))
      (node (ref "Q2") (pin "P$2") (pinfunction "P$2_P$2") (pintype "passive"))
      (node (ref "R56") (pin "1") (pinfunction "1_1") (pintype "passive"))
    )
    (net (code "200") (name "Net-(IC1B-AIN7)") (class "Default")
      (node (ref "IC1") (pin "C9") (pinfunction "AIN7_C9") (pintype "bidirectional"))
      (node (ref "R21") (pin "2") (pinfunction "2_2") (pintype "passive"))
      (node (ref "R22") (pin "1") (pinfunction "1_1") (pintype "passive"))
    )
    (net (code "201") (name "Net-(IC1B-GPIO0_7)") (class "Default")
      (node (ref "IC1") (pin "C18") (pinfunction "GPIO0_7_C18") (pintype "bidirectional"))
      (node (ref "R36") (pin "2") (pinfunction "2_2") (pintype "passive"))
    )
    (net (code "202") (name "Net-(IC1B-GPIO3_18)") (class "Default")
      (node (ref "IC1") (pin "B12") (pinfunction "GPIO3_18_B12") (pintype "bidirectional"))
      (node (ref "R38") (pin "2") (pinfunction "2_2") (pintype "passive"))
    )
    (net (code "203") (name "Net-(IC1B-USB0_VBUS)") (class "Default")
      (node (ref "IC1") (pin "P15") (pinfunction "USB0_VBUS_P15") (pintype "bidirectional"))
      (node (ref "R26") (pin "1") (pinfunction "1_1") (pintype "passive"))
    )
    (net (code "204") (name "Net-(IC1B-USB1_ID)") (class "Default")
      (node (ref "IC1") (pin "P17") (pinfunction "USB1_ID_P17") (pintype "bidirectional"))
      (node (ref "R27") (pin "1") (pinfunction "1_1") (pintype "passive"))
    )
    (net (code "205") (name "Net-(IC1C-PMIC_POWER_EN)") (class "Default")
      (node (ref "IC1") (pin "C6") (pinfunction "PMIC_POWER_EN_C6") (pintype "bidirectional"))
      (node (ref "IC1") (pin "D19") (pinfunction "PWR_EN_D19") (pintype "bidirectional"))
    )
    (net (code "206") (name "Net-(IC1E-RTC_KALDO_ENN)") (class "Default")
      (node (ref "IC1") (pin "B4") (pinfunction "RTC_KALDO_ENN_B4") (pintype "bidirectional"))
      (node (ref "R24") (pin "2") (pinfunction "2_2") (pintype "passive"))
    )
    (net (code "207") (name "Net-(IC3-Y)") (class "Default")
      (node (ref "IC3") (pin "4") (pinfunction "Y_4") (pintype "bidirectional"))
      (node (ref "R29") (pin "2") (pinfunction "2_2") (pintype "passive"))
    )
    (net (code "208") (name "Net-(IC4-WP)") (class "Default")
      (node (ref "IC4") (pin "5") (pinfunction "WP_5") (pintype "bidirectional"))
      (node (ref "R40") (pin "2") (pinfunction "2_2") (pintype "passive"))
      (node (ref "TP1") (pin "P$1") (pinfunction "TP_P$1") (pintype "bidirectional"))
    )
    (net (code "209") (name "Net-(IC5-C)") (class "Default")
      (node (ref "IC5") (pin "2") (pinfunction "C_2") (pintype "passive"))
      (node (ref "R44") (pin "2") (pinfunction "2_2") (pintype "passive"))
      (node (ref "R45") (pin "1") (pinfunction "1_1") (pintype "passive"))
      (node (ref "T1") (pin "B") (pinfunction "B_B") (pintype "passive"))
    )
    (net (code "210") (name "Net-(IC5-FB)") (class "Default")
      (node (ref "IC5") (pin "1") (pinfunction "FB_1") (pintype "passive"))
      (node (ref "R45") (pin "2") (pinfunction "2_2") (pintype "passive"))
      (node (ref "R46") (pin "2") (pinfunction "2_2") (pintype "passive"))
      (node (ref "R47") (pin "1") (pinfunction "1_1") (pintype "passive"))
    )
    (net (code "211") (name "Net-(IC6-C)") (class "Default")
      (node (ref "IC6") (pin "2") (pinfunction "C_2") (pintype "passive"))
      (node (ref "R48") (pin "2") (pinfunction "2_2") (pintype "passive"))
      (node (ref "R49") (pin "1") (pinfunction "1_1") (pintype "passive"))
      (node (ref "T2") (pin "B") (pinfunction "B_B") (pintype "passive"))
    )
    (net (code "212") (name "Net-(IC6-FB)") (class "Default")
      (node (ref "IC6") (pin "1") (pinfunction "FB_1") (pintype "passive"))
      (node (ref "R49") (pin "2") (pinfunction "2_2") (pintype "passive"))
      (node (ref "R50") (pin "2") (pinfunction "2_2") (pintype "passive"))
      (node (ref "R51") (pin "1") (pinfunction "1_1") (pintype "passive"))
    )
    (net (code "213") (name "Net-(IC9-DSCL)") (class "Default")
      (node (ref "IC9") (pin "33") (pinfunction "DSCL_33") (pintype "bidirectional"))
      (node (ref "R115") (pin "2") (pinfunction "2_2") (pintype "passive"))
      (node (ref "X5") (pin "17") (pinfunction "SCL_17") (pintype "bidirectional"))
    )
    (net (code "214") (name "Net-(IC9-DSDA)") (class "Default")
      (node (ref "IC9") (pin "32") (pinfunction "DSDA_32") (pintype "bidirectional"))
      (node (ref "R118") (pin "2") (pinfunction "2_2") (pintype "passive"))
      (node (ref "X5") (pin "18") (pinfunction "SDA_18") (pintype "bidirectional"))
    )
    (net (code "215") (name "Net-(IC10-B1)") (class "Default")
      (node (ref "IC10") (pin "20") (pinfunction "B1_20") (pintype "bidirectional"))
      (node (ref "R130") (pin "2") (pinfunction "2_2") (pintype "passive"))
    )
    (net (code "216") (name "Net-(IC10-B2)") (class "Default")
      (node (ref "IC10") (pin "18") (pinfunction "B2_18") (pintype "bidirectional"))
      (node (ref "R129") (pin "2") (pinfunction "2_2") (pintype "passive"))
    )
    (net (code "217") (name "Net-(IC10-B3)") (class "Default")
      (node (ref "IC10") (pin "17") (pinfunction "B3_17") (pintype "bidirectional"))
      (node (ref "R128") (pin "2") (pinfunction "2_2") (pintype "passive"))
    )
    (net (code "218") (name "Net-(IC10-B4)") (class "Default")
      (node (ref "IC10") (pin "16") (pinfunction "B4_16") (pintype "bidirectional"))
      (node (ref "R127") (pin "2") (pinfunction "2_2") (pintype "passive"))
    )
    (net (code "219") (name "Net-(IC10-B5)") (class "Default")
      (node (ref "IC10") (pin "15") (pinfunction "B5_15") (pintype "bidirectional"))
      (node (ref "R126") (pin "2") (pinfunction "2_2") (pintype "passive"))
    )
    (net (code "220") (name "Net-(IC10-B6)") (class "Default")
      (node (ref "IC10") (pin "14") (pinfunction "B6_14") (pintype "bidirectional"))
      (node (ref "R86") (pin "2") (pinfunction "2_2") (pintype "passive"))
    )
    (net (code "221") (name "Net-(IC10-OE)") (class "Default")
      (node (ref "IC10") (pin "10") (pinfunction "OE_10") (pintype "bidirectional"))
      (node (ref "IC11") (pin "10") (pinfunction "OE_10") (pintype "bidirectional"))
      (node (ref "R106") (pin "1") (pinfunction "1_1") (pintype "passive"))
      (node (ref "R131") (pin "1") (pinfunction "1_1") (pintype "passive"))
    )
    (net (code "222") (name "Net-(IC11-B2)") (class "Default")
      (node (ref "IC11") (pin "18") (pinfunction "B2_18") (pintype "bidirectional"))
      (node (ref "R136") (pin "2") (pinfunction "2_2") (pintype "passive"))
    )
    (net (code "223") (name "Net-(IC11-B3)") (class "Default")
      (node (ref "IC11") (pin "17") (pinfunction "B3_17") (pintype "bidirectional"))
      (node (ref "R135") (pin "2") (pinfunction "2_2") (pintype "passive"))
    )
    (net (code "224") (name "Net-(IC11-B8)") (class "Default")
      (node (ref "IC11") (pin "12") (pinfunction "B8_12") (pintype "bidirectional"))
      (node (ref "R134") (pin "2") (pinfunction "2_2") (pintype "passive"))
    )
    (net (code "225") (name "Net-(IC13-Q)") (class "Default")
      (node (ref "FB6") (pin "1") (pinfunction "1_1") (pintype "passive"))
      (node (ref "IC13") (pin "5") (pinfunction "Q_5") (pintype "bidirectional"))
    )
    (net (code "226") (name "Net-(IC18-ADJ)") (class "Default")
      (node (ref "IC18") (pin "5") (pinfunction "ADJ_5") (pintype "bidirectional"))
      (node (ref "R93") (pin "2") (pinfunction "2_2") (pintype "passive"))
      (node (ref "R94") (pin "1") (pinfunction "1_1") (pintype "passive"))
    )
    (net (code "227") (name "Net-(IC18-SHDN#)") (class "Default")
      (node (ref "IC18") (pin "1") (pinfunction "SHDN#_1") (pintype "bidirectional"))
      (node (ref "R89") (pin "2") (pinfunction "2_2") (pintype "passive"))
      (node (ref "R97") (pin "2") (pinfunction "2_2") (pintype "passive"))
    )
    (net (code "228") (name "Net-(IC22-VDDI)") (class "Default")
      (node (ref "C69") (pin "1") (pinfunction "1_1") (pintype "passive"))
      (node (ref "C7") (pin "1") (pinfunction "1_1") (pintype "passive"))
      (node (ref "IC22") (pin "C2") (pinfunction "VDDI_C2") (pintype "bidirectional"))
    )
    (net (code "229") (name "Net-(OSC1-OUT)") (class "Default")
      (node (ref "OSC1") (pin "3") (pinfunction "OUT_3") (pintype "bidirectional"))
      (node (ref "R110") (pin "1") (pinfunction "1_1") (pintype "passive"))
    )
    (net (code "230") (name "Net-(OSC2-EN)") (class "Default")
      (node (ref "OSC2") (pin "1") (pinfunction "EN_1") (pintype "bidirectional"))
      (node (ref "R90") (pin "2") (pinfunction "2_2") (pintype "passive"))
    )
    (net (code "231") (name "Net-(PWR-PadK)") (class "Default")
      (node (ref "PWR") (pin "K") (pinfunction "K_K") (pintype "passive"))
      (node (ref "R55") (pin "2") (pinfunction "2_2") (pintype "passive"))
    )
    (net (code "232") (name "Net-(R88-Pad2)") (class "Default")
      (node (ref "R88") (pin "2") (pinfunction "2_2") (pintype "passive"))
      (node (ref "S2") (pin "1") (pinfunction "1_1") (pintype "bidirectional"))
      (node (ref "S2") (pin "2") (pinfunction "2_2") (pintype "bidirectional"))
    )
    (net (code "233") (name "Net-(R92-Pad1)") (class "Default")
      (node (ref "R92") (pin "1") (pinfunction "1_1") (pintype "passive"))
      (node (ref "USR3") (pin "A") (pinfunction "A_A") (pintype "passive"))
    )
    (net (code "234") (name "Net-(R96-Pad1)") (class "Default")
      (node (ref "R96") (pin "1") (pinfunction "1_1") (pintype "passive"))
      (node (ref "USR2") (pin "A") (pinfunction "A_A") (pintype "passive"))
    )
    (net (code "235") (name "Net-(R100-Pad1)") (class "Default")
      (node (ref "R100") (pin "1") (pinfunction "1_1") (pintype "passive"))
      (node (ref "USR1") (pin "A") (pinfunction "A_A") (pintype "passive"))
    )
    (net (code "236") (name "Net-(R104-Pad1)") (class "Default")
      (node (ref "R104") (pin "1") (pinfunction "1_1") (pintype "passive"))
      (node (ref "USR0") (pin "A") (pinfunction "A_A") (pintype "passive"))
    )
    (net (code "237") (name "Net-(R111-Pad2)") (class "Default")
      (node (ref "R111") (pin "2") (pinfunction "2_2") (pintype "passive"))
      (node (ref "R60") (pin "1") (pinfunction "1_1") (pintype "passive"))
    )
    (net (code "238") (name "Net-(R125-Pad1)") (class "Default")
      (node (ref "R125") (pin "1") (pinfunction "1_1") (pintype "passive"))
      (node (ref "WL") (pin "A") (pinfunction "A_A") (pintype "passive"))
    )
    (net (code "239") (name "Net-(T3-PadD)") (class "Default")
      (node (ref "T3") (pin "D") (pinfunction "D_D") (pintype "bidirectional"))
      (node (ref "WL") (pin "K") (pinfunction "K_K") (pintype "passive"))
    )
    (net (code "240") (name "SYS_5V") (class "Default")
      (node (ref "C62") (pin "+") (pinfunction "+_+") (pintype "passive"))
      (node (ref "D2") (pin "A") (pinfunction "A_A") (pintype "bidirectional"))
      (node (ref "F1") (pin "2") (pinfunction "2_2") (pintype "passive"))
      (node (ref "IC1") (pin "W4") (pinfunction "SYS_5V_1_W4") (pintype "bidirectional"))
      (node (ref "IC1") (pin "Y4") (pinfunction "SYS_5V_2_Y4") (pintype "bidirectional"))
      (node (ref "IC12") (pin "2") (pinfunction "IN1_2") (pintype "bidirectional"))
      (node (ref "IC12") (pin "3") (pinfunction "IN2_3") (pintype "bidirectional"))
      (node (ref "P9") (pin "7") (pinfunction "7_7") (pintype "passive"))
      (node (ref "P9") (pin "8") (pinfunction "8_8") (pintype "passive"))
    )
    (net (code "241") (name "USB_DC") (class "Default")
      (node (ref "C59") (pin "1") (pinfunction "1_1") (pintype "passive"))
      (node (ref "D4") (pin "A") (pinfunction "A_A") (pintype "bidirectional"))
      (node (ref "IC1") (pin "Y8") (pinfunction "VIN_USB_0_Y8") (pintype "bidirectional"))
      (node (ref "IC1") (pin "Y9") (pinfunction "VIN_USB_1_Y9") (pintype "bidirectional"))
      (node (ref "IC14") (pin "6") (pinfunction "VBUS_6") (pintype "bidirectional"))
      (node (ref "R26") (pin "2") (pinfunction "2_2") (pintype "passive"))
      (node (ref "X4") (pin "VBUS") (pinfunction "VBUS_VBUS") (pintype "input"))
    )
    (net (code "242") (name "VDDS_DDR") (class "Default")
      (node (ref "IC1") (pin "H5") (pinfunction "VDDS_DDR4_H5") (pintype "bidirectional"))
    )
    (net (code "243") (name "VDDS_PLL") (class "Default")
      (node (ref "IC1") (pin "E7") (pinfunction "VDD_PLL1_E7") (pintype "bidirectional"))
    )
    (net (code "244") (name "VDD_1V8") (class "Default")
      (node (ref "FB2") (pin "1") (pinfunction "P$1_1") (pintype "bidirectional"))
      (node (ref "IC1") (pin "D10") (pinfunction "VDD_1V84_D10") (pintype "bidirectional"))
      (node (ref "IC1") (pin "E9") (pinfunction "VDD_1V83_E9") (pintype "bidirectional"))
      (node (ref "IC1") (pin "N16") (pinfunction "VDD_1V8_0_N16") (pintype "bidirectional"))
      (node (ref "IC1") (pin "R16") (pinfunction "VDD_1V8_1_R16") (pintype "bidirectional"))
      (node (ref "IC2") (pin "5") (pinfunction "VCC_5") (pintype "bidirectional"))
      (node (ref "IC5") (pin "3") (pinfunction "A_3") (pintype "passive"))
      (node (ref "IC6") (pin "3") (pinfunction "A_3") (pintype "passive"))
      (node (ref "R47") (pin "2") (pinfunction "2_2") (pintype "passive"))
      (node (ref "R51") (pin "2") (pinfunction "2_2") (pintype "passive"))
      (node (ref "T1") (pin "C") (pinfunction "C_C") (pintype "passive"))
      (node (ref "T2") (pin "C") (pinfunction "C_C") (pintype "passive"))
    )
    (net (code "245") (name "VDD_3V3A") (class "Default")
      (node (ref "IC1") (pin "N5") (pinfunction "VDD_3V3A18_N5") (pintype "bidirectional"))
      (node (ref "IC1") (pin "P5") (pinfunction "VDD_3V3A17_P5") (pintype "bidirectional"))
      (node (ref "IC1") (pin "P6") (pinfunction "VDD_3V3A16_P6") (pintype "bidirectional"))
      (node (ref "IC1") (pin "P7") (pinfunction "VDD_3V3A15_P7") (pintype "bidirectional"))
      (node (ref "R44") (pin "1") (pinfunction "1_1") (pintype "passive"))
      (node (ref "R46") (pin "1") (pinfunction "1_1") (pintype "passive"))
      (node (ref "T1") (pin "E") (pinfunction "E_E") (pintype "passive"))
    )
    (net (code "246") (name "VDD_3V3AUX") (class "Default")
      (node (ref "IC1") (pin "Y11") (pinfunction "VDD_3V3AUX_Y11") (pintype "bidirectional"))
      (node (ref "PWR") (pin "A") (pinfunction "A_A") (pintype "passive"))
    )
    (net (code "247") (name "VDD_3V3B") (class "Default")
      (node (ref "C1") (pin "1") (pinfunction "1_1") (pintype "passive"))
      (node (ref "C12") (pin "1") (pinfunction "1_1") (pintype "passive"))
      (node (ref "C13") (pin "1") (pinfunction "1_1") (pintype "passive"))
      (node (ref "C14") (pin "1") (pinfunction "1_1") (pintype "passive"))
      (node (ref "C15") (pin "1") (pinfunction "1_1") (pintype "passive"))
      (node (ref "C17") (pin "1") (pinfunction "1_1") (pintype "passive"))
      (node (ref "C18") (pin "1") (pinfunction "1_1") (pintype "passive"))
      (node (ref "C2") (pin "1") (pinfunction "1_1") (pintype "passive"))
      (node (ref "C22") (pin "1") (pinfunction "1_1") (pintype "passive"))
      (node (ref "C47") (pin "1") (pinfunction "1_1") (pintype "passive"))
      (node (ref "C48") (pin "1") (pinfunction "1_1") (pintype "passive"))
      (node (ref "C49") (pin "1") (pinfunction "1_1") (pintype "passive"))
      (node (ref "C9") (pin "1") (pinfunction "1_1") (pintype "passive"))
      (node (ref "IC1") (pin "U20") (pinfunction "VDD_3V3B_0_U20") (pintype "bidirectional"))
      (node (ref "IC1") (pin "V20") (pinfunction "VDD_3V3B_1_V20") (pintype "bidirectional"))
      (node (ref "IC13") (pin "6") (pinfunction "CLR#_6") (pintype "bidirectional"))
      (node (ref "IC13") (pin "7") (pinfunction "PRE#_7") (pintype "bidirectional"))
      (node (ref "IC13") (pin "8") (pinfunction "VCC_8") (pintype "bidirectional"))
      (node (ref "IC17") (pin "7") (pinfunction "2OE_7") (pintype "bidirectional"))
      (node (ref "IC17") (pin "8") (pinfunction "VCC_8") (pintype "bidirectional"))
      (node (ref "IC22") (pin "C6") (pinfunction "VCCQ1_C6") (pintype "bidirectional"))
      (node (ref "IC22") (pin "E6") (pinfunction "VCC1_E6") (pintype "bidirectional"))
      (node (ref "IC22") (pin "F5") (pinfunction "VCC2_F5") (pintype "bidirectional"))
      (node (ref "IC22") (pin "J10") (pinfunction "VCC3_J10") (pintype "bidirectional"))
      (node (ref "IC22") (pin "K9") (pinfunction "VCC4_K9") (pintype "bidirectional"))
      (node (ref "IC22") (pin "M4") (pinfunction "VCCQ2_M4") (pintype "bidirectional"))
      (node (ref "IC22") (pin "N4") (pinfunction "VCCQ3_N4") (pintype "bidirectional"))
      (node (ref "IC22") (pin "P3") (pinfunction "VCCQ4_P3") (pintype "bidirectional"))
      (node (ref "IC22") (pin "P5") (pinfunction "VCCQ5_P5") (pintype "bidirectional"))
      (node (ref "IC3") (pin "5") (pinfunction "VCC_5") (pintype "bidirectional"))
      (node (ref "IC4") (pin "4") (pinfunction "VCC_4") (pintype "bidirectional"))
      (node (ref "OSC1") (pin "4") (pinfunction "VCC_4") (pintype "bidirectional"))
      (node (ref "P2") (pin "5") (pinfunction "TVDD_5") (pintype "bidirectional"))
      (node (ref "P9") (pin "3") (pinfunction "3_3") (pintype "passive"))
      (node (ref "P9") (pin "4") (pinfunction "4_4") (pintype "passive"))
      (node (ref "R1") (pin "2") (pinfunction "2_2") (pintype "passive"))
      (node (ref "R12") (pin "2") (pinfunction "2_2") (pintype "passive"))
      (node (ref "R120") (pin "1") (pinfunction "1_1") (pintype "passive"))
      (node (ref "R121") (pin "1") (pinfunction "1_1") (pintype "passive"))
      (node (ref "R122") (pin "1") (pinfunction "1_1") (pintype "passive"))
      (node (ref "R13") (pin "2") (pinfunction "2_2") (pintype "passive"))
      (node (ref "R16") (pin "2") (pinfunction "2_2") (pintype "passive"))
      (node (ref "R18") (pin "2") (pinfunction "2_2") (pintype "passive"))
      (node (ref "R2") (pin "2") (pinfunction "2_2") (pintype "passive"))
      (node (ref "R20") (pin "2") (pinfunction "2_2") (pintype "passive"))
      (node (ref "R21") (pin "1") (pinfunction "1_1") (pintype "passive"))
      (node (ref "R23") (pin "2") (pinfunction "2_2") (pintype "passive"))
      (node (ref "R25") (pin "2") (pinfunction "2_2") (pintype "passive"))
      (node (ref "R28") (pin "2") (pinfunction "2_2") (pintype "passive"))
      (node (ref "R3") (pin "2") (pinfunction "2_2") (pintype "passive"))
      (node (ref "R30") (pin "2") (pinfunction "2_2") (pintype "passive"))
      (node (ref "R31") (pin "2") (pinfunction "2_2") (pintype "passive"))
      (node (ref "R32") (pin "1") (pinfunction "1_1") (pintype "passive"))
      (node (ref "R33") (pin "2") (pinfunction "2_2") (pintype "passive"))
      (node (ref "R4") (pin "2") (pinfunction "2_2") (pintype "passive"))
      (node (ref "R40") (pin "1") (pinfunction "1_1") (pintype "passive"))
      (node (ref "R41") (pin "1") (pinfunction "1_1") (pintype "passive"))
      (node (ref "R42") (pin "1") (pinfunction "1_1") (pintype "passive"))
      (node (ref "R43") (pin "1") (pinfunction "1_1") (pintype "passive"))
      (node (ref "R48") (pin "1") (pinfunction "1_1") (pintype "passive"))
      (node (ref "R5") (pin "2") (pinfunction "2_2") (pintype "passive"))
      (node (ref "R50") (pin "1") (pinfunction "1_1") (pintype "passive"))
      (node (ref "R53") (pin "1") (pinfunction "1_1") (pintype "passive"))
      (node (ref "R58") (pin "2") (pinfunction "2_2") (pintype "passive"))
      (node (ref "R6") (pin "2") (pinfunction "2_2") (pintype "passive"))
      (node (ref "R7") (pin "2") (pinfunction "2_2") (pintype "passive"))
      (node (ref "R76") (pin "2") (pinfunction "2_2") (pintype "passive"))
      (node (ref "R78") (pin "2") (pinfunction "2_2") (pintype "passive"))
      (node (ref "R80") (pin "2") (pinfunction "2_2") (pintype "passive"))
      (node (ref "R82") (pin "2") (pinfunction "2_2") (pintype "passive"))
      (node (ref "R89") (pin "1") (pinfunction "1_1") (pintype "passive"))
      (node (ref "T2") (pin "E") (pinfunction "E_E") (pintype "passive"))
      (node (ref "X2") (pin "4") (pinfunction "VDD_4") (pintype "bidirectional"))
    )
    (net (code "248") (name "VDD_5V") (class "Default")
      (node (ref "D3") (pin "A") (pinfunction "A_A") (pintype "bidirectional"))
      (node (ref "IC1") (pin "Y5") (pinfunction "VIN_5V_0_Y5") (pintype "bidirectional"))
      (node (ref "IC1") (pin "Y6") (pinfunction "VIN_5V_1_Y6") (pintype "bidirectional"))
      (node (ref "P9") (pin "5") (pinfunction "5_5") (pintype "passive"))
      (node (ref "P9") (pin "6") (pinfunction "6_6") (pintype "passive"))
      (node (ref "X12") (pin "IN") (pinfunction "IN_IN") (pintype "bidirectional"))
    )
    (net (code "249") (name "VDD_ADC") (class "Default")
      (node (ref "IC1") (pin "A4") (pinfunction "VDD_ADC_1_A4") (pintype "bidirectional"))
      (node (ref "IC1") (pin "A5") (pinfunction "VDD_ADC_0_A5") (pintype "bidirectional"))
      (node (ref "IC1") (pin "B9") (pinfunction "VREFP_ADC_B9") (pintype "bidirectional"))
      (node (ref "IC1") (pin "D8") (pinfunction "VDDA_ADC_D8") (pintype "bidirectional"))
      (node (ref "P9") (pin "32") (pinfunction "32_32") (pintype "passive"))
    )
    (net (code "250") (name "VDD_CORE") (class "Default")
      (node (ref "IC1") (pin "F6") (pinfunction "VDD_CORE1_F6") (pintype "bidirectional"))
    )
    (net (code "251") (name "VDD_MPU") (class "Default")
      (node (ref "IC1") (pin "F10") (pinfunction "VDD_MPU0_F10") (pintype "bidirectional"))
    )
    (net (code "252") (name "VDD_RTC") (class "Default")
      (node (ref "IC1") (pin "N6") (pinfunction "VDD_RTC4_N6") (pintype "bidirectional"))
    )
    (net (code "253") (name "unconnected-(C46-Pad2)") (class "Default")
      (node (ref "C46") (pin "2") (pinfunction "2_2") (pintype "passive"))
    )
    (net (code "254") (name "unconnected-(C60-Pad2)") (class "Default")
      (node (ref "C60") (pin "2") (pinfunction "2_2") (pintype "passive"))
    )
    (net (code "255") (name "unconnected-(D8-A1-Pad1)") (class "Default")
      (node (ref "D8") (pin "1") (pinfunction "A1_1") (pintype "passive"))
    )
    (net (code "256") (name "unconnected-(FUD1-PadP$1)") (class "Default")
      (node (ref "FUD1") (pin "P$1") (pinfunction "P$1_P$1") (pintype "no_connect"))
    )
    (net (code "257") (name "unconnected-(FUD2-PadP$1)") (class "Default")
      (node (ref "FUD2") (pin "P$1") (pinfunction "P$1_P$1") (pintype "no_connect"))
    )
    (net (code "258") (name "unconnected-(FUD3-PadP$1)") (class "Default")
      (node (ref "FUD3") (pin "P$1") (pinfunction "P$1_P$1") (pintype "no_connect"))
    )
    (net (code "259") (name "unconnected-(FUD4-PadP$1)") (class "Default")
      (node (ref "FUD4") (pin "P$1") (pinfunction "P$1_P$1") (pintype "no_connect"))
    )
    (net (code "260") (name "unconnected-(FUD5-PadP$1)") (class "Default")
      (node (ref "FUD5") (pin "P$1") (pinfunction "P$1_P$1") (pintype "no_connect"))
    )
    (net (code "261") (name "unconnected-(FUD6-PadP$1)") (class "Default")
      (node (ref "FUD6") (pin "P$1") (pinfunction "P$1_P$1") (pintype "no_connect"))
    )
    (net (code "262") (name "unconnected-(IC1B-UART0_CTSN-PadE18)") (class "Default")
      (node (ref "IC1") (pin "E18") (pinfunction "UART0_CTSN_E18") (pintype "bidirectional"))
    )
    (net (code "263") (name "unconnected-(IC1B-USB0_CE-PadM15)") (class "Default")
      (node (ref "IC1") (pin "M15") (pinfunction "USB0_CE_M15") (pintype "bidirectional"))
    )
    (net (code "264") (name "unconnected-(IC1B-USB0_DRVVBUS-PadF16)") (class "Default")
      (node (ref "IC1") (pin "F16") (pinfunction "USB0_DRVVBUS_F16") (pintype "bidirectional"))
    )
    (net (code "265") (name "unconnected-(IC1B-USB1_CE-PadP18)") (class "Default")
      (node (ref "IC1") (pin "P18") (pinfunction "USB1_CE_P18") (pintype "bidirectional"))
    )
    (net (code "266") (name "unconnected-(IC1C-L1_IN-PadY14)") (class "Default")
      (node (ref "IC1") (pin "Y14") (pinfunction "L1_IN_Y14") (pintype "bidirectional"))
    )
    (net (code "267") (name "unconnected-(IC1C-L2_IN-PadY17)") (class "Default")
      (node (ref "IC1") (pin "Y17") (pinfunction "L2_IN_Y17") (pintype "bidirectional"))
    )
    (net (code "268") (name "unconnected-(IC1C-L3_IN-PadY20)") (class "Default")
      (node (ref "IC1") (pin "Y20") (pinfunction "L3_IN_Y20") (pintype "bidirectional"))
    )
    (net (code "269") (name "unconnected-(IC1C-VDDS_DDR-PadY13)") (class "Default")
      (node (ref "IC1") (pin "Y13") (pinfunction "VDDS_DDR_Y13") (pintype "bidirectional"))
    )
    (net (code "270") (name "unconnected-(IC1C-VDD_CORE-PadY19)") (class "Default")
      (node (ref "IC1") (pin "Y19") (pinfunction "VDD_CORE_Y19") (pintype "bidirectional"))
    )
    (net (code "271") (name "unconnected-(IC1C-VDD_MPU-PadY16)") (class "Default")
      (node (ref "IC1") (pin "Y16") (pinfunction "VDD_MPU_Y16") (pintype "bidirectional"))
    )
    (net (code "272") (name "unconnected-(IC1D-NC1-PadB1)") (class "Default")
      (node (ref "IC1") (pin "B1") (pinfunction "NC1_B1") (pintype "bidirectional"))
    )
    (net (code "273") (name "unconnected-(IC1D-NC2-PadB2)") (class "Default")
      (node (ref "IC1") (pin "B2") (pinfunction "NC2_B2") (pintype "bidirectional"))
    )
    (net (code "274") (name "unconnected-(IC1D-NC3-PadB3)") (class "Default")
      (node (ref "IC1") (pin "B3") (pinfunction "NC3_B3") (pintype "bidirectional"))
    )
    (net (code "275") (name "unconnected-(IC1D-NC4-PadC1)") (class "Default")
      (node (ref "IC1") (pin "C1") (pinfunction "NC4_C1") (pintype "bidirectional"))
    )
    (net (code "276") (name "unconnected-(IC1D-NC5-PadC2)") (class "Default")
      (node (ref "IC1") (pin "C2") (pinfunction "NC5_C2") (pintype "bidirectional"))
    )
    (net (code "277") (name "unconnected-(IC1D-NC6-PadC3)") (class "Default")
      (node (ref "IC1") (pin "C3") (pinfunction "NC6_C3") (pintype "bidirectional"))
    )
    (net (code "278") (name "unconnected-(IC1D-NC12-PadC4)") (class "Default")
      (node (ref "IC1") (pin "C4") (pinfunction "NC12_C4") (pintype "bidirectional"))
    )
    (net (code "279") (name "unconnected-(IC1D-NC20-PadD1)") (class "Default")
      (node (ref "IC1") (pin "D1") (pinfunction "NC20_D1") (pintype "bidirectional"))
    )
    (net (code "280") (name "unconnected-(IC1D-NC21-PadD2)") (class "Default")
      (node (ref "IC1") (pin "D2") (pinfunction "NC21_D2") (pintype "bidirectional"))
    )
    (net (code "281") (name "unconnected-(IC1D-NC22-PadD3)") (class "Default")
      (node (ref "IC1") (pin "D3") (pinfunction "NC22_D3") (pintype "bidirectional"))
    )
    (net (code "282") (name "unconnected-(IC1D-NC23-PadD4)") (class "Default")
      (node (ref "IC1") (pin "D4") (pinfunction "NC23_D4") (pintype "bidirectional"))
    )
    (net (code "283") (name "unconnected-(IC1D-NC24-PadD5)") (class "Default")
      (node (ref "IC1") (pin "D5") (pinfunction "NC24_D5") (pintype "bidirectional"))
    )
    (net (code "284") (name "unconnected-(IC1D-NC31-PadE1)") (class "Default")
      (node (ref "IC1") (pin "E1") (pinfunction "NC31_E1") (pintype "bidirectional"))
    )
    (net (code "285") (name "unconnected-(IC1D-NC32-PadE2)") (class "Default")
      (node (ref "IC1") (pin "E2") (pinfunction "NC32_E2") (pintype "bidirectional"))
    )
    (net (code "286") (name "unconnected-(IC1D-NC33-PadE3)") (class "Default")
      (node (ref "IC1") (pin "E3") (pinfunction "NC33_E3") (pintype "bidirectional"))
    )
    (net (code "287") (name "unconnected-(IC1D-NC34-PadE4)") (class "Default")
      (node (ref "IC1") (pin "E4") (pinfunction "NC34_E4") (pintype "bidirectional"))
    )
    (net (code "288") (name "unconnected-(IC1D-NC45-PadF1)") (class "Default")
      (node (ref "IC1") (pin "F1") (pinfunction "NC45_F1") (pintype "bidirectional"))
    )
    (net (code "289") (name "unconnected-(IC1D-NC46-PadF2)") (class "Default")
      (node (ref "IC1") (pin "F2") (pinfunction "NC46_F2") (pintype "bidirectional"))
    )
    (net (code "290") (name "unconnected-(IC1D-NC47-PadF3)") (class "Default")
      (node (ref "IC1") (pin "F3") (pinfunction "NC47_F3") (pintype "bidirectional"))
    )
    (net (code "291") (name "unconnected-(IC1D-NC48-PadF4)") (class "Default")
      (node (ref "IC1") (pin "F4") (pinfunction "NC48_F4") (pintype "bidirectional"))
    )
    (net (code "292") (name "unconnected-(IC1D-NC58-PadG1)") (class "Default")
      (node (ref "IC1") (pin "G1") (pinfunction "NC58_G1") (pintype "bidirectional"))
    )
    (net (code "293") (name "unconnected-(IC1D-NC59-PadG2)") (class "Default")
      (node (ref "IC1") (pin "G2") (pinfunction "NC59_G2") (pintype "bidirectional"))
    )
    (net (code "294") (name "unconnected-(IC1D-NC60-PadG3)") (class "Default")
      (node (ref "IC1") (pin "G3") (pinfunction "NC60_G3") (pintype "bidirectional"))
    )
    (net (code "295") (name "unconnected-(IC1D-NC61-PadG4)") (class "Default")
      (node (ref "IC1") (pin "G4") (pinfunction "NC61_G4") (pintype "bidirectional"))
    )
    (net (code "296") (name "unconnected-(IC1D-NC68-PadH1)") (class "Default")
      (node (ref "IC1") (pin "H1") (pinfunction "NC68_H1") (pintype "bidirectional"))
    )
    (net (code "297") (name "unconnected-(IC1D-NC69-PadH2)") (class "Default")
      (node (ref "IC1") (pin "H2") (pinfunction "NC69_H2") (pintype "bidirectional"))
    )
    (net (code "298") (name "unconnected-(IC1D-NC70-PadH3)") (class "Default")
      (node (ref "IC1") (pin "H3") (pinfunction "NC70_H3") (pintype "bidirectional"))
    )
    (net (code "299") (name "unconnected-(IC1D-NC71-PadH4)") (class "Default")
      (node (ref "IC1") (pin "H4") (pinfunction "NC71_H4") (pintype "bidirectional"))
    )
    (net (code "300") (name "unconnected-(IC1D-NC76-PadJ1)") (class "Default")
      (node (ref "IC1") (pin "J1") (pinfunction "NC76_J1") (pintype "bidirectional"))
    )
    (net (code "301") (name "unconnected-(IC1D-NC77-PadJ2)") (class "Default")
      (node (ref "IC1") (pin "J2") (pinfunction "NC77_J2") (pintype "bidirectional"))
    )
    (net (code "302") (name "unconnected-(IC1D-NC78-PadJ3)") (class "Default")
      (node (ref "IC1") (pin "J3") (pinfunction "NC78_J3") (pintype "bidirectional"))
    )
    (net (code "303") (name "unconnected-(IC1D-NC79-PadJ4)") (class "Default")
      (node (ref "IC1") (pin "J4") (pinfunction "NC79_J4") (pintype "bidirectional"))
    )
    (net (code "304") (name "unconnected-(IC1D-NC84-PadK1)") (class "Default")
      (node (ref "IC1") (pin "K1") (pinfunction "NC84_K1") (pintype "bidirectional"))
    )
    (net (code "305") (name "unconnected-(IC1D-NC85-PadK2)") (class "Default")
      (node (ref "IC1") (pin "K2") (pinfunction "NC85_K2") (pintype "bidirectional"))
    )
    (net (code "306") (name "unconnected-(IC1D-NC86-PadK3)") (class "Default")
      (node (ref "IC1") (pin "K3") (pinfunction "NC86_K3") (pintype "bidirectional"))
    )
    (net (code "307") (name "unconnected-(IC1D-NC87-PadK4)") (class "Default")
      (node (ref "IC1") (pin "K4") (pinfunction "NC87_K4") (pintype "bidirectional"))
    )
    (net (code "308") (name "unconnected-(IC1D-NC94-PadL1)") (class "Default")
      (node (ref "IC1") (pin "L1") (pinfunction "NC94_L1") (pintype "bidirectional"))
    )
    (net (code "309") (name "unconnected-(IC1D-NC95-PadL2)") (class "Default")
      (node (ref "IC1") (pin "L2") (pinfunction "NC95_L2") (pintype "bidirectional"))
    )
    (net (code "310") (name "unconnected-(IC1D-NC96-PadL3)") (class "Default")
      (node (ref "IC1") (pin "L3") (pinfunction "NC96_L3") (pintype "bidirectional"))
    )
    (net (code "311") (name "unconnected-(IC1D-NC97-PadL4)") (class "Default")
      (node (ref "IC1") (pin "L4") (pinfunction "NC97_L4") (pintype "bidirectional"))
    )
    (net (code "312") (name "unconnected-(IC1D-NC104-PadM1)") (class "Default")
      (node (ref "IC1") (pin "M1") (pinfunction "NC104_M1") (pintype "bidirectional"))
    )
    (net (code "313") (name "unconnected-(IC1D-NC105-PadM2)") (class "Default")
      (node (ref "IC1") (pin "M2") (pinfunction "NC105_M2") (pintype "bidirectional"))
    )
    (net (code "314") (name "unconnected-(IC1D-NC106-PadM3)") (class "Default")
      (node (ref "IC1") (pin "M3") (pinfunction "NC106_M3") (pintype "bidirectional"))
    )
    (net (code "315") (name "unconnected-(IC1D-NC107-PadM4)") (class "Default")
      (node (ref "IC1") (pin "M4") (pinfunction "NC107_M4") (pintype "bidirectional"))
    )
    (net (code "316") (name "unconnected-(IC1D-NC111-PadN1)") (class "Default")
      (node (ref "IC1") (pin "N1") (pinfunction "NC111_N1") (pintype "bidirectional"))
    )
    (net (code "317") (name "unconnected-(IC1D-NC112-PadN2)") (class "Default")
      (node (ref "IC1") (pin "N2") (pinfunction "NC112_N2") (pintype "bidirectional"))
    )
    (net (code "318") (name "unconnected-(IC1D-NC113-PadN3)") (class "Default")
      (node (ref "IC1") (pin "N3") (pinfunction "NC113_N3") (pintype "bidirectional"))
    )
    (net (code "319") (name "unconnected-(IC1D-NC114-PadN4)") (class "Default")
      (node (ref "IC1") (pin "N4") (pinfunction "NC114_N4") (pintype "bidirectional"))
    )
    (net (code "320") (name "unconnected-(IC1D-NC121-PadP1)") (class "Default")
      (node (ref "IC1") (pin "P1") (pinfunction "NC121_P1") (pintype "bidirectional"))
    )
    (net (code "321") (name "unconnected-(IC1D-NC122-PadP2)") (class "Default")
      (node (ref "IC1") (pin "P2") (pinfunction "NC122_P2") (pintype "bidirectional"))
    )
    (net (code "322") (name "unconnected-(IC1D-NC123-PadP3)") (class "Default")
      (node (ref "IC1") (pin "P3") (pinfunction "NC123_P3") (pintype "bidirectional"))
    )
    (net (code "323") (name "unconnected-(IC1D-NC124-PadP4)") (class "Default")
      (node (ref "IC1") (pin "P4") (pinfunction "NC124_P4") (pintype "bidirectional"))
    )
    (net (code "324") (name "unconnected-(IC1D-NC136-PadU11)") (class "Default")
      (node (ref "IC1") (pin "U11") (pinfunction "NC136_U11") (pintype "bidirectional"))
    )
    (net (code "325") (name "unconnected-(IC1D-NC137-PadV10)") (class "Default")
      (node (ref "IC1") (pin "V10") (pinfunction "NC137_V10") (pintype "bidirectional"))
    )
    (net (code "326") (name "unconnected-(IC1D-NC138-PadV11)") (class "Default")
      (node (ref "IC1") (pin "V11") (pinfunction "NC138_V11") (pintype "bidirectional"))
    )
    (net (code "327") (name "unconnected-(IC1E-CAP_VBB_MPU-PadC10)") (class "Default")
      (node (ref "IC1") (pin "C10") (pinfunction "CAP_VBB_MPU_C10") (pintype "bidirectional"))
    )
    (net (code "328") (name "unconnected-(IC1E-CAP_VDD_RTC-PadD6)") (class "Default")
      (node (ref "IC1") (pin "D6") (pinfunction "CAP_VDD_RTC_D6") (pintype "bidirectional"))
    )
    (net (code "329") (name "unconnected-(IC1E-CAP_VDD_SRAM_COR-PadD9)") (class "Default")
      (node (ref "IC1") (pin "D9") (pinfunction "CAP_VDD_SRAM_COR_D9") (pintype "bidirectional"))
    )
    (net (code "330") (name "unconnected-(IC1E-CAP_VDD_SRAM_MPU-PadD11)") (class "Default")
      (node (ref "IC1") (pin "D11") (pinfunction "CAP_VDD_SRAM_MPU_D11") (pintype "bidirectional"))
    )
    (net (code "331") (name "unconnected-(IC1E-TESTOUT-PadA3)") (class "Default")
      (node (ref "IC1") (pin "A3") (pinfunction "TESTOUT_A3") (pintype "bidirectional"))
    )
    (net (code "332") (name "unconnected-(IC1E-VDDS_DDR1-PadE5)") (class "Default")
      (node (ref "IC1") (pin "E5") (pinfunction "VDDS_DDR1_E5") (pintype "bidirectional"))
    )
    (net (code "333") (name "unconnected-(IC1E-VDDS_DDR2-PadF5)") (class "Default")
      (node (ref "IC1") (pin "F5") (pinfunction "VDDS_DDR2_F5") (pintype "bidirectional"))
    )
    (net (code "334") (name "unconnected-(IC1E-VDDS_DDR3-PadG5)") (class "Default")
      (node (ref "IC1") (pin "G5") (pinfunction "VDDS_DDR3_G5") (pintype "bidirectional"))
    )
    (net (code "335") (name "unconnected-(IC1E-VDDS_DDR5-PadJ5)") (class "Default")
      (node (ref "IC1") (pin "J5") (pinfunction "VDDS_DDR5_J5") (pintype "bidirectional"))
    )
    (net (code "336") (name "unconnected-(IC1E-VDDS_DDR6-PadK5)") (class "Default")
      (node (ref "IC1") (pin "K5") (pinfunction "VDDS_DDR6_K5") (pintype "bidirectional"))
    )
    (net (code "337") (name "unconnected-(IC1E-VDDS_DDR7-PadL5)") (class "Default")
      (node (ref "IC1") (pin "L5") (pinfunction "VDDS_DDR7_L5") (pintype "bidirectional"))
    )
    (net (code "338") (name "unconnected-(IC1E-VDD_3V3A1-PadF14)") (class "Default")
      (node (ref "IC1") (pin "F14") (pinfunction "VDD_3V3A1_F14") (pintype "bidirectional"))
    )
    (net (code "339") (name "unconnected-(IC1E-VDD_3V3A2-PadG14)") (class "Default")
      (node (ref "IC1") (pin "G14") (pinfunction "VDD_3V3A2_G14") (pintype "bidirectional"))
    )
    (net (code "340") (name "unconnected-(IC1E-VDD_3V3A3-PadH14)") (class "Default")
      (node (ref "IC1") (pin "H14") (pinfunction "VDD_3V3A3_H14") (pintype "bidirectional"))
    )
    (net (code "341") (name "unconnected-(IC1E-VDD_3V3A4-PadJ14)") (class "Default")
      (node (ref "IC1") (pin "J14") (pinfunction "VDD_3V3A4_J14") (pintype "bidirectional"))
    )
    (net (code "342") (name "unconnected-(IC1E-VDD_3V3A5-PadK14)") (class "Default")
      (node (ref "IC1") (pin "K14") (pinfunction "VDD_3V3A5_K14") (pintype "bidirectional"))
    )
    (net (code "343") (name "unconnected-(IC1E-VDD_3V3A6-PadL14)") (class "Default")
      (node (ref "IC1") (pin "L14") (pinfunction "VDD_3V3A6_L14") (pintype "bidirectional"))
    )
    (net (code "344") (name "unconnected-(IC1E-VDD_3V3A7-PadN15)") (class "Default")
      (node (ref "IC1") (pin "N15") (pinfunction "VDD_3V3A7_N15") (pintype "bidirectional"))
    )
    (net (code "345") (name "unconnected-(IC1E-VDD_3V3A8-PadR15)") (class "Default")
      (node (ref "IC1") (pin "R15") (pinfunction "VDD_3V3A8_R15") (pintype "bidirectional"))
    )
    (net (code "346") (name "unconnected-(IC1E-VDD_3V3A9-PadP13)") (class "Default")
      (node (ref "IC1") (pin "P13") (pinfunction "VDD_3V3A9_P13") (pintype "bidirectional"))
    )
    (net (code "347") (name "unconnected-(IC1E-VDD_3V3A10-PadP12)") (class "Default")
      (node (ref "IC1") (pin "P12") (pinfunction "VDD_3V3A10_P12") (pintype "bidirectional"))
    )
    (net (code "348") (name "unconnected-(IC1E-VDD_3V3A11-PadP11)") (class "Default")
      (node (ref "IC1") (pin "P11") (pinfunction "VDD_3V3A11_P11") (pintype "bidirectional"))
    )
    (net (code "349") (name "unconnected-(IC1E-VDD_3V3A12-PadP10)") (class "Default")
      (node (ref "IC1") (pin "P10") (pinfunction "VDD_3V3A12_P10") (pintype "bidirectional"))
    )
    (net (code "350") (name "unconnected-(IC1E-VDD_3V3A14-PadP8)") (class "Default")
      (node (ref "IC1") (pin "P8") (pinfunction "VDD_3V3A14_P8") (pintype "bidirectional"))
    )
    (net (code "351") (name "unconnected-(IC1E-VDD_3V3A19-PadE13)") (class "Default")
      (node (ref "IC1") (pin "E13") (pinfunction "VDD_3V3A19_E13") (pintype "bidirectional"))
    )
    (net (code "352") (name "unconnected-(IC1E-VDD_3V3A20-PadE12)") (class "Default")
      (node (ref "IC1") (pin "E12") (pinfunction "VDD_3V3A20_E12") (pintype "bidirectional"))
    )
    (net (code "353") (name "unconnected-(IC1E-VDD_3V3A21-PadE11)") (class "Default")
      (node (ref "IC1") (pin "E11") (pinfunction "VDD_3V3A21_E11") (pintype "bidirectional"))
    )
    (net (code "354") (name "unconnected-(IC1E-VDD_3V3A22-PadE10)") (class "Default")
      (node (ref "IC1") (pin "E10") (pinfunction "VDD_3V3A22_E10") (pintype "bidirectional"))
    )
    (net (code "355") (name "unconnected-(IC1E-VDD_CORE2-PadF7)") (class "Default")
      (node (ref "IC1") (pin "F7") (pinfunction "VDD_CORE2_F7") (pintype "bidirectional"))
    )
    (net (code "356") (name "unconnected-(IC1E-VDD_CORE3-PadG6)") (class "Default")
      (node (ref "IC1") (pin "G6") (pinfunction "VDD_CORE3_G6") (pintype "bidirectional"))
    )
    (net (code "357") (name "unconnected-(IC1E-VDD_CORE4-PadG7)") (class "Default")
      (node (ref "IC1") (pin "G7") (pinfunction "VDD_CORE4_G7") (pintype "bidirectional"))
    )
    (net (code "358") (name "unconnected-(IC1E-VDD_CORE5-PadG10)") (class "Default")
      (node (ref "IC1") (pin "G10") (pinfunction "VDD_CORE5_G10") (pintype "bidirectional"))
    )
    (net (code "359") (name "unconnected-(IC1E-VDD_CORE6-PadH11)") (class "Default")
      (node (ref "IC1") (pin "H11") (pinfunction "VDD_CORE6_H11") (pintype "bidirectional"))
    )
    (net (code "360") (name "unconnected-(IC1E-VDD_CORE7-PadJ12)") (class "Default")
      (node (ref "IC1") (pin "J12") (pinfunction "VDD_CORE7_J12") (pintype "bidirectional"))
    )
    (net (code "361") (name "unconnected-(IC1E-VDD_CORE8-PadK6)") (class "Default")
      (node (ref "IC1") (pin "K6") (pinfunction "VDD_CORE8_K6") (pintype "bidirectional"))
    )
    (net (code "362") (name "unconnected-(IC1E-VDD_CORE9-PadK8)") (class "Default")
      (node (ref "IC1") (pin "K8") (pinfunction "VDD_CORE9_K8") (pintype "bidirectional"))
    )
    (net (code "363") (name "unconnected-(IC1E-VDD_CORE10-PadK12)") (class "Default")
      (node (ref "IC1") (pin "K12") (pinfunction "VDD_CORE10_K12") (pintype "bidirectional"))
    )
    (net (code "364") (name "unconnected-(IC1E-VDD_CORE11-PadL6)") (class "Default")
      (node (ref "IC1") (pin "L6") (pinfunction "VDD_CORE11_L6") (pintype "bidirectional"))
    )
    (net (code "365") (name "unconnected-(IC1E-VDD_CORE12-PadL7)") (class "Default")
      (node (ref "IC1") (pin "L7") (pinfunction "VDD_CORE12_L7") (pintype "bidirectional"))
    )
    (net (code "366") (name "unconnected-(IC1E-VDD_CORE13-PadL8)") (class "Default")
      (node (ref "IC1") (pin "L8") (pinfunction "VDD_CORE13_L8") (pintype "bidirectional"))
    )
    (net (code "367") (name "unconnected-(IC1E-VDD_CORE14-PadL9)") (class "Default")
      (node (ref "IC1") (pin "L9") (pinfunction "VDD_CORE14_L9") (pintype "bidirectional"))
    )
    (net (code "368") (name "unconnected-(IC1E-VDD_CORE15-PadM11)") (class "Default")
      (node (ref "IC1") (pin "M11") (pinfunction "VDD_CORE15_M11") (pintype "bidirectional"))
    )
    (net (code "369") (name "unconnected-(IC1E-VDD_CORE16-PadM13)") (class "Default")
      (node (ref "IC1") (pin "M13") (pinfunction "VDD_CORE16_M13") (pintype "bidirectional"))
    )
    (net (code "370") (name "unconnected-(IC1E-VDD_CORE17-PadN8)") (class "Default")
      (node (ref "IC1") (pin "N8") (pinfunction "VDD_CORE17_N8") (pintype "bidirectional"))
    )
    (net (code "371") (name "unconnected-(IC1E-VDD_CORE18-PadN9)") (class "Default")
      (node (ref "IC1") (pin "N9") (pinfunction "VDD_CORE18_N9") (pintype "bidirectional"))
    )
    (net (code "372") (name "unconnected-(IC1E-VDD_CORE19-PadN12)") (class "Default")
      (node (ref "IC1") (pin "N12") (pinfunction "VDD_CORE19_N12") (pintype "bidirectional"))
    )
    (net (code "373") (name "unconnected-(IC1E-VDD_CORE20-PadN13)") (class "Default")
      (node (ref "IC1") (pin "N13") (pinfunction "VDD_CORE20_N13") (pintype "bidirectional"))
    )
    (net (code "374") (name "unconnected-(IC1E-VDD_MPU1-PadF11)") (class "Default")
      (node (ref "IC1") (pin "F11") (pinfunction "VDD_MPU1_F11") (pintype "bidirectional"))
    )
    (net (code "375") (name "unconnected-(IC1E-VDD_MPU2-PadF12)") (class "Default")
      (node (ref "IC1") (pin "F12") (pinfunction "VDD_MPU2_F12") (pintype "bidirectional"))
    )
    (net (code "376") (name "unconnected-(IC1E-VDD_MPU3-PadF13)") (class "Default")
      (node (ref "IC1") (pin "F13") (pinfunction "VDD_MPU3_F13") (pintype "bidirectional"))
    )
    (net (code "377") (name "unconnected-(IC1E-VDD_MPU4-PadG13)") (class "Default")
      (node (ref "IC1") (pin "G13") (pinfunction "VDD_MPU4_G13") (pintype "bidirectional"))
    )
    (net (code "378") (name "unconnected-(IC1E-VDD_MPU5-PadH13)") (class "Default")
      (node (ref "IC1") (pin "H13") (pinfunction "VDD_MPU5_H13") (pintype "bidirectional"))
    )
    (net (code "379") (name "unconnected-(IC1E-VDD_MPU6-PadJ13)") (class "Default")
      (node (ref "IC1") (pin "J13") (pinfunction "VDD_MPU6_J13") (pintype "bidirectional"))
    )
    (net (code "380") (name "unconnected-(IC1E-VDD_MPU_MON-PadA2)") (class "Default")
      (node (ref "IC1") (pin "A2") (pinfunction "VDD_MPU_MON_A2") (pintype "bidirectional"))
    )
    (net (code "381") (name "unconnected-(IC1E-VDD_PLL2-PadR10)") (class "Default")
      (node (ref "IC1") (pin "R10") (pinfunction "VDD_PLL2_R10") (pintype "bidirectional"))
    )
    (net (code "382") (name "unconnected-(IC1E-VDD_PLL3-PadR11)") (class "Default")
      (node (ref "IC1") (pin "R11") (pinfunction "VDD_PLL3_R11") (pintype "bidirectional"))
    )
    (net (code "383") (name "unconnected-(IC1E-VDD_PLL4-PadH15)") (class "Default")
      (node (ref "IC1") (pin "H15") (pinfunction "VDD_PLL4_H15") (pintype "bidirectional"))
    )
    (net (code "384") (name "unconnected-(IC1E-VDD_RTC1-PadD7)") (class "Default")
      (node (ref "IC1") (pin "D7") (pinfunction "VDD_RTC1_D7") (pintype "bidirectional"))
    )
    (net (code "385") (name "unconnected-(IC1E-VDD_RTC2-PadE6)") (class "Default")
      (node (ref "IC1") (pin "E6") (pinfunction "VDD_RTC2_E6") (pintype "bidirectional"))
    )
    (net (code "386") (name "unconnected-(IC1E-VDD_RTC3-PadF9)") (class "Default")
      (node (ref "IC1") (pin "F9") (pinfunction "VDD_RTC3_F9") (pintype "bidirectional"))
    )
    (net (code "387") (name "unconnected-(IC1E-VDD_RTC5-PadP14)") (class "Default")
      (node (ref "IC1") (pin "P14") (pinfunction "VDD_RTC5_P14") (pintype "bidirectional"))
    )
    (net (code "388") (name "unconnected-(IC1E-VDD_RTC6-PadK13)") (class "Default")
      (node (ref "IC1") (pin "K13") (pinfunction "VDD_RTC6_K13") (pintype "bidirectional"))
    )
    (net (code "389") (name "unconnected-(IC1E-VDD_RTC7-PadE14)") (class "Default")
      (node (ref "IC1") (pin "E14") (pinfunction "VDD_RTC7_E14") (pintype "bidirectional"))
    )
    (net (code "390") (name "unconnected-(IC1E-VDD_RTC8-PadP9)") (class "Default")
      (node (ref "IC1") (pin "P9") (pinfunction "VDD_RTC8_P9") (pintype "bidirectional"))
    )
    (net (code "391") (name "unconnected-(IC1E-VPP-PadM5)") (class "Default")
      (node (ref "IC1") (pin "M5") (pinfunction "VPP_M5") (pintype "bidirectional"))
    )
    (net (code "392") (name "unconnected-(IC7-NC1-Pad6)") (class "Default")
      (node (ref "IC7") (pin "6") (pinfunction "NC1_6") (pintype "bidirectional"))
    )
    (net (code "393") (name "unconnected-(IC7-NC2-Pad7)") (class "Default")
      (node (ref "IC7") (pin "7") (pinfunction "NC2_7") (pintype "bidirectional"))
    )
    (net (code "394") (name "unconnected-(IC7-NC3-Pad9)") (class "Default")
      (node (ref "IC7") (pin "9") (pinfunction "NC3_9") (pintype "bidirectional"))
    )
    (net (code "395") (name "unconnected-(IC7-NC4-Pad10)") (class "Default")
      (node (ref "IC7") (pin "10") (pinfunction "NC4_10") (pintype "bidirectional"))
    )
    (net (code "396") (name "unconnected-(IC8-NC1-Pad6)") (class "Default")
      (node (ref "IC8") (pin "6") (pinfunction "NC1_6") (pintype "bidirectional"))
    )
    (net (code "397") (name "unconnected-(IC8-NC2-Pad7)") (class "Default")
      (node (ref "IC8") (pin "7") (pinfunction "NC2_7") (pintype "bidirectional"))
    )
    (net (code "398") (name "unconnected-(IC8-NC3-Pad9)") (class "Default")
      (node (ref "IC8") (pin "9") (pinfunction "NC3_9") (pintype "bidirectional"))
    )
    (net (code "399") (name "unconnected-(IC8-NC4-Pad10)") (class "Default")
      (node (ref "IC8") (pin "10") (pinfunction "NC4_10") (pintype "bidirectional"))
    )
    (net (code "400") (name "unconnected-(IC9-AP2-Pad26)") (class "Default")
      (node (ref "IC9") (pin "26") (pinfunction "AP2_26") (pintype "bidirectional"))
    )
    (net (code "401") (name "unconnected-(IC9-AP4-Pad28)") (class "Default")
      (node (ref "IC9") (pin "28") (pinfunction "AP4_28") (pintype "bidirectional"))
    )
    (net (code "402") (name "unconnected-(IC10-A7-Pad8)") (class "Default")
      (node (ref "IC10") (pin "8") (pinfunction "A7_8") (pintype "bidirectional"))
    )
    (net (code "403") (name "unconnected-(IC10-A8-Pad9)") (class "Default")
      (node (ref "IC10") (pin "9") (pinfunction "A8_9") (pintype "bidirectional"))
    )
    (net (code "404") (name "unconnected-(IC10-B7-Pad13)") (class "Default")
      (node (ref "IC10") (pin "13") (pinfunction "B7_13") (pintype "bidirectional"))
    )
    (net (code "405") (name "unconnected-(IC10-B8-Pad12)") (class "Default")
      (node (ref "IC10") (pin "12") (pinfunction "B8_12") (pintype "bidirectional"))
    )
    (net (code "406") (name "unconnected-(IC14-NC-Pad5)") (class "Default")
      (node (ref "IC14") (pin "5") (pinfunction "NC_5") (pintype "bidirectional"))
    )
    (net (code "407") (name "unconnected-(IC15-ID-Pad3)") (class "Default")
      (node (ref "IC15") (pin "3") (pinfunction "ID_3") (pintype "bidirectional"))
    )
    (net (code "408") (name "unconnected-(IC15-NC-Pad5)") (class "Default")
      (node (ref "IC15") (pin "5") (pinfunction "NC_5") (pintype "bidirectional"))
    )
    (net (code "409") (name "unconnected-(IC19-NC{slash}ADJ-Pad4)") (class "Default")
      (node (ref "IC19") (pin "4") (pinfunction "NC/ADJ_4") (pintype "bidirectional"))
    )
    (net (code "410") (name "unconnected-(P2-NC-Pad6)") (class "Default")
      (node (ref "P2") (pin "6") (pinfunction "NC_6") (pintype "bidirectional"))
    )
    (net (code "411") (name "unconnected-(R62-Pad1)") (class "Default")
      (node (ref "R62") (pin "1") (pinfunction "1_1") (pintype "passive"))
    )
    (net (code "412") (name "unconnected-(R64-Pad1)") (class "Default")
      (node (ref "R64") (pin "1") (pinfunction "1_1") (pintype "passive"))
    )
    (net (code "413") (name "unconnected-(R66-Pad1)") (class "Default")
      (node (ref "R66") (pin "1") (pinfunction "1_1") (pintype "passive"))
    )
    (net (code "414") (name "unconnected-(R68-Pad1)") (class "Default")
      (node (ref "R68") (pin "1") (pinfunction "1_1") (pintype "passive"))
    )
    (net (code "415") (name "unconnected-(R70-Pad1)") (class "Default")
      (node (ref "R70") (pin "1") (pinfunction "1_1") (pintype "passive"))
    )
    (net (code "416") (name "unconnected-(R72-Pad1)") (class "Default")
      (node (ref "R72") (pin "1") (pinfunction "1_1") (pintype "passive"))
    )
    (net (code "417") (name "unconnected-(R140-Pad1)") (class "Default")
      (node (ref "R140") (pin "1") (pinfunction "1_1") (pintype "passive"))
    )
    (net (code "418") (name "unconnected-(R141-Pad1)") (class "Default")
      (node (ref "R141") (pin "1") (pinfunction "1_1") (pintype "passive"))
    )
    (net (code "419") (name "unconnected-(R142-Pad1)") (class "Default")
      (node (ref "R142") (pin "1") (pinfunction "1_1") (pintype "passive"))
    )
    (net (code "420") (name "unconnected-(R143-Pad1)") (class "Default")
      (node (ref "R143") (pin "1") (pinfunction "1_1") (pintype "passive"))
    )
    (net (code "421") (name "unconnected-(TP12-PadTP)") (class "Default")
      (node (ref "TP12") (pin "TP") (pinfunction "TP_TP") (pintype "input"))
    )
    (net (code "422") (name "unconnected-(TP13-PadTP)") (class "Default")
      (node (ref "TP13") (pin "TP") (pinfunction "TP_TP") (pintype "input"))
    )
    (net (code "423") (name "unconnected-(TP14-PadTP)") (class "Default")
      (node (ref "TP14") (pin "TP") (pinfunction "TP_TP") (pintype "input"))
    )
    (net (code "424") (name "unconnected-(TP15-PadTP)") (class "Default")
      (node (ref "TP15") (pin "TP") (pinfunction "TP_TP") (pintype "input"))
    )
    (net (code "425") (name "unconnected-(TP16-PadTP)") (class "Default")
      (node (ref "TP16") (pin "TP") (pinfunction "TP_TP") (pintype "input"))
    )
    (net (code "426") (name "unconnected-(TP17-PadTP)") (class "Default")
      (node (ref "TP17") (pin "TP") (pinfunction "TP_TP") (pintype "input"))
    )
    (net (code "427") (name "unconnected-(TP18-PadTP)") (class "Default")
      (node (ref "TP18") (pin "TP") (pinfunction "TP_TP") (pintype "input"))
    )
    (net (code "428") (name "unconnected-(TP19-PadTP)") (class "Default")
      (node (ref "TP19") (pin "TP") (pinfunction "TP_TP") (pintype "input"))
    )
    (net (code "429") (name "unconnected-(X1-Pad2)") (class "Default")
      (node (ref "X1") (pin "2") (pinfunction "2_2") (pintype "passive"))
    )
    (net (code "430") (name "unconnected-(X1-Pad3)") (class "Default")
      (node (ref "X1") (pin "3") (pinfunction "3_3") (pintype "passive"))
    )
    (net (code "431") (name "unconnected-(X1-Pad6)") (class "Default")
      (node (ref "X1") (pin "6") (pinfunction "6_6") (pintype "passive"))
    )
    (net (code "432") (name "unconnected-(X5-NC-Pad2)") (class "Default")
      (node (ref "X5") (pin "2") (pinfunction "NC_2") (pintype "bidirectional"))
    )
    (net (code "433") (name "unconnected-(X12-PadOUT_CON)") (class "Default")
      (node (ref "X12") (pin "OUT_CON") (pinfunction "OUT_CON_OUT_CON") (pintype "bidirectional"))
    )
  )
)
